# 32pins.net
KiCad netlist of a schematic drawn in EAGLE
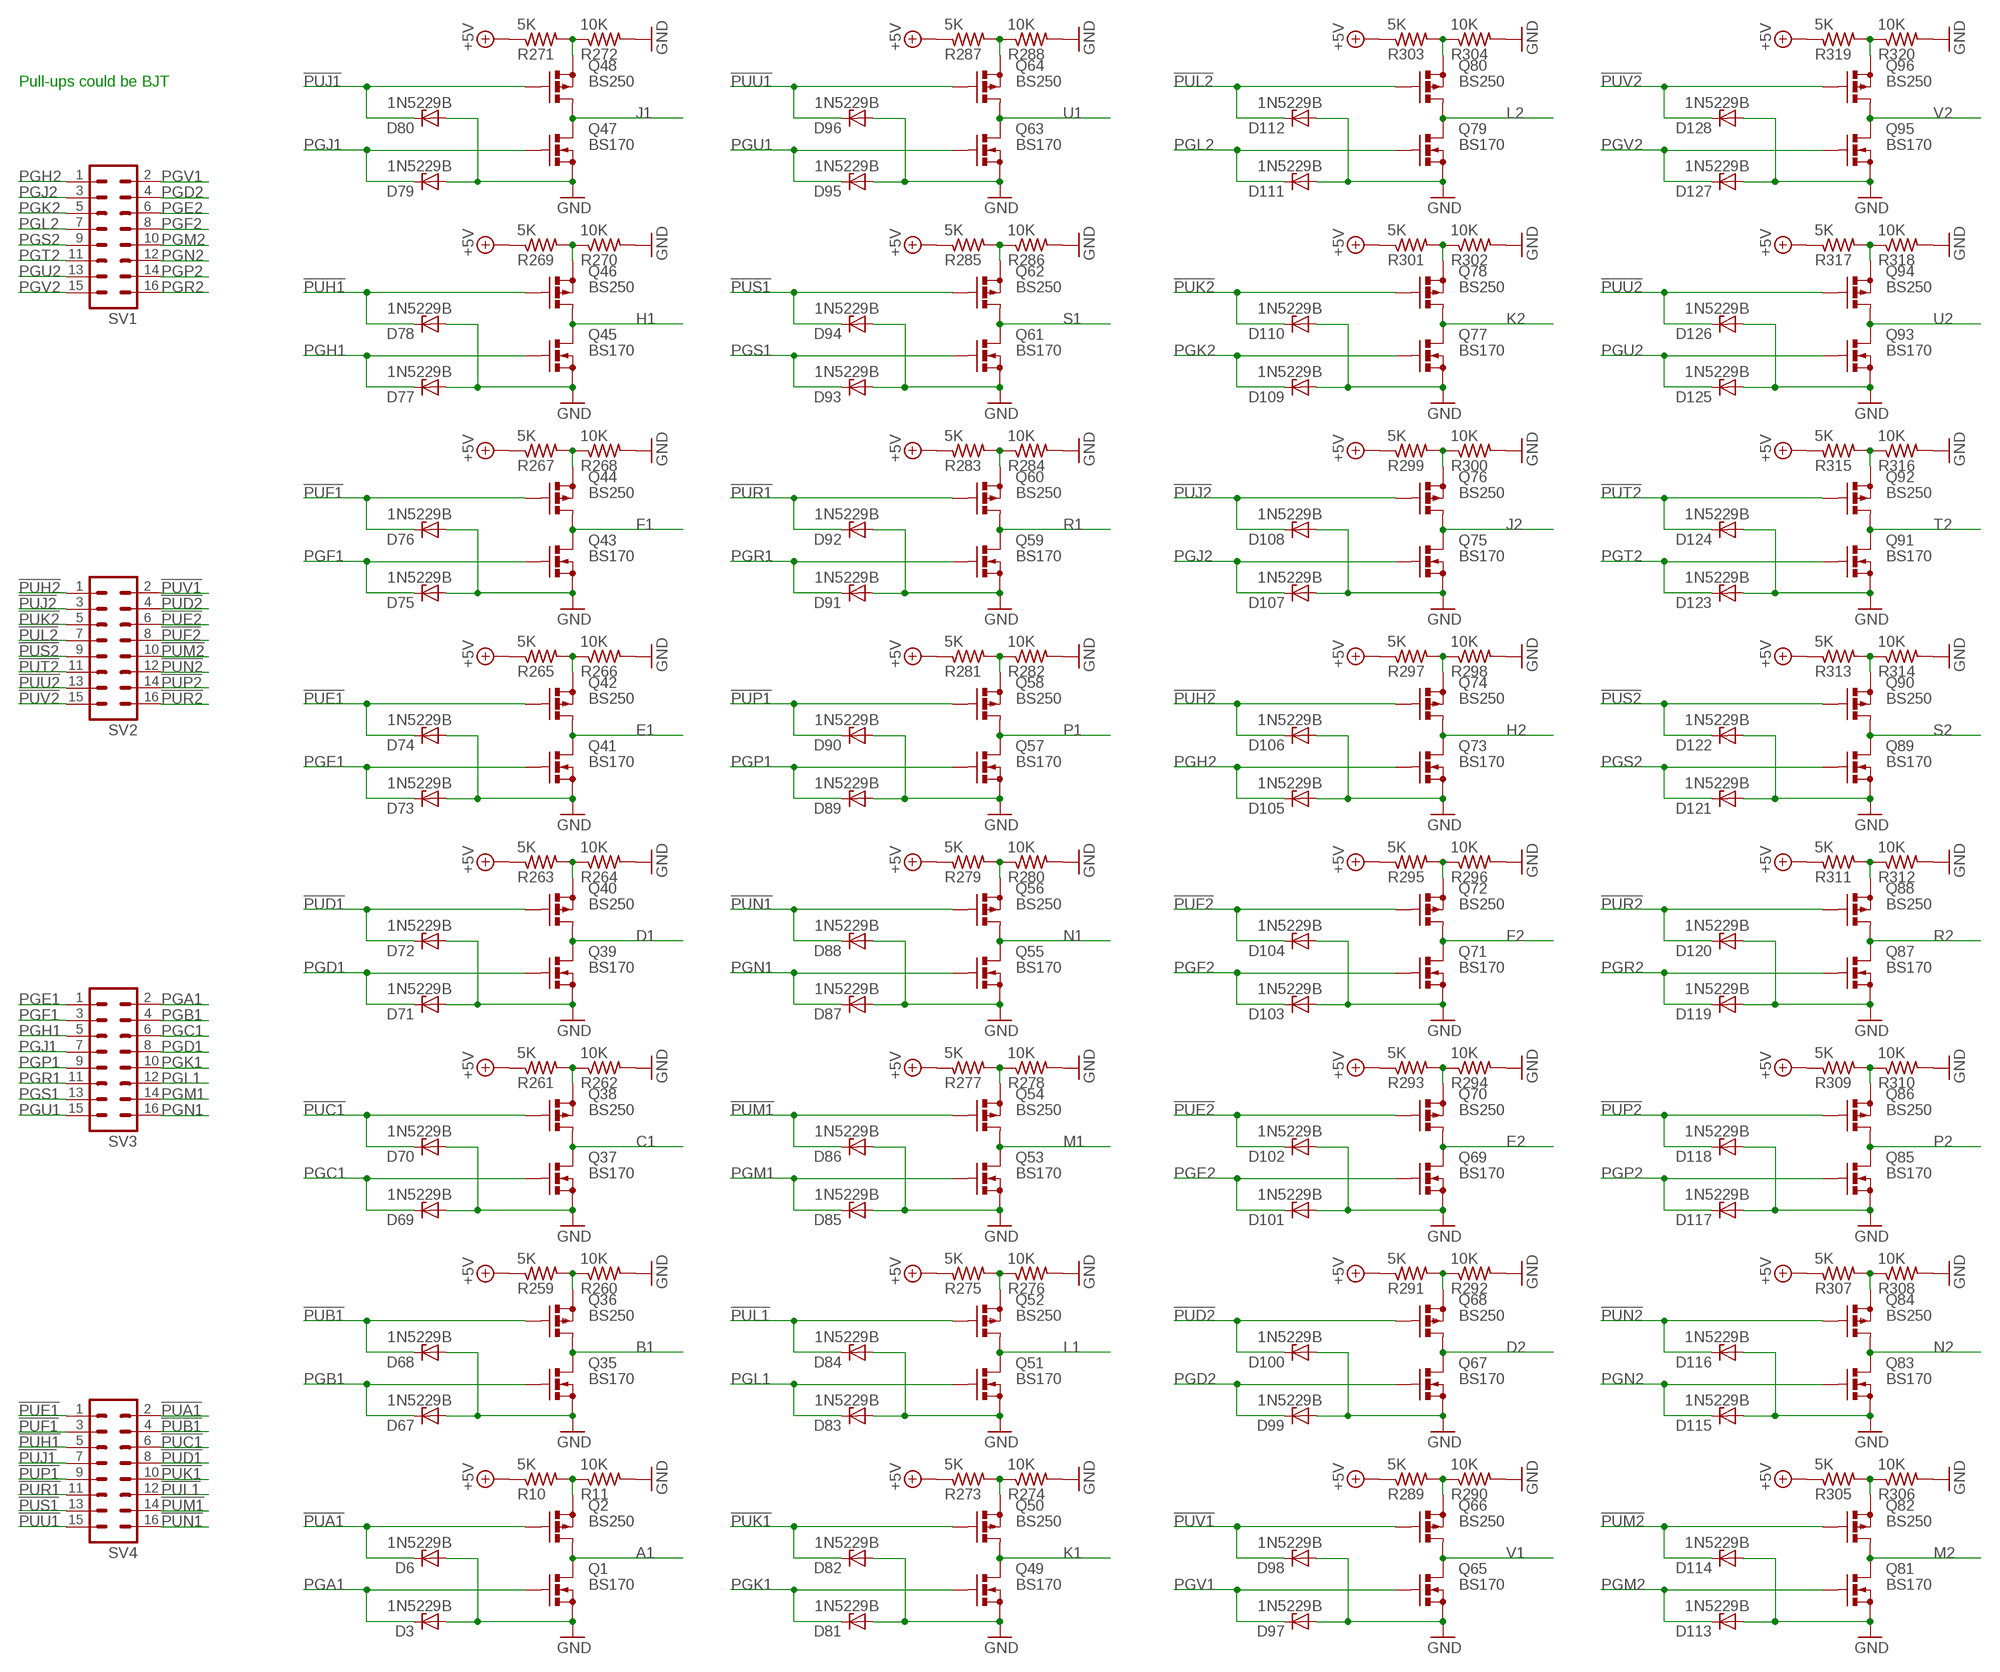
[diagram p0: schematic, sheet 1]
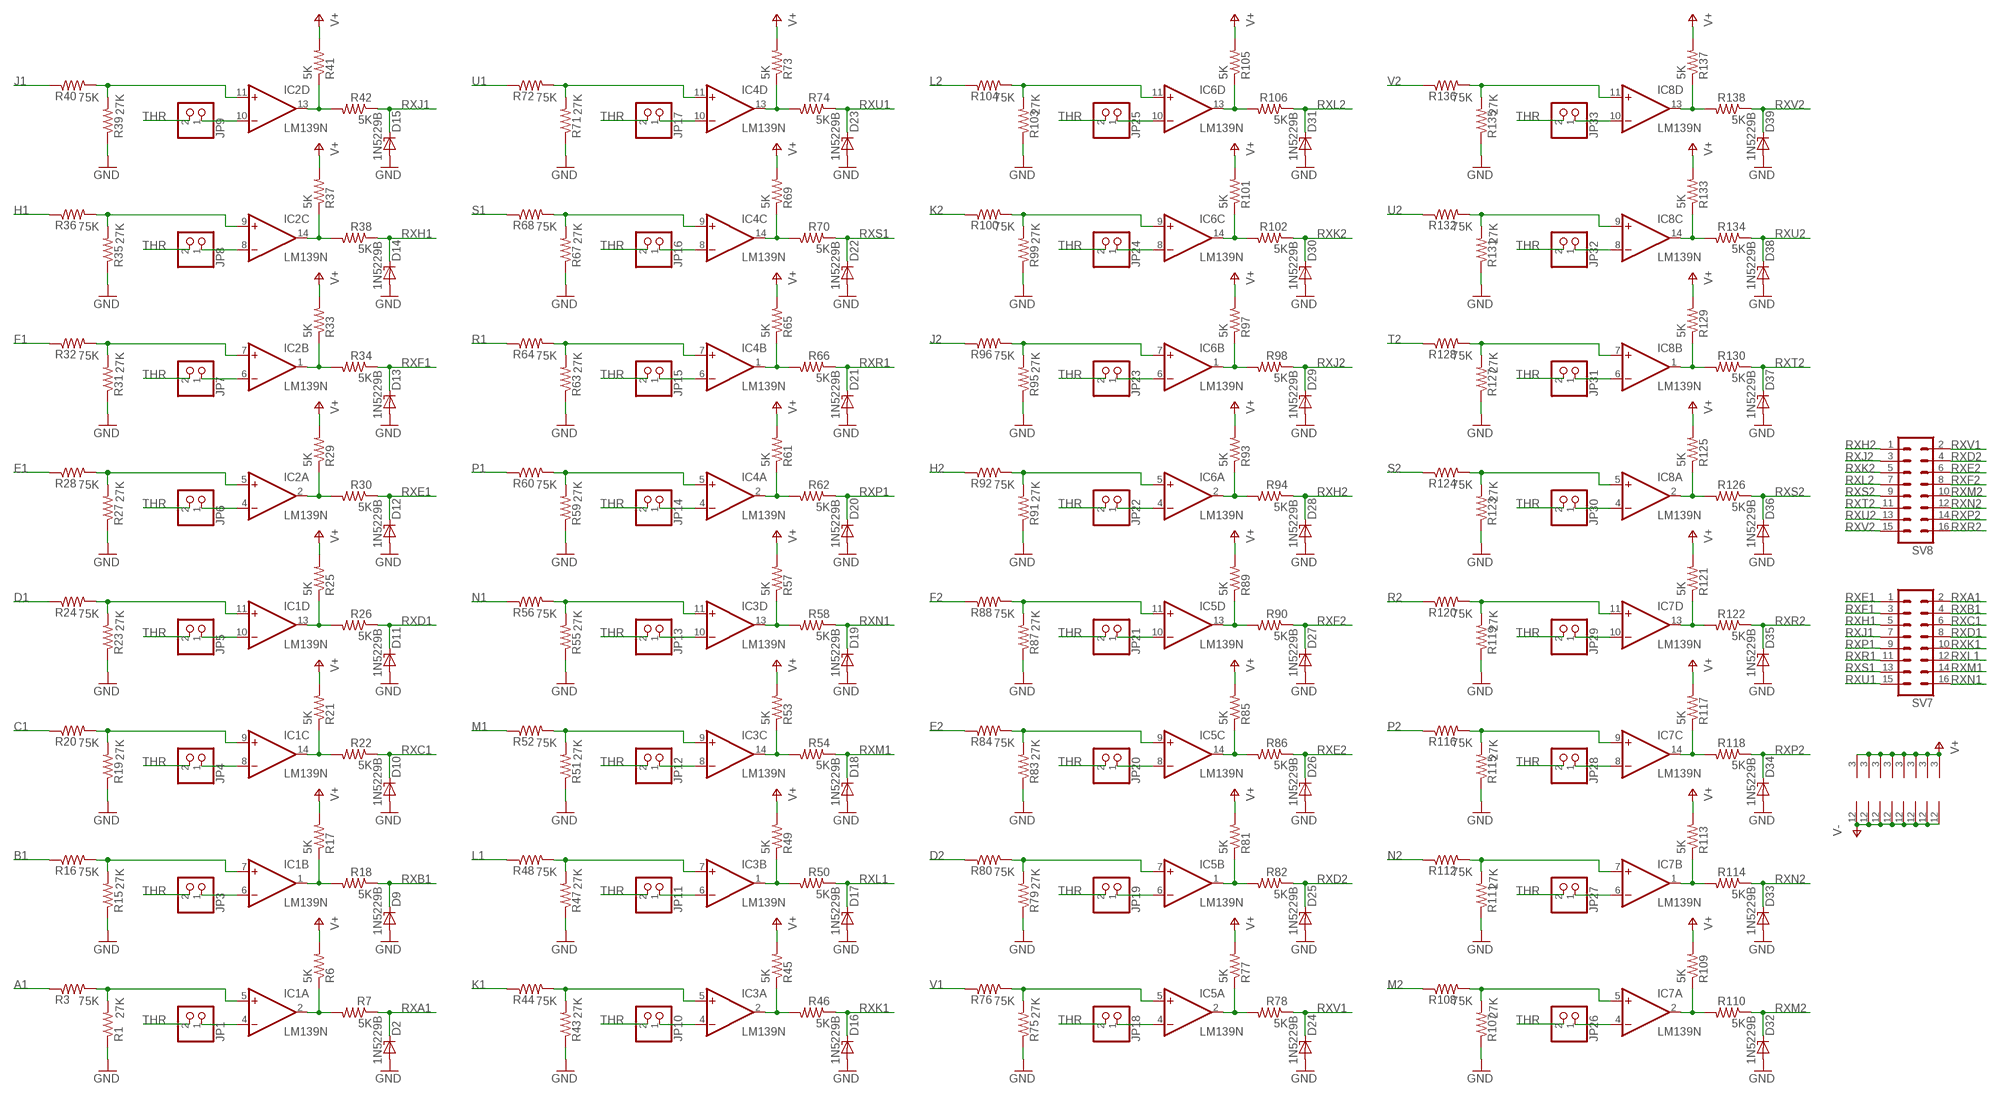
[diagram p1: schematic, sheet 2]
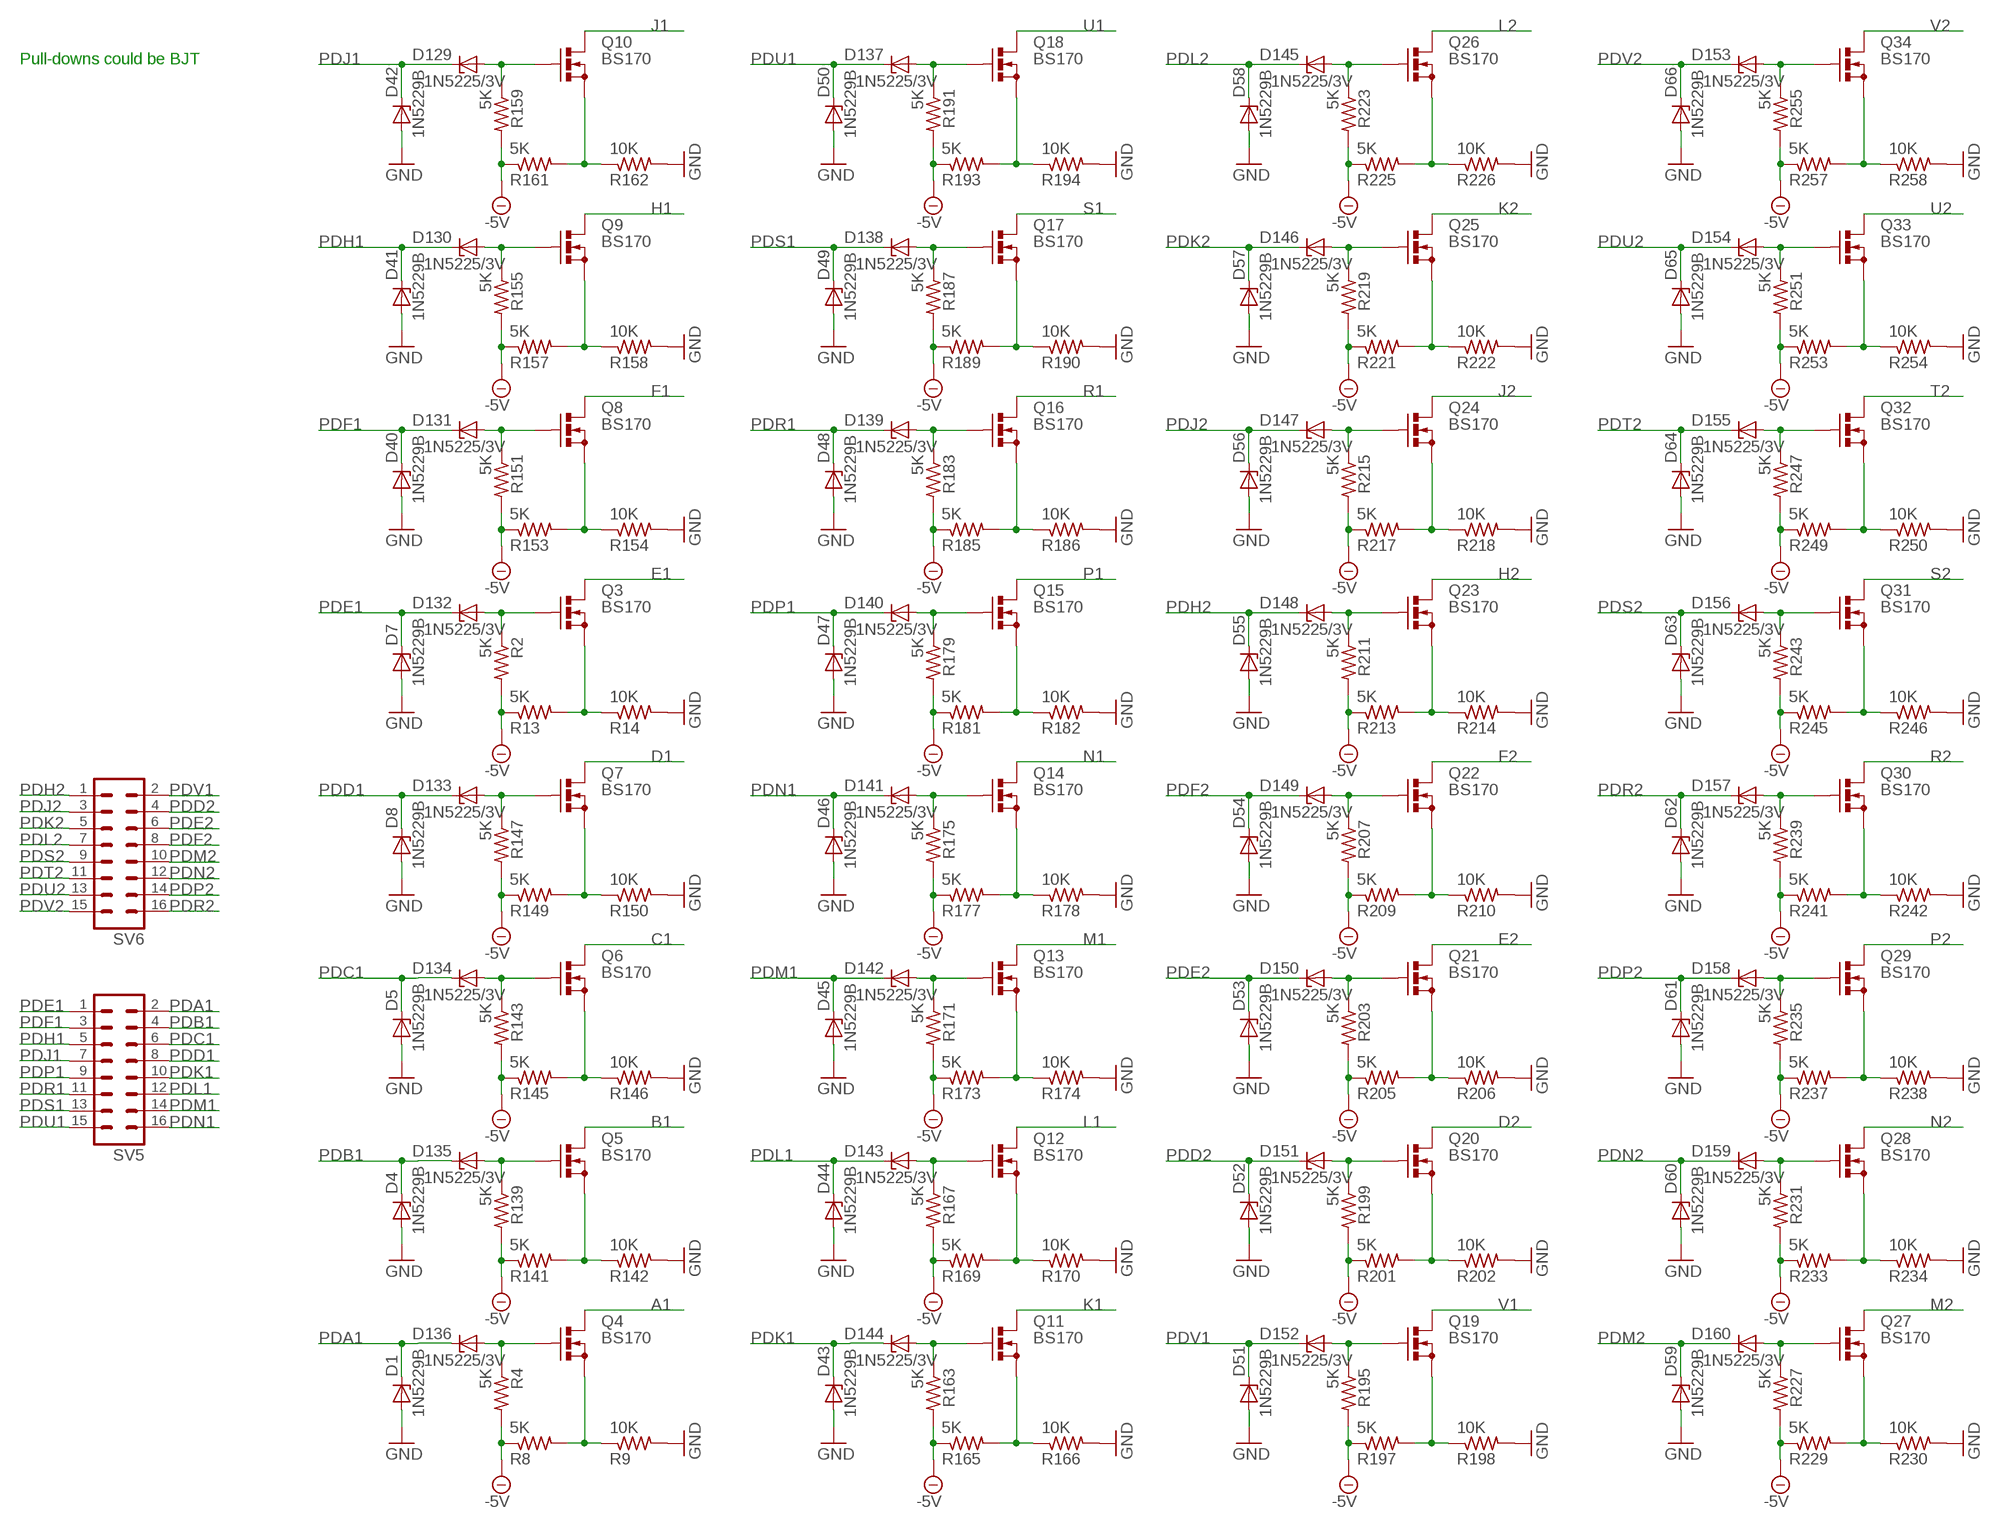
[diagram p2: schematic, sheet 3]
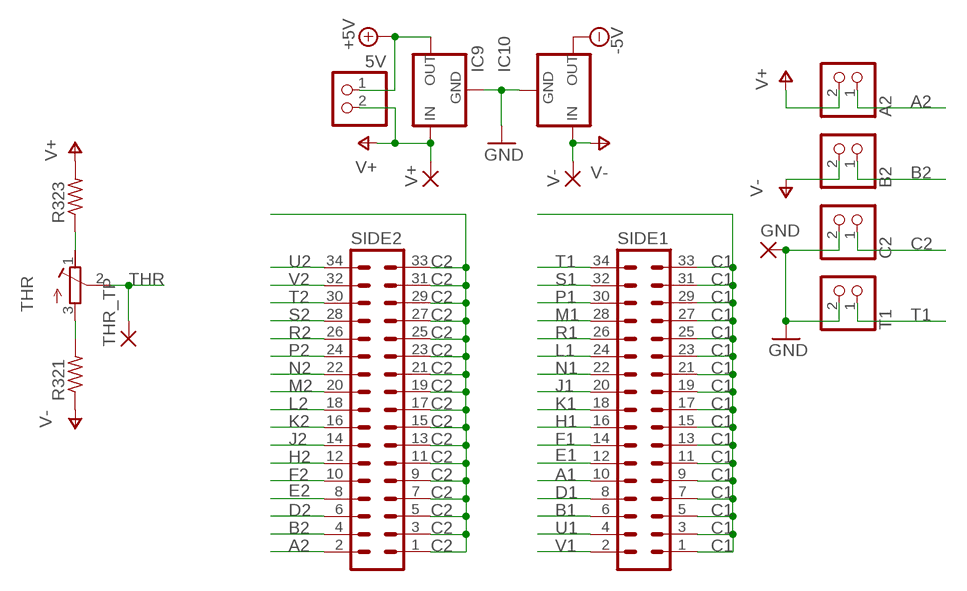
[diagram p3: schematic, sheet 4]

(export (version "E")
  (design (tool "Eeschema 10.0.6"))
  (components
    (comp (ref "D3")
      (value "1N5229B")
      (footprint "eagle-import:ZDIO-2.5")
      (libsource (lib "eagle-import") (part "ZENER-DIODEZD-2.5"))
    )
    (comp (ref "D6")
      (value "1N5229B")
      (footprint "eagle-import:ZDIO-2.5")
      (libsource (lib "eagle-import") (part "ZENER-DIODEZD-2.5"))
    )
    (comp (ref "D67")
      (value "1N5229B")
      (footprint "eagle-import:ZDIO-2.5")
      (libsource (lib "eagle-import") (part "ZENER-DIODEZD-2.5"))
    )
    (comp (ref "D68")
      (value "1N5229B")
      (footprint "eagle-import:ZDIO-2.5")
      (libsource (lib "eagle-import") (part "ZENER-DIODEZD-2.5"))
    )
    (comp (ref "D69")
      (value "1N5229B")
      (footprint "eagle-import:ZDIO-2.5")
      (libsource (lib "eagle-import") (part "ZENER-DIODEZD-2.5"))
    )
    (comp (ref "D70")
      (value "1N5229B")
      (footprint "eagle-import:ZDIO-2.5")
      (libsource (lib "eagle-import") (part "ZENER-DIODEZD-2.5"))
    )
    (comp (ref "D71")
      (value "1N5229B")
      (footprint "eagle-import:ZDIO-2.5")
      (libsource (lib "eagle-import") (part "ZENER-DIODEZD-2.5"))
    )
    (comp (ref "D72")
      (value "1N5229B")
      (footprint "eagle-import:ZDIO-2.5")
      (libsource (lib "eagle-import") (part "ZENER-DIODEZD-2.5"))
    )
    (comp (ref "D73")
      (value "1N5229B")
      (footprint "eagle-import:ZDIO-2.5")
      (libsource (lib "eagle-import") (part "ZENER-DIODEZD-2.5"))
    )
    (comp (ref "D74")
      (value "1N5229B")
      (footprint "eagle-import:ZDIO-2.5")
      (libsource (lib "eagle-import") (part "ZENER-DIODEZD-2.5"))
    )
    (comp (ref "D75")
      (value "1N5229B")
      (footprint "eagle-import:ZDIO-2.5")
      (libsource (lib "eagle-import") (part "ZENER-DIODEZD-2.5"))
    )
    (comp (ref "D76")
      (value "1N5229B")
      (footprint "eagle-import:ZDIO-2.5")
      (libsource (lib "eagle-import") (part "ZENER-DIODEZD-2.5"))
    )
    (comp (ref "D77")
      (value "1N5229B")
      (footprint "eagle-import:ZDIO-2.5")
      (libsource (lib "eagle-import") (part "ZENER-DIODEZD-2.5"))
    )
    (comp (ref "D78")
      (value "1N5229B")
      (footprint "eagle-import:ZDIO-2.5")
      (libsource (lib "eagle-import") (part "ZENER-DIODEZD-2.5"))
    )
    (comp (ref "D79")
      (value "1N5229B")
      (footprint "eagle-import:ZDIO-2.5")
      (libsource (lib "eagle-import") (part "ZENER-DIODEZD-2.5"))
    )
    (comp (ref "D80")
      (value "1N5229B")
      (footprint "eagle-import:ZDIO-2.5")
      (libsource (lib "eagle-import") (part "ZENER-DIODEZD-2.5"))
    )
    (comp (ref "D81")
      (value "1N5229B")
      (footprint "eagle-import:ZDIO-2.5")
      (libsource (lib "eagle-import") (part "ZENER-DIODEZD-2.5"))
    )
    (comp (ref "D82")
      (value "1N5229B")
      (footprint "eagle-import:ZDIO-2.5")
      (libsource (lib "eagle-import") (part "ZENER-DIODEZD-2.5"))
    )
    (comp (ref "D83")
      (value "1N5229B")
      (footprint "eagle-import:ZDIO-2.5")
      (libsource (lib "eagle-import") (part "ZENER-DIODEZD-2.5"))
    )
    (comp (ref "D84")
      (value "1N5229B")
      (footprint "eagle-import:ZDIO-2.5")
      (libsource (lib "eagle-import") (part "ZENER-DIODEZD-2.5"))
    )
    (comp (ref "D85")
      (value "1N5229B")
      (footprint "eagle-import:ZDIO-2.5")
      (libsource (lib "eagle-import") (part "ZENER-DIODEZD-2.5"))
    )
    (comp (ref "D86")
      (value "1N5229B")
      (footprint "eagle-import:ZDIO-2.5")
      (libsource (lib "eagle-import") (part "ZENER-DIODEZD-2.5"))
    )
    (comp (ref "D87")
      (value "1N5229B")
      (footprint "eagle-import:ZDIO-2.5")
      (libsource (lib "eagle-import") (part "ZENER-DIODEZD-2.5"))
    )
    (comp (ref "D88")
      (value "1N5229B")
      (footprint "eagle-import:ZDIO-2.5")
      (libsource (lib "eagle-import") (part "ZENER-DIODEZD-2.5"))
    )
    (comp (ref "D89")
      (value "1N5229B")
      (footprint "eagle-import:ZDIO-2.5")
      (libsource (lib "eagle-import") (part "ZENER-DIODEZD-2.5"))
    )
    (comp (ref "D90")
      (value "1N5229B")
      (footprint "eagle-import:ZDIO-2.5")
      (libsource (lib "eagle-import") (part "ZENER-DIODEZD-2.5"))
    )
    (comp (ref "D91")
      (value "1N5229B")
      (footprint "eagle-import:ZDIO-2.5")
      (libsource (lib "eagle-import") (part "ZENER-DIODEZD-2.5"))
    )
    (comp (ref "D92")
      (value "1N5229B")
      (footprint "eagle-import:ZDIO-2.5")
      (libsource (lib "eagle-import") (part "ZENER-DIODEZD-2.5"))
    )
    (comp (ref "D93")
      (value "1N5229B")
      (footprint "eagle-import:ZDIO-2.5")
      (libsource (lib "eagle-import") (part "ZENER-DIODEZD-2.5"))
    )
    (comp (ref "D94")
      (value "1N5229B")
      (footprint "eagle-import:ZDIO-2.5")
      (libsource (lib "eagle-import") (part "ZENER-DIODEZD-2.5"))
    )
    (comp (ref "D95")
      (value "1N5229B")
      (footprint "eagle-import:ZDIO-2.5")
      (libsource (lib "eagle-import") (part "ZENER-DIODEZD-2.5"))
    )
    (comp (ref "D96")
      (value "1N5229B")
      (footprint "eagle-import:ZDIO-2.5")
      (libsource (lib "eagle-import") (part "ZENER-DIODEZD-2.5"))
    )
    (comp (ref "D97")
      (value "1N5229B")
      (footprint "eagle-import:ZDIO-2.5")
      (libsource (lib "eagle-import") (part "ZENER-DIODEZD-2.5"))
    )
    (comp (ref "D98")
      (value "1N5229B")
      (footprint "eagle-import:ZDIO-2.5")
      (libsource (lib "eagle-import") (part "ZENER-DIODEZD-2.5"))
    )
    (comp (ref "D99")
      (value "1N5229B")
      (footprint "eagle-import:ZDIO-2.5")
      (libsource (lib "eagle-import") (part "ZENER-DIODEZD-2.5"))
    )
    (comp (ref "D100")
      (value "1N5229B")
      (footprint "eagle-import:ZDIO-2.5")
      (libsource (lib "eagle-import") (part "ZENER-DIODEZD-2.5"))
    )
    (comp (ref "D101")
      (value "1N5229B")
      (footprint "eagle-import:ZDIO-2.5")
      (libsource (lib "eagle-import") (part "ZENER-DIODEZD-2.5"))
    )
    (comp (ref "D102")
      (value "1N5229B")
      (footprint "eagle-import:ZDIO-2.5")
      (libsource (lib "eagle-import") (part "ZENER-DIODEZD-2.5"))
    )
    (comp (ref "D103")
      (value "1N5229B")
      (footprint "eagle-import:ZDIO-2.5")
      (libsource (lib "eagle-import") (part "ZENER-DIODEZD-2.5"))
    )
    (comp (ref "D104")
      (value "1N5229B")
      (footprint "eagle-import:ZDIO-2.5")
      (libsource (lib "eagle-import") (part "ZENER-DIODEZD-2.5"))
    )
    (comp (ref "D105")
      (value "1N5229B")
      (footprint "eagle-import:ZDIO-2.5")
      (libsource (lib "eagle-import") (part "ZENER-DIODEZD-2.5"))
    )
    (comp (ref "D106")
      (value "1N5229B")
      (footprint "eagle-import:ZDIO-2.5")
      (libsource (lib "eagle-import") (part "ZENER-DIODEZD-2.5"))
    )
    (comp (ref "D107")
      (value "1N5229B")
      (footprint "eagle-import:ZDIO-2.5")
      (libsource (lib "eagle-import") (part "ZENER-DIODEZD-2.5"))
    )
    (comp (ref "D108")
      (value "1N5229B")
      (footprint "eagle-import:ZDIO-2.5")
      (libsource (lib "eagle-import") (part "ZENER-DIODEZD-2.5"))
    )
    (comp (ref "D109")
      (value "1N5229B")
      (footprint "eagle-import:ZDIO-2.5")
      (libsource (lib "eagle-import") (part "ZENER-DIODEZD-2.5"))
    )
    (comp (ref "D110")
      (value "1N5229B")
      (footprint "eagle-import:ZDIO-2.5")
      (libsource (lib "eagle-import") (part "ZENER-DIODEZD-2.5"))
    )
    (comp (ref "D111")
      (value "1N5229B")
      (footprint "eagle-import:ZDIO-2.5")
      (libsource (lib "eagle-import") (part "ZENER-DIODEZD-2.5"))
    )
    (comp (ref "D112")
      (value "1N5229B")
      (footprint "eagle-import:ZDIO-2.5")
      (libsource (lib "eagle-import") (part "ZENER-DIODEZD-2.5"))
    )
    (comp (ref "D113")
      (value "1N5229B")
      (footprint "eagle-import:ZDIO-2.5")
      (libsource (lib "eagle-import") (part "ZENER-DIODEZD-2.5"))
    )
    (comp (ref "D114")
      (value "1N5229B")
      (footprint "eagle-import:ZDIO-2.5")
      (libsource (lib "eagle-import") (part "ZENER-DIODEZD-2.5"))
    )
    (comp (ref "D115")
      (value "1N5229B")
      (footprint "eagle-import:ZDIO-2.5")
      (libsource (lib "eagle-import") (part "ZENER-DIODEZD-2.5"))
    )
    (comp (ref "D116")
      (value "1N5229B")
      (footprint "eagle-import:ZDIO-2.5")
      (libsource (lib "eagle-import") (part "ZENER-DIODEZD-2.5"))
    )
    (comp (ref "D117")
      (value "1N5229B")
      (footprint "eagle-import:ZDIO-2.5")
      (libsource (lib "eagle-import") (part "ZENER-DIODEZD-2.5"))
    )
    (comp (ref "D118")
      (value "1N5229B")
      (footprint "eagle-import:ZDIO-2.5")
      (libsource (lib "eagle-import") (part "ZENER-DIODEZD-2.5"))
    )
    (comp (ref "D119")
      (value "1N5229B")
      (footprint "eagle-import:ZDIO-2.5")
      (libsource (lib "eagle-import") (part "ZENER-DIODEZD-2.5"))
    )
    (comp (ref "D120")
      (value "1N5229B")
      (footprint "eagle-import:ZDIO-2.5")
      (libsource (lib "eagle-import") (part "ZENER-DIODEZD-2.5"))
    )
    (comp (ref "D121")
      (value "1N5229B")
      (footprint "eagle-import:ZDIO-2.5")
      (libsource (lib "eagle-import") (part "ZENER-DIODEZD-2.5"))
    )
    (comp (ref "D122")
      (value "1N5229B")
      (footprint "eagle-import:ZDIO-2.5")
      (libsource (lib "eagle-import") (part "ZENER-DIODEZD-2.5"))
    )
    (comp (ref "D123")
      (value "1N5229B")
      (footprint "eagle-import:ZDIO-2.5")
      (libsource (lib "eagle-import") (part "ZENER-DIODEZD-2.5"))
    )
    (comp (ref "D124")
      (value "1N5229B")
      (footprint "eagle-import:ZDIO-2.5")
      (libsource (lib "eagle-import") (part "ZENER-DIODEZD-2.5"))
    )
    (comp (ref "D125")
      (value "1N5229B")
      (footprint "eagle-import:ZDIO-2.5")
      (libsource (lib "eagle-import") (part "ZENER-DIODEZD-2.5"))
    )
    (comp (ref "D126")
      (value "1N5229B")
      (footprint "eagle-import:ZDIO-2.5")
      (libsource (lib "eagle-import") (part "ZENER-DIODEZD-2.5"))
    )
    (comp (ref "D127")
      (value "1N5229B")
      (footprint "eagle-import:ZDIO-2.5")
      (libsource (lib "eagle-import") (part "ZENER-DIODEZD-2.5"))
    )
    (comp (ref "D128")
      (value "1N5229B")
      (footprint "eagle-import:ZDIO-2.5")
      (libsource (lib "eagle-import") (part "ZENER-DIODEZD-2.5"))
    )
    (comp (ref "Q1")
      (value "BS170")
      (footprint "eagle-import:SOT54E")
      (libsource (lib "eagle-import") (part "BS170"))
    )
    (comp (ref "Q2")
      (value "BS250")
      (footprint "eagle-import:SOT54E")
      (libsource (lib "eagle-import") (part "BS250"))
    )
    (comp (ref "Q35")
      (value "BS170")
      (footprint "eagle-import:SOT54E")
      (libsource (lib "eagle-import") (part "BS170"))
    )
    (comp (ref "Q36")
      (value "BS250")
      (footprint "eagle-import:SOT54E")
      (libsource (lib "eagle-import") (part "BS250"))
    )
    (comp (ref "Q37")
      (value "BS170")
      (footprint "eagle-import:SOT54E")
      (libsource (lib "eagle-import") (part "BS170"))
    )
    (comp (ref "Q38")
      (value "BS250")
      (footprint "eagle-import:SOT54E")
      (libsource (lib "eagle-import") (part "BS250"))
    )
    (comp (ref "Q39")
      (value "BS170")
      (footprint "eagle-import:SOT54E")
      (libsource (lib "eagle-import") (part "BS170"))
    )
    (comp (ref "Q40")
      (value "BS250")
      (footprint "eagle-import:SOT54E")
      (libsource (lib "eagle-import") (part "BS250"))
    )
    (comp (ref "Q41")
      (value "BS170")
      (footprint "eagle-import:SOT54E")
      (libsource (lib "eagle-import") (part "BS170"))
    )
    (comp (ref "Q42")
      (value "BS250")
      (footprint "eagle-import:SOT54E")
      (libsource (lib "eagle-import") (part "BS250"))
    )
    (comp (ref "Q43")
      (value "BS170")
      (footprint "eagle-import:SOT54E")
      (libsource (lib "eagle-import") (part "BS170"))
    )
    (comp (ref "Q44")
      (value "BS250")
      (footprint "eagle-import:SOT54E")
      (libsource (lib "eagle-import") (part "BS250"))
    )
    (comp (ref "Q45")
      (value "BS170")
      (footprint "eagle-import:SOT54E")
      (libsource (lib "eagle-import") (part "BS170"))
    )
    (comp (ref "Q46")
      (value "BS250")
      (footprint "eagle-import:SOT54E")
      (libsource (lib "eagle-import") (part "BS250"))
    )
    (comp (ref "Q47")
      (value "BS170")
      (footprint "eagle-import:SOT54E")
      (libsource (lib "eagle-import") (part "BS170"))
    )
    (comp (ref "Q48")
      (value "BS250")
      (footprint "eagle-import:SOT54E")
      (libsource (lib "eagle-import") (part "BS250"))
    )
    (comp (ref "Q49")
      (value "BS170")
      (footprint "eagle-import:SOT54E")
      (libsource (lib "eagle-import") (part "BS170"))
    )
    (comp (ref "Q50")
      (value "BS250")
      (footprint "eagle-import:SOT54E")
      (libsource (lib "eagle-import") (part "BS250"))
    )
    (comp (ref "Q51")
      (value "BS170")
      (footprint "eagle-import:SOT54E")
      (libsource (lib "eagle-import") (part "BS170"))
    )
    (comp (ref "Q52")
      (value "BS250")
      (footprint "eagle-import:SOT54E")
      (libsource (lib "eagle-import") (part "BS250"))
    )
    (comp (ref "Q53")
      (value "BS170")
      (footprint "eagle-import:SOT54E")
      (libsource (lib "eagle-import") (part "BS170"))
    )
    (comp (ref "Q54")
      (value "BS250")
      (footprint "eagle-import:SOT54E")
      (libsource (lib "eagle-import") (part "BS250"))
    )
    (comp (ref "Q55")
      (value "BS170")
      (footprint "eagle-import:SOT54E")
      (libsource (lib "eagle-import") (part "BS170"))
    )
    (comp (ref "Q56")
      (value "BS250")
      (footprint "eagle-import:SOT54E")
      (libsource (lib "eagle-import") (part "BS250"))
    )
    (comp (ref "Q57")
      (value "BS170")
      (footprint "eagle-import:SOT54E")
      (libsource (lib "eagle-import") (part "BS170"))
    )
    (comp (ref "Q58")
      (value "BS250")
      (footprint "eagle-import:SOT54E")
      (libsource (lib "eagle-import") (part "BS250"))
    )
    (comp (ref "Q59")
      (value "BS170")
      (footprint "eagle-import:SOT54E")
      (libsource (lib "eagle-import") (part "BS170"))
    )
    (comp (ref "Q60")
      (value "BS250")
      (footprint "eagle-import:SOT54E")
      (libsource (lib "eagle-import") (part "BS250"))
    )
    (comp (ref "Q61")
      (value "BS170")
      (footprint "eagle-import:SOT54E")
      (libsource (lib "eagle-import") (part "BS170"))
    )
    (comp (ref "Q62")
      (value "BS250")
      (footprint "eagle-import:SOT54E")
      (libsource (lib "eagle-import") (part "BS250"))
    )
    (comp (ref "Q63")
      (value "BS170")
      (footprint "eagle-import:SOT54E")
      (libsource (lib "eagle-import") (part "BS170"))
    )
    (comp (ref "Q64")
      (value "BS250")
      (footprint "eagle-import:SOT54E")
      (libsource (lib "eagle-import") (part "BS250"))
    )
    (comp (ref "Q65")
      (value "BS170")
      (footprint "eagle-import:SOT54E")
      (libsource (lib "eagle-import") (part "BS170"))
    )
    (comp (ref "Q66")
      (value "BS250")
      (footprint "eagle-import:SOT54E")
      (libsource (lib "eagle-import") (part "BS250"))
    )
    (comp (ref "Q67")
      (value "BS170")
      (footprint "eagle-import:SOT54E")
      (libsource (lib "eagle-import") (part "BS170"))
    )
    (comp (ref "Q68")
      (value "BS250")
      (footprint "eagle-import:SOT54E")
      (libsource (lib "eagle-import") (part "BS250"))
    )
    (comp (ref "Q69")
      (value "BS170")
      (footprint "eagle-import:SOT54E")
      (libsource (lib "eagle-import") (part "BS170"))
    )
    (comp (ref "Q70")
      (value "BS250")
      (footprint "eagle-import:SOT54E")
      (libsource (lib "eagle-import") (part "BS250"))
    )
    (comp (ref "Q71")
      (value "BS170")
      (footprint "eagle-import:SOT54E")
      (libsource (lib "eagle-import") (part "BS170"))
    )
    (comp (ref "Q72")
      (value "BS250")
      (footprint "eagle-import:SOT54E")
      (libsource (lib "eagle-import") (part "BS250"))
    )
    (comp (ref "Q73")
      (value "BS170")
      (footprint "eagle-import:SOT54E")
      (libsource (lib "eagle-import") (part "BS170"))
    )
    (comp (ref "Q74")
      (value "BS250")
      (footprint "eagle-import:SOT54E")
      (libsource (lib "eagle-import") (part "BS250"))
    )
    (comp (ref "Q75")
      (value "BS170")
      (footprint "eagle-import:SOT54E")
      (libsource (lib "eagle-import") (part "BS170"))
    )
    (comp (ref "Q76")
      (value "BS250")
      (footprint "eagle-import:SOT54E")
      (libsource (lib "eagle-import") (part "BS250"))
    )
    (comp (ref "Q77")
      (value "BS170")
      (footprint "eagle-import:SOT54E")
      (libsource (lib "eagle-import") (part "BS170"))
    )
    (comp (ref "Q78")
      (value "BS250")
      (footprint "eagle-import:SOT54E")
      (libsource (lib "eagle-import") (part "BS250"))
    )
    (comp (ref "Q79")
      (value "BS170")
      (footprint "eagle-import:SOT54E")
      (libsource (lib "eagle-import") (part "BS170"))
    )
    (comp (ref "Q80")
      (value "BS250")
      (footprint "eagle-import:SOT54E")
      (libsource (lib "eagle-import") (part "BS250"))
    )
    (comp (ref "Q81")
      (value "BS170")
      (footprint "eagle-import:SOT54E")
      (libsource (lib "eagle-import") (part "BS170"))
    )
    (comp (ref "Q82")
      (value "BS250")
      (footprint "eagle-import:SOT54E")
      (libsource (lib "eagle-import") (part "BS250"))
    )
    (comp (ref "Q83")
      (value "BS170")
      (footprint "eagle-import:SOT54E")
      (libsource (lib "eagle-import") (part "BS170"))
    )
    (comp (ref "Q84")
      (value "BS250")
      (footprint "eagle-import:SOT54E")
      (libsource (lib "eagle-import") (part "BS250"))
    )
    (comp (ref "Q85")
      (value "BS170")
      (footprint "eagle-import:SOT54E")
      (libsource (lib "eagle-import") (part "BS170"))
    )
    (comp (ref "Q86")
      (value "BS250")
      (footprint "eagle-import:SOT54E")
      (libsource (lib "eagle-import") (part "BS250"))
    )
    (comp (ref "Q87")
      (value "BS170")
      (footprint "eagle-import:SOT54E")
      (libsource (lib "eagle-import") (part "BS170"))
    )
    (comp (ref "Q88")
      (value "BS250")
      (footprint "eagle-import:SOT54E")
      (libsource (lib "eagle-import") (part "BS250"))
    )
    (comp (ref "Q89")
      (value "BS170")
      (footprint "eagle-import:SOT54E")
      (libsource (lib "eagle-import") (part "BS170"))
    )
    (comp (ref "Q90")
      (value "BS250")
      (footprint "eagle-import:SOT54E")
      (libsource (lib "eagle-import") (part "BS250"))
    )
    (comp (ref "Q91")
      (value "BS170")
      (footprint "eagle-import:SOT54E")
      (libsource (lib "eagle-import") (part "BS170"))
    )
    (comp (ref "Q92")
      (value "BS250")
      (footprint "eagle-import:SOT54E")
      (libsource (lib "eagle-import") (part "BS250"))
    )
    (comp (ref "Q93")
      (value "BS170")
      (footprint "eagle-import:SOT54E")
      (libsource (lib "eagle-import") (part "BS170"))
    )
    (comp (ref "Q94")
      (value "BS250")
      (footprint "eagle-import:SOT54E")
      (libsource (lib "eagle-import") (part "BS250"))
    )
    (comp (ref "Q95")
      (value "BS170")
      (footprint "eagle-import:SOT54E")
      (libsource (lib "eagle-import") (part "BS170"))
    )
    (comp (ref "Q96")
      (value "BS250")
      (footprint "eagle-import:SOT54E")
      (libsource (lib "eagle-import") (part "BS250"))
    )
    (comp (ref "R10")
      (value "5K")
      (footprint "eagle-import:0207_2V")
      (libsource (lib "eagle-import") (part "R-US_0207/2V"))
    )
    (comp (ref "R11")
      (value "10K")
      (footprint "eagle-import:0207_2V")
      (libsource (lib "eagle-import") (part "R-US_0207/2V"))
    )
    (comp (ref "R259")
      (value "5K")
      (footprint "eagle-import:0207_2V")
      (libsource (lib "eagle-import") (part "R-US_0207/2V"))
    )
    (comp (ref "R260")
      (value "10K")
      (footprint "eagle-import:0207_2V")
      (libsource (lib "eagle-import") (part "R-US_0207/2V"))
    )
    (comp (ref "R261")
      (value "5K")
      (footprint "eagle-import:0207_2V")
      (libsource (lib "eagle-import") (part "R-US_0207/2V"))
    )
    (comp (ref "R262")
      (value "10K")
      (footprint "eagle-import:0207_2V")
      (libsource (lib "eagle-import") (part "R-US_0207/2V"))
    )
    (comp (ref "R263")
      (value "5K")
      (footprint "eagle-import:0207_2V")
      (libsource (lib "eagle-import") (part "R-US_0207/2V"))
    )
    (comp (ref "R264")
      (value "10K")
      (footprint "eagle-import:0207_2V")
      (libsource (lib "eagle-import") (part "R-US_0207/2V"))
    )
    (comp (ref "R265")
      (value "5K")
      (footprint "eagle-import:0207_2V")
      (libsource (lib "eagle-import") (part "R-US_0207/2V"))
    )
    (comp (ref "R266")
      (value "10K")
      (footprint "eagle-import:0207_2V")
      (libsource (lib "eagle-import") (part "R-US_0207/2V"))
    )
    (comp (ref "R267")
      (value "5K")
      (footprint "eagle-import:0207_2V")
      (libsource (lib "eagle-import") (part "R-US_0207/2V"))
    )
    (comp (ref "R268")
      (value "10K")
      (footprint "eagle-import:0207_2V")
      (libsource (lib "eagle-import") (part "R-US_0207/2V"))
    )
    (comp (ref "R269")
      (value "5K")
      (footprint "eagle-import:0207_2V")
      (libsource (lib "eagle-import") (part "R-US_0207/2V"))
    )
    (comp (ref "R270")
      (value "10K")
      (footprint "eagle-import:0207_2V")
      (libsource (lib "eagle-import") (part "R-US_0207/2V"))
    )
    (comp (ref "R271")
      (value "5K")
      (footprint "eagle-import:0207_2V")
      (libsource (lib "eagle-import") (part "R-US_0207/2V"))
    )
    (comp (ref "R272")
      (value "10K")
      (footprint "eagle-import:0207_2V")
      (libsource (lib "eagle-import") (part "R-US_0207/2V"))
    )
    (comp (ref "R273")
      (value "5K")
      (footprint "eagle-import:0207_2V")
      (libsource (lib "eagle-import") (part "R-US_0207/2V"))
    )
    (comp (ref "R274")
      (value "10K")
      (footprint "eagle-import:0207_2V")
      (libsource (lib "eagle-import") (part "R-US_0207/2V"))
    )
    (comp (ref "R275")
      (value "5K")
      (footprint "eagle-import:0207_2V")
      (libsource (lib "eagle-import") (part "R-US_0207/2V"))
    )
    (comp (ref "R276")
      (value "10K")
      (footprint "eagle-import:0207_2V")
      (libsource (lib "eagle-import") (part "R-US_0207/2V"))
    )
    (comp (ref "R277")
      (value "5K")
      (footprint "eagle-import:0207_2V")
      (libsource (lib "eagle-import") (part "R-US_0207/2V"))
    )
    (comp (ref "R278")
      (value "10K")
      (footprint "eagle-import:0207_2V")
      (libsource (lib "eagle-import") (part "R-US_0207/2V"))
    )
    (comp (ref "R279")
      (value "5K")
      (footprint "eagle-import:0207_2V")
      (libsource (lib "eagle-import") (part "R-US_0207/2V"))
    )
    (comp (ref "R280")
      (value "10K")
      (footprint "eagle-import:0207_2V")
      (libsource (lib "eagle-import") (part "R-US_0207/2V"))
    )
    (comp (ref "R281")
      (value "5K")
      (footprint "eagle-import:0207_2V")
      (libsource (lib "eagle-import") (part "R-US_0207/2V"))
    )
    (comp (ref "R282")
      (value "10K")
      (footprint "eagle-import:0207_2V")
      (libsource (lib "eagle-import") (part "R-US_0207/2V"))
    )
    (comp (ref "R283")
      (value "5K")
      (footprint "eagle-import:0207_2V")
      (libsource (lib "eagle-import") (part "R-US_0207/2V"))
    )
    (comp (ref "R284")
      (value "10K")
      (footprint "eagle-import:0207_2V")
      (libsource (lib "eagle-import") (part "R-US_0207/2V"))
    )
    (comp (ref "R285")
      (value "5K")
      (footprint "eagle-import:0207_2V")
      (libsource (lib "eagle-import") (part "R-US_0207/2V"))
    )
    (comp (ref "R286")
      (value "10K")
      (footprint "eagle-import:0207_2V")
      (libsource (lib "eagle-import") (part "R-US_0207/2V"))
    )
    (comp (ref "R287")
      (value "5K")
      (footprint "eagle-import:0207_2V")
      (libsource (lib "eagle-import") (part "R-US_0207/2V"))
    )
    (comp (ref "R288")
      (value "10K")
      (footprint "eagle-import:0207_2V")
      (libsource (lib "eagle-import") (part "R-US_0207/2V"))
    )
    (comp (ref "R289")
      (value "5K")
      (footprint "eagle-import:0207_2V")
      (libsource (lib "eagle-import") (part "R-US_0207/2V"))
    )
    (comp (ref "R290")
      (value "10K")
      (footprint "eagle-import:0207_2V")
      (libsource (lib "eagle-import") (part "R-US_0207/2V"))
    )
    (comp (ref "R291")
      (value "5K")
      (footprint "eagle-import:0207_2V")
      (libsource (lib "eagle-import") (part "R-US_0207/2V"))
    )
    (comp (ref "R292")
      (value "10K")
      (footprint "eagle-import:0207_2V")
      (libsource (lib "eagle-import") (part "R-US_0207/2V"))
    )
    (comp (ref "R293")
      (value "5K")
      (footprint "eagle-import:0207_2V")
      (libsource (lib "eagle-import") (part "R-US_0207/2V"))
    )
    (comp (ref "R294")
      (value "10K")
      (footprint "eagle-import:0207_2V")
      (libsource (lib "eagle-import") (part "R-US_0207/2V"))
    )
    (comp (ref "R295")
      (value "5K")
      (footprint "eagle-import:0207_2V")
      (libsource (lib "eagle-import") (part "R-US_0207/2V"))
    )
    (comp (ref "R296")
      (value "10K")
      (footprint "eagle-import:0207_2V")
      (libsource (lib "eagle-import") (part "R-US_0207/2V"))
    )
    (comp (ref "R297")
      (value "5K")
      (footprint "eagle-import:0207_2V")
      (libsource (lib "eagle-import") (part "R-US_0207/2V"))
    )
    (comp (ref "R298")
      (value "10K")
      (footprint "eagle-import:0207_2V")
      (libsource (lib "eagle-import") (part "R-US_0207/2V"))
    )
    (comp (ref "R299")
      (value "5K")
      (footprint "eagle-import:0207_2V")
      (libsource (lib "eagle-import") (part "R-US_0207/2V"))
    )
    (comp (ref "R300")
      (value "10K")
      (footprint "eagle-import:0207_2V")
      (libsource (lib "eagle-import") (part "R-US_0207/2V"))
    )
    (comp (ref "R301")
      (value "5K")
      (footprint "eagle-import:0207_2V")
      (libsource (lib "eagle-import") (part "R-US_0207/2V"))
    )
    (comp (ref "R302")
      (value "10K")
      (footprint "eagle-import:0207_2V")
      (libsource (lib "eagle-import") (part "R-US_0207/2V"))
    )
    (comp (ref "R303")
      (value "5K")
      (footprint "eagle-import:0207_2V")
      (libsource (lib "eagle-import") (part "R-US_0207/2V"))
    )
    (comp (ref "R304")
      (value "10K")
      (footprint "eagle-import:0207_2V")
      (libsource (lib "eagle-import") (part "R-US_0207/2V"))
    )
    (comp (ref "R305")
      (value "5K")
      (footprint "eagle-import:0207_2V")
      (libsource (lib "eagle-import") (part "R-US_0207/2V"))
    )
    (comp (ref "R306")
      (value "10K")
      (footprint "eagle-import:0207_2V")
      (libsource (lib "eagle-import") (part "R-US_0207/2V"))
    )
    (comp (ref "R307")
      (value "5K")
      (footprint "eagle-import:0207_2V")
      (libsource (lib "eagle-import") (part "R-US_0207/2V"))
    )
    (comp (ref "R308")
      (value "10K")
      (footprint "eagle-import:0207_2V")
      (libsource (lib "eagle-import") (part "R-US_0207/2V"))
    )
    (comp (ref "R309")
      (value "5K")
      (footprint "eagle-import:0207_2V")
      (libsource (lib "eagle-import") (part "R-US_0207/2V"))
    )
    (comp (ref "R310")
      (value "10K")
      (footprint "eagle-import:0207_2V")
      (libsource (lib "eagle-import") (part "R-US_0207/2V"))
    )
    (comp (ref "R311")
      (value "5K")
      (footprint "eagle-import:0207_2V")
      (libsource (lib "eagle-import") (part "R-US_0207/2V"))
    )
    (comp (ref "R312")
      (value "10K")
      (footprint "eagle-import:0207_2V")
      (libsource (lib "eagle-import") (part "R-US_0207/2V"))
    )
    (comp (ref "R313")
      (value "5K")
      (footprint "eagle-import:0207_2V")
      (libsource (lib "eagle-import") (part "R-US_0207/2V"))
    )
    (comp (ref "R314")
      (value "10K")
      (footprint "eagle-import:0207_2V")
      (libsource (lib "eagle-import") (part "R-US_0207/2V"))
    )
    (comp (ref "R315")
      (value "5K")
      (footprint "eagle-import:0207_2V")
      (libsource (lib "eagle-import") (part "R-US_0207/2V"))
    )
    (comp (ref "R316")
      (value "10K")
      (footprint "eagle-import:0207_2V")
      (libsource (lib "eagle-import") (part "R-US_0207/2V"))
    )
    (comp (ref "R317")
      (value "5K")
      (footprint "eagle-import:0207_2V")
      (libsource (lib "eagle-import") (part "R-US_0207/2V"))
    )
    (comp (ref "R318")
      (value "10K")
      (footprint "eagle-import:0207_2V")
      (libsource (lib "eagle-import") (part "R-US_0207/2V"))
    )
    (comp (ref "R319")
      (value "5K")
      (footprint "eagle-import:0207_2V")
      (libsource (lib "eagle-import") (part "R-US_0207/2V"))
    )
    (comp (ref "R320")
      (value "10K")
      (footprint "eagle-import:0207_2V")
      (libsource (lib "eagle-import") (part "R-US_0207/2V"))
    )
    (comp (ref "SV1")
      (value "MA08-2")
      (footprint "eagle-import:MA08-2")
      (libsource (lib "eagle-import") (part "MA08-2"))
    )
    (comp (ref "SV2")
      (value "MA08-2")
      (footprint "eagle-import:MA08-2")
      (libsource (lib "eagle-import") (part "MA08-2"))
    )
    (comp (ref "SV3")
      (value "MA08-2")
      (footprint "eagle-import:MA08-2")
      (libsource (lib "eagle-import") (part "MA08-2"))
    )
    (comp (ref "SV4")
      (value "MA08-2")
      (footprint "eagle-import:MA08-2")
      (libsource (lib "eagle-import") (part "MA08-2"))
    )
    (comp (ref "5V")
      (value "PINHD-1X2")
      (footprint "eagle-import:1X02")
      (libsource (lib "eagle-import") (part "PINHD-1X2"))
    )
    (comp (ref "A2")
      (value "PINHD-1X2")
      (footprint "eagle-import:1X02")
      (libsource (lib "eagle-import") (part "PINHD-1X2"))
    )
    (comp (ref "B2")
      (value "PINHD-1X2")
      (footprint "eagle-import:1X02")
      (libsource (lib "eagle-import") (part "PINHD-1X2"))
    )
    (comp (ref "C2")
      (value "PINHD-1X2")
      (footprint "eagle-import:1X02")
      (libsource (lib "eagle-import") (part "PINHD-1X2"))
    )
    (comp (ref "GND")
      (value "1,6/0,9")
      (footprint "eagle-import:1,6_0,9")
      (libsource (lib "eagle-import") (part "1,6/0,9"))
    )
    (comp (ref "IC9")
      (value "78XXL")
      (footprint "eagle-import:78XXL")
      (libsource (lib "eagle-import") (part "78XXL"))
    )
    (comp (ref "IC10")
      (value "79XXL")
      (footprint "eagle-import:79XXL")
      (libsource (lib "eagle-import") (part "79XXL"))
    )
    (comp (ref "R321")
      (value "R-US_0207/2V")
      (footprint "eagle-import:0207_2V")
      (libsource (lib "eagle-import") (part "R-US_0207/2V"))
    )
    (comp (ref "R323")
      (value "R-US_0207/2V")
      (footprint "eagle-import:0207_2V")
      (libsource (lib "eagle-import") (part "R-US_0207/2V"))
    )
    (comp (ref "SIDE1")
      (value "MA17-2")
      (footprint "eagle-import:MA17-2")
      (libsource (lib "eagle-import") (part "MA17-2"))
    )
    (comp (ref "SIDE2")
      (value "MA17-2")
      (footprint "eagle-import:MA17-2")
      (libsource (lib "eagle-import") (part "MA17-2"))
    )
    (comp (ref "T1")
      (value "PINHD-1X2")
      (footprint "eagle-import:1X02")
      (libsource (lib "eagle-import") (part "PINHD-1X2"))
    )
    (comp (ref "THR")
      (value "R-TRIMMT18")
      (footprint "eagle-import:RTRIMT18")
      (libsource (lib "eagle-import") (part "R-TRIMMT18"))
    )
    (comp (ref "THR_TP")
      (value "1,6/0,9")
      (footprint "eagle-import:1,6_0,9")
      (libsource (lib "eagle-import") (part "1,6/0,9"))
    )
    (comp (ref "V+")
      (value "1,6/0,9")
      (footprint "eagle-import:1,6_0,9")
      (libsource (lib "eagle-import") (part "1,6/0,9"))
    )
    (comp (ref "V-")
      (value "1,6/0,9")
      (footprint "eagle-import:1,6_0,9")
      (libsource (lib "eagle-import") (part "1,6/0,9"))
    )
    (comp (ref "D1")
      (value "1N5229B")
      (footprint "eagle-import:ZDIO-2.5")
      (libsource (lib "eagle-import") (part "ZENER-DIODEZD-2.5"))
    )
    (comp (ref "D4")
      (value "1N5229B")
      (footprint "eagle-import:ZDIO-2.5")
      (libsource (lib "eagle-import") (part "ZENER-DIODEZD-2.5"))
    )
    (comp (ref "D5")
      (value "1N5229B")
      (footprint "eagle-import:ZDIO-2.5")
      (libsource (lib "eagle-import") (part "ZENER-DIODEZD-2.5"))
    )
    (comp (ref "D7")
      (value "1N5229B")
      (footprint "eagle-import:ZDIO-2.5")
      (libsource (lib "eagle-import") (part "ZENER-DIODEZD-2.5"))
    )
    (comp (ref "D8")
      (value "1N5229B")
      (footprint "eagle-import:ZDIO-2.5")
      (libsource (lib "eagle-import") (part "ZENER-DIODEZD-2.5"))
    )
    (comp (ref "D40")
      (value "1N5229B")
      (footprint "eagle-import:ZDIO-2.5")
      (libsource (lib "eagle-import") (part "ZENER-DIODEZD-2.5"))
    )
    (comp (ref "D41")
      (value "1N5229B")
      (footprint "eagle-import:ZDIO-2.5")
      (libsource (lib "eagle-import") (part "ZENER-DIODEZD-2.5"))
    )
    (comp (ref "D42")
      (value "1N5229B")
      (footprint "eagle-import:ZDIO-2.5")
      (libsource (lib "eagle-import") (part "ZENER-DIODEZD-2.5"))
    )
    (comp (ref "D43")
      (value "1N5229B")
      (footprint "eagle-import:ZDIO-2.5")
      (libsource (lib "eagle-import") (part "ZENER-DIODEZD-2.5"))
    )
    (comp (ref "D44")
      (value "1N5229B")
      (footprint "eagle-import:ZDIO-2.5")
      (libsource (lib "eagle-import") (part "ZENER-DIODEZD-2.5"))
    )
    (comp (ref "D45")
      (value "1N5229B")
      (footprint "eagle-import:ZDIO-2.5")
      (libsource (lib "eagle-import") (part "ZENER-DIODEZD-2.5"))
    )
    (comp (ref "D46")
      (value "1N5229B")
      (footprint "eagle-import:ZDIO-2.5")
      (libsource (lib "eagle-import") (part "ZENER-DIODEZD-2.5"))
    )
    (comp (ref "D47")
      (value "1N5229B")
      (footprint "eagle-import:ZDIO-2.5")
      (libsource (lib "eagle-import") (part "ZENER-DIODEZD-2.5"))
    )
    (comp (ref "D48")
      (value "1N5229B")
      (footprint "eagle-import:ZDIO-2.5")
      (libsource (lib "eagle-import") (part "ZENER-DIODEZD-2.5"))
    )
    (comp (ref "D49")
      (value "1N5229B")
      (footprint "eagle-import:ZDIO-2.5")
      (libsource (lib "eagle-import") (part "ZENER-DIODEZD-2.5"))
    )
    (comp (ref "D50")
      (value "1N5229B")
      (footprint "eagle-import:ZDIO-2.5")
      (libsource (lib "eagle-import") (part "ZENER-DIODEZD-2.5"))
    )
    (comp (ref "D51")
      (value "1N5229B")
      (footprint "eagle-import:ZDIO-2.5")
      (libsource (lib "eagle-import") (part "ZENER-DIODEZD-2.5"))
    )
    (comp (ref "D52")
      (value "1N5229B")
      (footprint "eagle-import:ZDIO-2.5")
      (libsource (lib "eagle-import") (part "ZENER-DIODEZD-2.5"))
    )
    (comp (ref "D53")
      (value "1N5229B")
      (footprint "eagle-import:ZDIO-2.5")
      (libsource (lib "eagle-import") (part "ZENER-DIODEZD-2.5"))
    )
    (comp (ref "D54")
      (value "1N5229B")
      (footprint "eagle-import:ZDIO-2.5")
      (libsource (lib "eagle-import") (part "ZENER-DIODEZD-2.5"))
    )
    (comp (ref "D55")
      (value "1N5229B")
      (footprint "eagle-import:ZDIO-2.5")
      (libsource (lib "eagle-import") (part "ZENER-DIODEZD-2.5"))
    )
    (comp (ref "D56")
      (value "1N5229B")
      (footprint "eagle-import:ZDIO-2.5")
      (libsource (lib "eagle-import") (part "ZENER-DIODEZD-2.5"))
    )
    (comp (ref "D57")
      (value "1N5229B")
      (footprint "eagle-import:ZDIO-2.5")
      (libsource (lib "eagle-import") (part "ZENER-DIODEZD-2.5"))
    )
    (comp (ref "D58")
      (value "1N5229B")
      (footprint "eagle-import:ZDIO-2.5")
      (libsource (lib "eagle-import") (part "ZENER-DIODEZD-2.5"))
    )
    (comp (ref "D59")
      (value "1N5229B")
      (footprint "eagle-import:ZDIO-2.5")
      (libsource (lib "eagle-import") (part "ZENER-DIODEZD-2.5"))
    )
    (comp (ref "D60")
      (value "1N5229B")
      (footprint "eagle-import:ZDIO-2.5")
      (libsource (lib "eagle-import") (part "ZENER-DIODEZD-2.5"))
    )
    (comp (ref "D61")
      (value "1N5229B")
      (footprint "eagle-import:ZDIO-2.5")
      (libsource (lib "eagle-import") (part "ZENER-DIODEZD-2.5"))
    )
    (comp (ref "D62")
      (value "1N5229B")
      (footprint "eagle-import:ZDIO-2.5")
      (libsource (lib "eagle-import") (part "ZENER-DIODEZD-2.5"))
    )
    (comp (ref "D63")
      (value "1N5229B")
      (footprint "eagle-import:ZDIO-2.5")
      (libsource (lib "eagle-import") (part "ZENER-DIODEZD-2.5"))
    )
    (comp (ref "D64")
      (value "1N5229B")
      (footprint "eagle-import:ZDIO-2.5")
      (libsource (lib "eagle-import") (part "ZENER-DIODEZD-2.5"))
    )
    (comp (ref "D65")
      (value "1N5229B")
      (footprint "eagle-import:ZDIO-2.5")
      (libsource (lib "eagle-import") (part "ZENER-DIODEZD-2.5"))
    )
    (comp (ref "D66")
      (value "1N5229B")
      (footprint "eagle-import:ZDIO-2.5")
      (libsource (lib "eagle-import") (part "ZENER-DIODEZD-2.5"))
    )
    (comp (ref "D129")
      (value "1N5225/3V")
      (footprint "eagle-import:ZDIO-2.5")
      (libsource (lib "eagle-import") (part "ZENER-DIODEZD-2.5"))
    )
    (comp (ref "D130")
      (value "1N5225/3V")
      (footprint "eagle-import:ZDIO-2.5")
      (libsource (lib "eagle-import") (part "ZENER-DIODEZD-2.5"))
    )
    (comp (ref "D131")
      (value "1N5225/3V")
      (footprint "eagle-import:ZDIO-2.5")
      (libsource (lib "eagle-import") (part "ZENER-DIODEZD-2.5"))
    )
    (comp (ref "D132")
      (value "1N5225/3V")
      (footprint "eagle-import:ZDIO-2.5")
      (libsource (lib "eagle-import") (part "ZENER-DIODEZD-2.5"))
    )
    (comp (ref "D133")
      (value "1N5225/3V")
      (footprint "eagle-import:ZDIO-2.5")
      (libsource (lib "eagle-import") (part "ZENER-DIODEZD-2.5"))
    )
    (comp (ref "D134")
      (value "1N5225/3V")
      (footprint "eagle-import:ZDIO-2.5")
      (libsource (lib "eagle-import") (part "ZENER-DIODEZD-2.5"))
    )
    (comp (ref "D135")
      (value "1N5225/3V")
      (footprint "eagle-import:ZDIO-2.5")
      (libsource (lib "eagle-import") (part "ZENER-DIODEZD-2.5"))
    )
    (comp (ref "D136")
      (value "1N5225/3V")
      (footprint "eagle-import:ZDIO-2.5")
      (libsource (lib "eagle-import") (part "ZENER-DIODEZD-2.5"))
    )
    (comp (ref "D137")
      (value "1N5225/3V")
      (footprint "eagle-import:ZDIO-2.5")
      (libsource (lib "eagle-import") (part "ZENER-DIODEZD-2.5"))
    )
    (comp (ref "D138")
      (value "1N5225/3V")
      (footprint "eagle-import:ZDIO-2.5")
      (libsource (lib "eagle-import") (part "ZENER-DIODEZD-2.5"))
    )
    (comp (ref "D139")
      (value "1N5225/3V")
      (footprint "eagle-import:ZDIO-2.5")
      (libsource (lib "eagle-import") (part "ZENER-DIODEZD-2.5"))
    )
    (comp (ref "D140")
      (value "1N5225/3V")
      (footprint "eagle-import:ZDIO-2.5")
      (libsource (lib "eagle-import") (part "ZENER-DIODEZD-2.5"))
    )
    (comp (ref "D141")
      (value "1N5225/3V")
      (footprint "eagle-import:ZDIO-2.5")
      (libsource (lib "eagle-import") (part "ZENER-DIODEZD-2.5"))
    )
    (comp (ref "D142")
      (value "1N5225/3V")
      (footprint "eagle-import:ZDIO-2.5")
      (libsource (lib "eagle-import") (part "ZENER-DIODEZD-2.5"))
    )
    (comp (ref "D143")
      (value "1N5225/3V")
      (footprint "eagle-import:ZDIO-2.5")
      (libsource (lib "eagle-import") (part "ZENER-DIODEZD-2.5"))
    )
    (comp (ref "D144")
      (value "1N5225/3V")
      (footprint "eagle-import:ZDIO-2.5")
      (libsource (lib "eagle-import") (part "ZENER-DIODEZD-2.5"))
    )
    (comp (ref "D145")
      (value "1N5225/3V")
      (footprint "eagle-import:ZDIO-2.5")
      (libsource (lib "eagle-import") (part "ZENER-DIODEZD-2.5"))
    )
    (comp (ref "D146")
      (value "1N5225/3V")
      (footprint "eagle-import:ZDIO-2.5")
      (libsource (lib "eagle-import") (part "ZENER-DIODEZD-2.5"))
    )
    (comp (ref "D147")
      (value "1N5225/3V")
      (footprint "eagle-import:ZDIO-2.5")
      (libsource (lib "eagle-import") (part "ZENER-DIODEZD-2.5"))
    )
    (comp (ref "D148")
      (value "1N5225/3V")
      (footprint "eagle-import:ZDIO-2.5")
      (libsource (lib "eagle-import") (part "ZENER-DIODEZD-2.5"))
    )
    (comp (ref "D149")
      (value "1N5225/3V")
      (footprint "eagle-import:ZDIO-2.5")
      (libsource (lib "eagle-import") (part "ZENER-DIODEZD-2.5"))
    )
    (comp (ref "D150")
      (value "1N5225/3V")
      (footprint "eagle-import:ZDIO-2.5")
      (libsource (lib "eagle-import") (part "ZENER-DIODEZD-2.5"))
    )
    (comp (ref "D151")
      (value "1N5225/3V")
      (footprint "eagle-import:ZDIO-2.5")
      (libsource (lib "eagle-import") (part "ZENER-DIODEZD-2.5"))
    )
    (comp (ref "D152")
      (value "1N5225/3V")
      (footprint "eagle-import:ZDIO-2.5")
      (libsource (lib "eagle-import") (part "ZENER-DIODEZD-2.5"))
    )
    (comp (ref "D153")
      (value "1N5225/3V")
      (footprint "eagle-import:ZDIO-2.5")
      (libsource (lib "eagle-import") (part "ZENER-DIODEZD-2.5"))
    )
    (comp (ref "D154")
      (value "1N5225/3V")
      (footprint "eagle-import:ZDIO-2.5")
      (libsource (lib "eagle-import") (part "ZENER-DIODEZD-2.5"))
    )
    (comp (ref "D155")
      (value "1N5225/3V")
      (footprint "eagle-import:ZDIO-2.5")
      (libsource (lib "eagle-import") (part "ZENER-DIODEZD-2.5"))
    )
    (comp (ref "D156")
      (value "1N5225/3V")
      (footprint "eagle-import:ZDIO-2.5")
      (libsource (lib "eagle-import") (part "ZENER-DIODEZD-2.5"))
    )
    (comp (ref "D157")
      (value "1N5225/3V")
      (footprint "eagle-import:ZDIO-2.5")
      (libsource (lib "eagle-import") (part "ZENER-DIODEZD-2.5"))
    )
    (comp (ref "D158")
      (value "1N5225/3V")
      (footprint "eagle-import:ZDIO-2.5")
      (libsource (lib "eagle-import") (part "ZENER-DIODEZD-2.5"))
    )
    (comp (ref "D159")
      (value "1N5225/3V")
      (footprint "eagle-import:ZDIO-2.5")
      (libsource (lib "eagle-import") (part "ZENER-DIODEZD-2.5"))
    )
    (comp (ref "D160")
      (value "1N5225/3V")
      (footprint "eagle-import:ZDIO-2.5")
      (libsource (lib "eagle-import") (part "ZENER-DIODEZD-2.5"))
    )
    (comp (ref "Q3")
      (value "BS170")
      (footprint "eagle-import:SOT54E")
      (libsource (lib "eagle-import") (part "BS170"))
    )
    (comp (ref "Q4")
      (value "BS170")
      (footprint "eagle-import:SOT54E")
      (libsource (lib "eagle-import") (part "BS170"))
    )
    (comp (ref "Q5")
      (value "BS170")
      (footprint "eagle-import:SOT54E")
      (libsource (lib "eagle-import") (part "BS170"))
    )
    (comp (ref "Q6")
      (value "BS170")
      (footprint "eagle-import:SOT54E")
      (libsource (lib "eagle-import") (part "BS170"))
    )
    (comp (ref "Q7")
      (value "BS170")
      (footprint "eagle-import:SOT54E")
      (libsource (lib "eagle-import") (part "BS170"))
    )
    (comp (ref "Q8")
      (value "BS170")
      (footprint "eagle-import:SOT54E")
      (libsource (lib "eagle-import") (part "BS170"))
    )
    (comp (ref "Q9")
      (value "BS170")
      (footprint "eagle-import:SOT54E")
      (libsource (lib "eagle-import") (part "BS170"))
    )
    (comp (ref "Q10")
      (value "BS170")
      (footprint "eagle-import:SOT54E")
      (libsource (lib "eagle-import") (part "BS170"))
    )
    (comp (ref "Q11")
      (value "BS170")
      (footprint "eagle-import:SOT54E")
      (libsource (lib "eagle-import") (part "BS170"))
    )
    (comp (ref "Q12")
      (value "BS170")
      (footprint "eagle-import:SOT54E")
      (libsource (lib "eagle-import") (part "BS170"))
    )
    (comp (ref "Q13")
      (value "BS170")
      (footprint "eagle-import:SOT54E")
      (libsource (lib "eagle-import") (part "BS170"))
    )
    (comp (ref "Q14")
      (value "BS170")
      (footprint "eagle-import:SOT54E")
      (libsource (lib "eagle-import") (part "BS170"))
    )
    (comp (ref "Q15")
      (value "BS170")
      (footprint "eagle-import:SOT54E")
      (libsource (lib "eagle-import") (part "BS170"))
    )
    (comp (ref "Q16")
      (value "BS170")
      (footprint "eagle-import:SOT54E")
      (libsource (lib "eagle-import") (part "BS170"))
    )
    (comp (ref "Q17")
      (value "BS170")
      (footprint "eagle-import:SOT54E")
      (libsource (lib "eagle-import") (part "BS170"))
    )
    (comp (ref "Q18")
      (value "BS170")
      (footprint "eagle-import:SOT54E")
      (libsource (lib "eagle-import") (part "BS170"))
    )
    (comp (ref "Q19")
      (value "BS170")
      (footprint "eagle-import:SOT54E")
      (libsource (lib "eagle-import") (part "BS170"))
    )
    (comp (ref "Q20")
      (value "BS170")
      (footprint "eagle-import:SOT54E")
      (libsource (lib "eagle-import") (part "BS170"))
    )
    (comp (ref "Q21")
      (value "BS170")
      (footprint "eagle-import:SOT54E")
      (libsource (lib "eagle-import") (part "BS170"))
    )
    (comp (ref "Q22")
      (value "BS170")
      (footprint "eagle-import:SOT54E")
      (libsource (lib "eagle-import") (part "BS170"))
    )
    (comp (ref "Q23")
      (value "BS170")
      (footprint "eagle-import:SOT54E")
      (libsource (lib "eagle-import") (part "BS170"))
    )
    (comp (ref "Q24")
      (value "BS170")
      (footprint "eagle-import:SOT54E")
      (libsource (lib "eagle-import") (part "BS170"))
    )
    (comp (ref "Q25")
      (value "BS170")
      (footprint "eagle-import:SOT54E")
      (libsource (lib "eagle-import") (part "BS170"))
    )
    (comp (ref "Q26")
      (value "BS170")
      (footprint "eagle-import:SOT54E")
      (libsource (lib "eagle-import") (part "BS170"))
    )
    (comp (ref "Q27")
      (value "BS170")
      (footprint "eagle-import:SOT54E")
      (libsource (lib "eagle-import") (part "BS170"))
    )
    (comp (ref "Q28")
      (value "BS170")
      (footprint "eagle-import:SOT54E")
      (libsource (lib "eagle-import") (part "BS170"))
    )
    (comp (ref "Q29")
      (value "BS170")
      (footprint "eagle-import:SOT54E")
      (libsource (lib "eagle-import") (part "BS170"))
    )
    (comp (ref "Q30")
      (value "BS170")
      (footprint "eagle-import:SOT54E")
      (libsource (lib "eagle-import") (part "BS170"))
    )
    (comp (ref "Q31")
      (value "BS170")
      (footprint "eagle-import:SOT54E")
      (libsource (lib "eagle-import") (part "BS170"))
    )
    (comp (ref "Q32")
      (value "BS170")
      (footprint "eagle-import:SOT54E")
      (libsource (lib "eagle-import") (part "BS170"))
    )
    (comp (ref "Q33")
      (value "BS170")
      (footprint "eagle-import:SOT54E")
      (libsource (lib "eagle-import") (part "BS170"))
    )
    (comp (ref "Q34")
      (value "BS170")
      (footprint "eagle-import:SOT54E")
      (libsource (lib "eagle-import") (part "BS170"))
    )
    (comp (ref "R2")
      (value "5K")
      (footprint "eagle-import:0207_2V")
      (libsource (lib "eagle-import") (part "R-US_0207/2V"))
    )
    (comp (ref "R4")
      (value "5K")
      (footprint "eagle-import:0207_2V")
      (libsource (lib "eagle-import") (part "R-US_0207/2V"))
    )
    (comp (ref "R8")
      (value "5K")
      (footprint "eagle-import:0207_2V")
      (libsource (lib "eagle-import") (part "R-US_0207/2V"))
    )
    (comp (ref "R9")
      (value "10K")
      (footprint "eagle-import:0207_2V")
      (libsource (lib "eagle-import") (part "R-US_0207/2V"))
    )
    (comp (ref "R13")
      (value "5K")
      (footprint "eagle-import:0207_2V")
      (libsource (lib "eagle-import") (part "R-US_0207/2V"))
    )
    (comp (ref "R14")
      (value "10K")
      (footprint "eagle-import:0207_2V")
      (libsource (lib "eagle-import") (part "R-US_0207/2V"))
    )
    (comp (ref "R139")
      (value "5K")
      (footprint "eagle-import:0207_2V")
      (libsource (lib "eagle-import") (part "R-US_0207/2V"))
    )
    (comp (ref "R141")
      (value "5K")
      (footprint "eagle-import:0207_2V")
      (libsource (lib "eagle-import") (part "R-US_0207/2V"))
    )
    (comp (ref "R142")
      (value "10K")
      (footprint "eagle-import:0207_2V")
      (libsource (lib "eagle-import") (part "R-US_0207/2V"))
    )
    (comp (ref "R143")
      (value "5K")
      (footprint "eagle-import:0207_2V")
      (libsource (lib "eagle-import") (part "R-US_0207/2V"))
    )
    (comp (ref "R145")
      (value "5K")
      (footprint "eagle-import:0207_2V")
      (libsource (lib "eagle-import") (part "R-US_0207/2V"))
    )
    (comp (ref "R146")
      (value "10K")
      (footprint "eagle-import:0207_2V")
      (libsource (lib "eagle-import") (part "R-US_0207/2V"))
    )
    (comp (ref "R147")
      (value "5K")
      (footprint "eagle-import:0207_2V")
      (libsource (lib "eagle-import") (part "R-US_0207/2V"))
    )
    (comp (ref "R149")
      (value "5K")
      (footprint "eagle-import:0207_2V")
      (libsource (lib "eagle-import") (part "R-US_0207/2V"))
    )
    (comp (ref "R150")
      (value "10K")
      (footprint "eagle-import:0207_2V")
      (libsource (lib "eagle-import") (part "R-US_0207/2V"))
    )
    (comp (ref "R151")
      (value "5K")
      (footprint "eagle-import:0207_2V")
      (libsource (lib "eagle-import") (part "R-US_0207/2V"))
    )
    (comp (ref "R153")
      (value "5K")
      (footprint "eagle-import:0207_2V")
      (libsource (lib "eagle-import") (part "R-US_0207/2V"))
    )
    (comp (ref "R154")
      (value "10K")
      (footprint "eagle-import:0207_2V")
      (libsource (lib "eagle-import") (part "R-US_0207/2V"))
    )
    (comp (ref "R155")
      (value "5K")
      (footprint "eagle-import:0207_2V")
      (libsource (lib "eagle-import") (part "R-US_0207/2V"))
    )
    (comp (ref "R157")
      (value "5K")
      (footprint "eagle-import:0207_2V")
      (libsource (lib "eagle-import") (part "R-US_0207/2V"))
    )
    (comp (ref "R158")
      (value "10K")
      (footprint "eagle-import:0207_2V")
      (libsource (lib "eagle-import") (part "R-US_0207/2V"))
    )
    (comp (ref "R159")
      (value "5K")
      (footprint "eagle-import:0207_2V")
      (libsource (lib "eagle-import") (part "R-US_0207/2V"))
    )
    (comp (ref "R161")
      (value "5K")
      (footprint "eagle-import:0207_2V")
      (libsource (lib "eagle-import") (part "R-US_0207/2V"))
    )
    (comp (ref "R162")
      (value "10K")
      (footprint "eagle-import:0207_2V")
      (libsource (lib "eagle-import") (part "R-US_0207/2V"))
    )
    (comp (ref "R163")
      (value "5K")
      (footprint "eagle-import:0207_2V")
      (libsource (lib "eagle-import") (part "R-US_0207/2V"))
    )
    (comp (ref "R165")
      (value "5K")
      (footprint "eagle-import:0207_2V")
      (libsource (lib "eagle-import") (part "R-US_0207/2V"))
    )
    (comp (ref "R166")
      (value "10K")
      (footprint "eagle-import:0207_2V")
      (libsource (lib "eagle-import") (part "R-US_0207/2V"))
    )
    (comp (ref "R167")
      (value "5K")
      (footprint "eagle-import:0207_2V")
      (libsource (lib "eagle-import") (part "R-US_0207/2V"))
    )
    (comp (ref "R169")
      (value "5K")
      (footprint "eagle-import:0207_2V")
      (libsource (lib "eagle-import") (part "R-US_0207/2V"))
    )
    (comp (ref "R170")
      (value "10K")
      (footprint "eagle-import:0207_2V")
      (libsource (lib "eagle-import") (part "R-US_0207/2V"))
    )
    (comp (ref "R171")
      (value "5K")
      (footprint "eagle-import:0207_2V")
      (libsource (lib "eagle-import") (part "R-US_0207/2V"))
    )
    (comp (ref "R173")
      (value "5K")
      (footprint "eagle-import:0207_2V")
      (libsource (lib "eagle-import") (part "R-US_0207/2V"))
    )
    (comp (ref "R174")
      (value "10K")
      (footprint "eagle-import:0207_2V")
      (libsource (lib "eagle-import") (part "R-US_0207/2V"))
    )
    (comp (ref "R175")
      (value "5K")
      (footprint "eagle-import:0207_2V")
      (libsource (lib "eagle-import") (part "R-US_0207/2V"))
    )
    (comp (ref "R177")
      (value "5K")
      (footprint "eagle-import:0207_2V")
      (libsource (lib "eagle-import") (part "R-US_0207/2V"))
    )
    (comp (ref "R178")
      (value "10K")
      (footprint "eagle-import:0207_2V")
      (libsource (lib "eagle-import") (part "R-US_0207/2V"))
    )
    (comp (ref "R179")
      (value "5K")
      (footprint "eagle-import:0207_2V")
      (libsource (lib "eagle-import") (part "R-US_0207/2V"))
    )
    (comp (ref "R181")
      (value "5K")
      (footprint "eagle-import:0207_2V")
      (libsource (lib "eagle-import") (part "R-US_0207/2V"))
    )
    (comp (ref "R182")
      (value "10K")
      (footprint "eagle-import:0207_2V")
      (libsource (lib "eagle-import") (part "R-US_0207/2V"))
    )
    (comp (ref "R183")
      (value "5K")
      (footprint "eagle-import:0207_2V")
      (libsource (lib "eagle-import") (part "R-US_0207/2V"))
    )
    (comp (ref "R185")
      (value "5K")
      (footprint "eagle-import:0207_2V")
      (libsource (lib "eagle-import") (part "R-US_0207/2V"))
    )
    (comp (ref "R186")
      (value "10K")
      (footprint "eagle-import:0207_2V")
      (libsource (lib "eagle-import") (part "R-US_0207/2V"))
    )
    (comp (ref "R187")
      (value "5K")
      (footprint "eagle-import:0207_2V")
      (libsource (lib "eagle-import") (part "R-US_0207/2V"))
    )
    (comp (ref "R189")
      (value "5K")
      (footprint "eagle-import:0207_2V")
      (libsource (lib "eagle-import") (part "R-US_0207/2V"))
    )
    (comp (ref "R190")
      (value "10K")
      (footprint "eagle-import:0207_2V")
      (libsource (lib "eagle-import") (part "R-US_0207/2V"))
    )
    (comp (ref "R191")
      (value "5K")
      (footprint "eagle-import:0207_2V")
      (libsource (lib "eagle-import") (part "R-US_0207/2V"))
    )
    (comp (ref "R193")
      (value "5K")
      (footprint "eagle-import:0207_2V")
      (libsource (lib "eagle-import") (part "R-US_0207/2V"))
    )
    (comp (ref "R194")
      (value "10K")
      (footprint "eagle-import:0207_2V")
      (libsource (lib "eagle-import") (part "R-US_0207/2V"))
    )
    (comp (ref "R195")
      (value "5K")
      (footprint "eagle-import:0207_2V")
      (libsource (lib "eagle-import") (part "R-US_0207/2V"))
    )
    (comp (ref "R197")
      (value "5K")
      (footprint "eagle-import:0207_2V")
      (libsource (lib "eagle-import") (part "R-US_0207/2V"))
    )
    (comp (ref "R198")
      (value "10K")
      (footprint "eagle-import:0207_2V")
      (libsource (lib "eagle-import") (part "R-US_0207/2V"))
    )
    (comp (ref "R199")
      (value "5K")
      (footprint "eagle-import:0207_2V")
      (libsource (lib "eagle-import") (part "R-US_0207/2V"))
    )
    (comp (ref "R201")
      (value "5K")
      (footprint "eagle-import:0207_2V")
      (libsource (lib "eagle-import") (part "R-US_0207/2V"))
    )
    (comp (ref "R202")
      (value "10K")
      (footprint "eagle-import:0207_2V")
      (libsource (lib "eagle-import") (part "R-US_0207/2V"))
    )
    (comp (ref "R203")
      (value "5K")
      (footprint "eagle-import:0207_2V")
      (libsource (lib "eagle-import") (part "R-US_0207/2V"))
    )
    (comp (ref "R205")
      (value "5K")
      (footprint "eagle-import:0207_2V")
      (libsource (lib "eagle-import") (part "R-US_0207/2V"))
    )
    (comp (ref "R206")
      (value "10K")
      (footprint "eagle-import:0207_2V")
      (libsource (lib "eagle-import") (part "R-US_0207/2V"))
    )
    (comp (ref "R207")
      (value "5K")
      (footprint "eagle-import:0207_2V")
      (libsource (lib "eagle-import") (part "R-US_0207/2V"))
    )
    (comp (ref "R209")
      (value "5K")
      (footprint "eagle-import:0207_2V")
      (libsource (lib "eagle-import") (part "R-US_0207/2V"))
    )
    (comp (ref "R210")
      (value "10K")
      (footprint "eagle-import:0207_2V")
      (libsource (lib "eagle-import") (part "R-US_0207/2V"))
    )
    (comp (ref "R211")
      (value "5K")
      (footprint "eagle-import:0207_2V")
      (libsource (lib "eagle-import") (part "R-US_0207/2V"))
    )
    (comp (ref "R213")
      (value "5K")
      (footprint "eagle-import:0207_2V")
      (libsource (lib "eagle-import") (part "R-US_0207/2V"))
    )
    (comp (ref "R214")
      (value "10K")
      (footprint "eagle-import:0207_2V")
      (libsource (lib "eagle-import") (part "R-US_0207/2V"))
    )
    (comp (ref "R215")
      (value "5K")
      (footprint "eagle-import:0207_2V")
      (libsource (lib "eagle-import") (part "R-US_0207/2V"))
    )
    (comp (ref "R217")
      (value "5K")
      (footprint "eagle-import:0207_2V")
      (libsource (lib "eagle-import") (part "R-US_0207/2V"))
    )
    (comp (ref "R218")
      (value "10K")
      (footprint "eagle-import:0207_2V")
      (libsource (lib "eagle-import") (part "R-US_0207/2V"))
    )
    (comp (ref "R219")
      (value "5K")
      (footprint "eagle-import:0207_2V")
      (libsource (lib "eagle-import") (part "R-US_0207/2V"))
    )
    (comp (ref "R221")
      (value "5K")
      (footprint "eagle-import:0207_2V")
      (libsource (lib "eagle-import") (part "R-US_0207/2V"))
    )
    (comp (ref "R222")
      (value "10K")
      (footprint "eagle-import:0207_2V")
      (libsource (lib "eagle-import") (part "R-US_0207/2V"))
    )
    (comp (ref "R223")
      (value "5K")
      (footprint "eagle-import:0207_2V")
      (libsource (lib "eagle-import") (part "R-US_0207/2V"))
    )
    (comp (ref "R225")
      (value "5K")
      (footprint "eagle-import:0207_2V")
      (libsource (lib "eagle-import") (part "R-US_0207/2V"))
    )
    (comp (ref "R226")
      (value "10K")
      (footprint "eagle-import:0207_2V")
      (libsource (lib "eagle-import") (part "R-US_0207/2V"))
    )
    (comp (ref "R227")
      (value "5K")
      (footprint "eagle-import:0207_2V")
      (libsource (lib "eagle-import") (part "R-US_0207/2V"))
    )
    (comp (ref "R229")
      (value "5K")
      (footprint "eagle-import:0207_2V")
      (libsource (lib "eagle-import") (part "R-US_0207/2V"))
    )
    (comp (ref "R230")
      (value "10K")
      (footprint "eagle-import:0207_2V")
      (libsource (lib "eagle-import") (part "R-US_0207/2V"))
    )
    (comp (ref "R231")
      (value "5K")
      (footprint "eagle-import:0207_2V")
      (libsource (lib "eagle-import") (part "R-US_0207/2V"))
    )
    (comp (ref "R233")
      (value "5K")
      (footprint "eagle-import:0207_2V")
      (libsource (lib "eagle-import") (part "R-US_0207/2V"))
    )
    (comp (ref "R234")
      (value "10K")
      (footprint "eagle-import:0207_2V")
      (libsource (lib "eagle-import") (part "R-US_0207/2V"))
    )
    (comp (ref "R235")
      (value "5K")
      (footprint "eagle-import:0207_2V")
      (libsource (lib "eagle-import") (part "R-US_0207/2V"))
    )
    (comp (ref "R237")
      (value "5K")
      (footprint "eagle-import:0207_2V")
      (libsource (lib "eagle-import") (part "R-US_0207/2V"))
    )
    (comp (ref "R238")
      (value "10K")
      (footprint "eagle-import:0207_2V")
      (libsource (lib "eagle-import") (part "R-US_0207/2V"))
    )
    (comp (ref "R239")
      (value "5K")
      (footprint "eagle-import:0207_2V")
      (libsource (lib "eagle-import") (part "R-US_0207/2V"))
    )
    (comp (ref "R241")
      (value "5K")
      (footprint "eagle-import:0207_2V")
      (libsource (lib "eagle-import") (part "R-US_0207/2V"))
    )
    (comp (ref "R242")
      (value "10K")
      (footprint "eagle-import:0207_2V")
      (libsource (lib "eagle-import") (part "R-US_0207/2V"))
    )
    (comp (ref "R243")
      (value "5K")
      (footprint "eagle-import:0207_2V")
      (libsource (lib "eagle-import") (part "R-US_0207/2V"))
    )
    (comp (ref "R245")
      (value "5K")
      (footprint "eagle-import:0207_2V")
      (libsource (lib "eagle-import") (part "R-US_0207/2V"))
    )
    (comp (ref "R246")
      (value "10K")
      (footprint "eagle-import:0207_2V")
      (libsource (lib "eagle-import") (part "R-US_0207/2V"))
    )
    (comp (ref "R247")
      (value "5K")
      (footprint "eagle-import:0207_2V")
      (libsource (lib "eagle-import") (part "R-US_0207/2V"))
    )
    (comp (ref "R249")
      (value "5K")
      (footprint "eagle-import:0207_2V")
      (libsource (lib "eagle-import") (part "R-US_0207/2V"))
    )
    (comp (ref "R250")
      (value "10K")
      (footprint "eagle-import:0207_2V")
      (libsource (lib "eagle-import") (part "R-US_0207/2V"))
    )
    (comp (ref "R251")
      (value "5K")
      (footprint "eagle-import:0207_2V")
      (libsource (lib "eagle-import") (part "R-US_0207/2V"))
    )
    (comp (ref "R253")
      (value "5K")
      (footprint "eagle-import:0207_2V")
      (libsource (lib "eagle-import") (part "R-US_0207/2V"))
    )
    (comp (ref "R254")
      (value "10K")
      (footprint "eagle-import:0207_2V")
      (libsource (lib "eagle-import") (part "R-US_0207/2V"))
    )
    (comp (ref "R255")
      (value "5K")
      (footprint "eagle-import:0207_2V")
      (libsource (lib "eagle-import") (part "R-US_0207/2V"))
    )
    (comp (ref "R257")
      (value "5K")
      (footprint "eagle-import:0207_2V")
      (libsource (lib "eagle-import") (part "R-US_0207/2V"))
    )
    (comp (ref "R258")
      (value "10K")
      (footprint "eagle-import:0207_2V")
      (libsource (lib "eagle-import") (part "R-US_0207/2V"))
    )
    (comp (ref "SV5")
      (value "MA08-2")
      (footprint "eagle-import:MA08-2")
      (libsource (lib "eagle-import") (part "MA08-2"))
    )
    (comp (ref "SV6")
      (value "MA08-2")
      (footprint "eagle-import:MA08-2")
      (libsource (lib "eagle-import") (part "MA08-2"))
    )
    (comp (ref "D2")
      (value "1N5229B")
      (footprint "eagle-import:ZDIO-2.5")
      (libsource (lib "eagle-import") (part "ZENER-DIODEZD-2.5"))
    )
    (comp (ref "D9")
      (value "1N5229B")
      (footprint "eagle-import:ZDIO-2.5")
      (libsource (lib "eagle-import") (part "ZENER-DIODEZD-2.5"))
    )
    (comp (ref "D10")
      (value "1N5229B")
      (footprint "eagle-import:ZDIO-2.5")
      (libsource (lib "eagle-import") (part "ZENER-DIODEZD-2.5"))
    )
    (comp (ref "D11")
      (value "1N5229B")
      (footprint "eagle-import:ZDIO-2.5")
      (libsource (lib "eagle-import") (part "ZENER-DIODEZD-2.5"))
    )
    (comp (ref "D12")
      (value "1N5229B")
      (footprint "eagle-import:ZDIO-2.5")
      (libsource (lib "eagle-import") (part "ZENER-DIODEZD-2.5"))
    )
    (comp (ref "D13")
      (value "1N5229B")
      (footprint "eagle-import:ZDIO-2.5")
      (libsource (lib "eagle-import") (part "ZENER-DIODEZD-2.5"))
    )
    (comp (ref "D14")
      (value "1N5229B")
      (footprint "eagle-import:ZDIO-2.5")
      (libsource (lib "eagle-import") (part "ZENER-DIODEZD-2.5"))
    )
    (comp (ref "D15")
      (value "1N5229B")
      (footprint "eagle-import:ZDIO-2.5")
      (libsource (lib "eagle-import") (part "ZENER-DIODEZD-2.5"))
    )
    (comp (ref "D16")
      (value "1N5229B")
      (footprint "eagle-import:ZDIO-2.5")
      (libsource (lib "eagle-import") (part "ZENER-DIODEZD-2.5"))
    )
    (comp (ref "D17")
      (value "1N5229B")
      (footprint "eagle-import:ZDIO-2.5")
      (libsource (lib "eagle-import") (part "ZENER-DIODEZD-2.5"))
    )
    (comp (ref "D18")
      (value "1N5229B")
      (footprint "eagle-import:ZDIO-2.5")
      (libsource (lib "eagle-import") (part "ZENER-DIODEZD-2.5"))
    )
    (comp (ref "D19")
      (value "1N5229B")
      (footprint "eagle-import:ZDIO-2.5")
      (libsource (lib "eagle-import") (part "ZENER-DIODEZD-2.5"))
    )
    (comp (ref "D20")
      (value "1N5229B")
      (footprint "eagle-import:ZDIO-2.5")
      (libsource (lib "eagle-import") (part "ZENER-DIODEZD-2.5"))
    )
    (comp (ref "D21")
      (value "1N5229B")
      (footprint "eagle-import:ZDIO-2.5")
      (libsource (lib "eagle-import") (part "ZENER-DIODEZD-2.5"))
    )
    (comp (ref "D22")
      (value "1N5229B")
      (footprint "eagle-import:ZDIO-2.5")
      (libsource (lib "eagle-import") (part "ZENER-DIODEZD-2.5"))
    )
    (comp (ref "D23")
      (value "1N5229B")
      (footprint "eagle-import:ZDIO-2.5")
      (libsource (lib "eagle-import") (part "ZENER-DIODEZD-2.5"))
    )
    (comp (ref "D24")
      (value "1N5229B")
      (footprint "eagle-import:ZDIO-2.5")
      (libsource (lib "eagle-import") (part "ZENER-DIODEZD-2.5"))
    )
    (comp (ref "D25")
      (value "1N5229B")
      (footprint "eagle-import:ZDIO-2.5")
      (libsource (lib "eagle-import") (part "ZENER-DIODEZD-2.5"))
    )
    (comp (ref "D26")
      (value "1N5229B")
      (footprint "eagle-import:ZDIO-2.5")
      (libsource (lib "eagle-import") (part "ZENER-DIODEZD-2.5"))
    )
    (comp (ref "D27")
      (value "1N5229B")
      (footprint "eagle-import:ZDIO-2.5")
      (libsource (lib "eagle-import") (part "ZENER-DIODEZD-2.5"))
    )
    (comp (ref "D28")
      (value "1N5229B")
      (footprint "eagle-import:ZDIO-2.5")
      (libsource (lib "eagle-import") (part "ZENER-DIODEZD-2.5"))
    )
    (comp (ref "D29")
      (value "1N5229B")
      (footprint "eagle-import:ZDIO-2.5")
      (libsource (lib "eagle-import") (part "ZENER-DIODEZD-2.5"))
    )
    (comp (ref "D30")
      (value "1N5229B")
      (footprint "eagle-import:ZDIO-2.5")
      (libsource (lib "eagle-import") (part "ZENER-DIODEZD-2.5"))
    )
    (comp (ref "D31")
      (value "1N5229B")
      (footprint "eagle-import:ZDIO-2.5")
      (libsource (lib "eagle-import") (part "ZENER-DIODEZD-2.5"))
    )
    (comp (ref "D32")
      (value "1N5229B")
      (footprint "eagle-import:ZDIO-2.5")
      (libsource (lib "eagle-import") (part "ZENER-DIODEZD-2.5"))
    )
    (comp (ref "D33")
      (value "1N5229B")
      (footprint "eagle-import:ZDIO-2.5")
      (libsource (lib "eagle-import") (part "ZENER-DIODEZD-2.5"))
    )
    (comp (ref "D34")
      (value "1N5229B")
      (footprint "eagle-import:ZDIO-2.5")
      (libsource (lib "eagle-import") (part "ZENER-DIODEZD-2.5"))
    )
    (comp (ref "D35")
      (value "1N5229B")
      (footprint "eagle-import:ZDIO-2.5")
      (libsource (lib "eagle-import") (part "ZENER-DIODEZD-2.5"))
    )
    (comp (ref "D36")
      (value "1N5229B")
      (footprint "eagle-import:ZDIO-2.5")
      (libsource (lib "eagle-import") (part "ZENER-DIODEZD-2.5"))
    )
    (comp (ref "D37")
      (value "1N5229B")
      (footprint "eagle-import:ZDIO-2.5")
      (libsource (lib "eagle-import") (part "ZENER-DIODEZD-2.5"))
    )
    (comp (ref "D38")
      (value "1N5229B")
      (footprint "eagle-import:ZDIO-2.5")
      (libsource (lib "eagle-import") (part "ZENER-DIODEZD-2.5"))
    )
    (comp (ref "D39")
      (value "1N5229B")
      (footprint "eagle-import:ZDIO-2.5")
      (libsource (lib "eagle-import") (part "ZENER-DIODEZD-2.5"))
    )
    (comp (ref "IC1")
      (value "LM139N")
      (footprint "eagle-import:DIL14")
      (libsource (lib "eagle-import") (part "LM339N"))
    )
    (comp (ref "IC2")
      (value "LM139N")
      (footprint "eagle-import:DIL14")
      (libsource (lib "eagle-import") (part "LM339N"))
    )
    (comp (ref "IC3")
      (value "LM139N")
      (footprint "eagle-import:DIL14")
      (libsource (lib "eagle-import") (part "LM339N"))
    )
    (comp (ref "IC4")
      (value "LM139N")
      (footprint "eagle-import:DIL14")
      (libsource (lib "eagle-import") (part "LM339N"))
    )
    (comp (ref "IC5")
      (value "LM139N")
      (footprint "eagle-import:DIL14")
      (libsource (lib "eagle-import") (part "LM339N"))
    )
    (comp (ref "IC6")
      (value "LM139N")
      (footprint "eagle-import:DIL14")
      (libsource (lib "eagle-import") (part "LM339N"))
    )
    (comp (ref "IC7")
      (value "LM139N")
      (footprint "eagle-import:DIL14")
      (libsource (lib "eagle-import") (part "LM339N"))
    )
    (comp (ref "IC8")
      (value "LM139N")
      (footprint "eagle-import:DIL14")
      (libsource (lib "eagle-import") (part "LM339N"))
    )
    (comp (ref "JP1")
      (value "PINHD-1X2")
      (footprint "eagle-import:1X02")
      (libsource (lib "eagle-import") (part "PINHD-1X2"))
    )
    (comp (ref "JP3")
      (value "PINHD-1X2")
      (footprint "eagle-import:1X02")
      (libsource (lib "eagle-import") (part "PINHD-1X2"))
    )
    (comp (ref "JP4")
      (value "PINHD-1X2")
      (footprint "eagle-import:1X02")
      (libsource (lib "eagle-import") (part "PINHD-1X2"))
    )
    (comp (ref "JP5")
      (value "PINHD-1X2")
      (footprint "eagle-import:1X02")
      (libsource (lib "eagle-import") (part "PINHD-1X2"))
    )
    (comp (ref "JP6")
      (value "PINHD-1X2")
      (footprint "eagle-import:1X02")
      (libsource (lib "eagle-import") (part "PINHD-1X2"))
    )
    (comp (ref "JP7")
      (value "PINHD-1X2")
      (footprint "eagle-import:1X02")
      (libsource (lib "eagle-import") (part "PINHD-1X2"))
    )
    (comp (ref "JP8")
      (value "PINHD-1X2")
      (footprint "eagle-import:1X02")
      (libsource (lib "eagle-import") (part "PINHD-1X2"))
    )
    (comp (ref "JP9")
      (value "PINHD-1X2")
      (footprint "eagle-import:1X02")
      (libsource (lib "eagle-import") (part "PINHD-1X2"))
    )
    (comp (ref "JP10")
      (value "PINHD-1X2")
      (footprint "eagle-import:1X02")
      (libsource (lib "eagle-import") (part "PINHD-1X2"))
    )
    (comp (ref "JP11")
      (value "PINHD-1X2")
      (footprint "eagle-import:1X02")
      (libsource (lib "eagle-import") (part "PINHD-1X2"))
    )
    (comp (ref "JP12")
      (value "PINHD-1X2")
      (footprint "eagle-import:1X02")
      (libsource (lib "eagle-import") (part "PINHD-1X2"))
    )
    (comp (ref "JP13")
      (value "PINHD-1X2")
      (footprint "eagle-import:1X02")
      (libsource (lib "eagle-import") (part "PINHD-1X2"))
    )
    (comp (ref "JP14")
      (value "PINHD-1X2")
      (footprint "eagle-import:1X02")
      (libsource (lib "eagle-import") (part "PINHD-1X2"))
    )
    (comp (ref "JP15")
      (value "PINHD-1X2")
      (footprint "eagle-import:1X02")
      (libsource (lib "eagle-import") (part "PINHD-1X2"))
    )
    (comp (ref "JP16")
      (value "PINHD-1X2")
      (footprint "eagle-import:1X02")
      (libsource (lib "eagle-import") (part "PINHD-1X2"))
    )
    (comp (ref "JP17")
      (value "PINHD-1X2")
      (footprint "eagle-import:1X02")
      (libsource (lib "eagle-import") (part "PINHD-1X2"))
    )
    (comp (ref "JP18")
      (value "PINHD-1X2")
      (footprint "eagle-import:1X02")
      (libsource (lib "eagle-import") (part "PINHD-1X2"))
    )
    (comp (ref "JP19")
      (value "PINHD-1X2")
      (footprint "eagle-import:1X02")
      (libsource (lib "eagle-import") (part "PINHD-1X2"))
    )
    (comp (ref "JP20")
      (value "PINHD-1X2")
      (footprint "eagle-import:1X02")
      (libsource (lib "eagle-import") (part "PINHD-1X2"))
    )
    (comp (ref "JP21")
      (value "PINHD-1X2")
      (footprint "eagle-import:1X02")
      (libsource (lib "eagle-import") (part "PINHD-1X2"))
    )
    (comp (ref "JP22")
      (value "PINHD-1X2")
      (footprint "eagle-import:1X02")
      (libsource (lib "eagle-import") (part "PINHD-1X2"))
    )
    (comp (ref "JP23")
      (value "PINHD-1X2")
      (footprint "eagle-import:1X02")
      (libsource (lib "eagle-import") (part "PINHD-1X2"))
    )
    (comp (ref "JP24")
      (value "PINHD-1X2")
      (footprint "eagle-import:1X02")
      (libsource (lib "eagle-import") (part "PINHD-1X2"))
    )
    (comp (ref "JP25")
      (value "PINHD-1X2")
      (footprint "eagle-import:1X02")
      (libsource (lib "eagle-import") (part "PINHD-1X2"))
    )
    (comp (ref "JP26")
      (value "PINHD-1X2")
      (footprint "eagle-import:1X02")
      (libsource (lib "eagle-import") (part "PINHD-1X2"))
    )
    (comp (ref "JP27")
      (value "PINHD-1X2")
      (footprint "eagle-import:1X02")
      (libsource (lib "eagle-import") (part "PINHD-1X2"))
    )
    (comp (ref "JP28")
      (value "PINHD-1X2")
      (footprint "eagle-import:1X02")
      (libsource (lib "eagle-import") (part "PINHD-1X2"))
    )
    (comp (ref "JP29")
      (value "PINHD-1X2")
      (footprint "eagle-import:1X02")
      (libsource (lib "eagle-import") (part "PINHD-1X2"))
    )
    (comp (ref "JP30")
      (value "PINHD-1X2")
      (footprint "eagle-import:1X02")
      (libsource (lib "eagle-import") (part "PINHD-1X2"))
    )
    (comp (ref "JP31")
      (value "PINHD-1X2")
      (footprint "eagle-import:1X02")
      (libsource (lib "eagle-import") (part "PINHD-1X2"))
    )
    (comp (ref "JP32")
      (value "PINHD-1X2")
      (footprint "eagle-import:1X02")
      (libsource (lib "eagle-import") (part "PINHD-1X2"))
    )
    (comp (ref "JP33")
      (value "PINHD-1X2")
      (footprint "eagle-import:1X02")
      (libsource (lib "eagle-import") (part "PINHD-1X2"))
    )
    (comp (ref "R1")
      (value "27K")
      (footprint "eagle-import:0207_2V")
      (libsource (lib "eagle-import") (part "R-US_0207/2V"))
    )
    (comp (ref "R3")
      (value "75K")
      (footprint "eagle-import:0207_2V")
      (libsource (lib "eagle-import") (part "R-US_0207/2V"))
    )
    (comp (ref "R6")
      (value "5K")
      (footprint "eagle-import:0207_2V")
      (libsource (lib "eagle-import") (part "R-US_0207/2V"))
    )
    (comp (ref "R7")
      (value "5K")
      (footprint "eagle-import:0207_2V")
      (libsource (lib "eagle-import") (part "R-US_0207/2V"))
    )
    (comp (ref "R15")
      (value "27K")
      (footprint "eagle-import:0207_2V")
      (libsource (lib "eagle-import") (part "R-US_0207/2V"))
    )
    (comp (ref "R16")
      (value "75K")
      (footprint "eagle-import:0207_2V")
      (libsource (lib "eagle-import") (part "R-US_0207/2V"))
    )
    (comp (ref "R17")
      (value "5K")
      (footprint "eagle-import:0207_2V")
      (libsource (lib "eagle-import") (part "R-US_0207/2V"))
    )
    (comp (ref "R18")
      (value "5K")
      (footprint "eagle-import:0207_2V")
      (libsource (lib "eagle-import") (part "R-US_0207/2V"))
    )
    (comp (ref "R19")
      (value "27K")
      (footprint "eagle-import:0207_2V")
      (libsource (lib "eagle-import") (part "R-US_0207/2V"))
    )
    (comp (ref "R20")
      (value "75K")
      (footprint "eagle-import:0207_2V")
      (libsource (lib "eagle-import") (part "R-US_0207/2V"))
    )
    (comp (ref "R21")
      (value "5K")
      (footprint "eagle-import:0207_2V")
      (libsource (lib "eagle-import") (part "R-US_0207/2V"))
    )
    (comp (ref "R22")
      (value "5K")
      (footprint "eagle-import:0207_2V")
      (libsource (lib "eagle-import") (part "R-US_0207/2V"))
    )
    (comp (ref "R23")
      (value "27K")
      (footprint "eagle-import:0207_2V")
      (libsource (lib "eagle-import") (part "R-US_0207/2V"))
    )
    (comp (ref "R24")
      (value "75K")
      (footprint "eagle-import:0207_2V")
      (libsource (lib "eagle-import") (part "R-US_0207/2V"))
    )
    (comp (ref "R25")
      (value "5K")
      (footprint "eagle-import:0207_2V")
      (libsource (lib "eagle-import") (part "R-US_0207/2V"))
    )
    (comp (ref "R26")
      (value "5K")
      (footprint "eagle-import:0207_2V")
      (libsource (lib "eagle-import") (part "R-US_0207/2V"))
    )
    (comp (ref "R27")
      (value "27K")
      (footprint "eagle-import:0207_2V")
      (libsource (lib "eagle-import") (part "R-US_0207/2V"))
    )
    (comp (ref "R28")
      (value "75K")
      (footprint "eagle-import:0207_2V")
      (libsource (lib "eagle-import") (part "R-US_0207/2V"))
    )
    (comp (ref "R29")
      (value "5K")
      (footprint "eagle-import:0207_2V")
      (libsource (lib "eagle-import") (part "R-US_0207/2V"))
    )
    (comp (ref "R30")
      (value "5K")
      (footprint "eagle-import:0207_2V")
      (libsource (lib "eagle-import") (part "R-US_0207/2V"))
    )
    (comp (ref "R31")
      (value "27K")
      (footprint "eagle-import:0207_2V")
      (libsource (lib "eagle-import") (part "R-US_0207/2V"))
    )
    (comp (ref "R32")
      (value "75K")
      (footprint "eagle-import:0207_2V")
      (libsource (lib "eagle-import") (part "R-US_0207/2V"))
    )
    (comp (ref "R33")
      (value "5K")
      (footprint "eagle-import:0207_2V")
      (libsource (lib "eagle-import") (part "R-US_0207/2V"))
    )
    (comp (ref "R34")
      (value "5K")
      (footprint "eagle-import:0207_2V")
      (libsource (lib "eagle-import") (part "R-US_0207/2V"))
    )
    (comp (ref "R35")
      (value "27K")
      (footprint "eagle-import:0207_2V")
      (libsource (lib "eagle-import") (part "R-US_0207/2V"))
    )
    (comp (ref "R36")
      (value "75K")
      (footprint "eagle-import:0207_2V")
      (libsource (lib "eagle-import") (part "R-US_0207/2V"))
    )
    (comp (ref "R37")
      (value "5K")
      (footprint "eagle-import:0207_2V")
      (libsource (lib "eagle-import") (part "R-US_0207/2V"))
    )
    (comp (ref "R38")
      (value "5K")
      (footprint "eagle-import:0207_2V")
      (libsource (lib "eagle-import") (part "R-US_0207/2V"))
    )
    (comp (ref "R39")
      (value "27K")
      (footprint "eagle-import:0207_2V")
      (libsource (lib "eagle-import") (part "R-US_0207/2V"))
    )
    (comp (ref "R40")
      (value "75K")
      (footprint "eagle-import:0207_2V")
      (libsource (lib "eagle-import") (part "R-US_0207/2V"))
    )
    (comp (ref "R41")
      (value "5K")
      (footprint "eagle-import:0207_2V")
      (libsource (lib "eagle-import") (part "R-US_0207/2V"))
    )
    (comp (ref "R42")
      (value "5K")
      (footprint "eagle-import:0207_2V")
      (libsource (lib "eagle-import") (part "R-US_0207/2V"))
    )
    (comp (ref "R43")
      (value "27K")
      (footprint "eagle-import:0207_2V")
      (libsource (lib "eagle-import") (part "R-US_0207/2V"))
    )
    (comp (ref "R44")
      (value "75K")
      (footprint "eagle-import:0207_2V")
      (libsource (lib "eagle-import") (part "R-US_0207/2V"))
    )
    (comp (ref "R45")
      (value "5K")
      (footprint "eagle-import:0207_2V")
      (libsource (lib "eagle-import") (part "R-US_0207/2V"))
    )
    (comp (ref "R46")
      (value "5K")
      (footprint "eagle-import:0207_2V")
      (libsource (lib "eagle-import") (part "R-US_0207/2V"))
    )
    (comp (ref "R47")
      (value "27K")
      (footprint "eagle-import:0207_2V")
      (libsource (lib "eagle-import") (part "R-US_0207/2V"))
    )
    (comp (ref "R48")
      (value "75K")
      (footprint "eagle-import:0207_2V")
      (libsource (lib "eagle-import") (part "R-US_0207/2V"))
    )
    (comp (ref "R49")
      (value "5K")
      (footprint "eagle-import:0207_2V")
      (libsource (lib "eagle-import") (part "R-US_0207/2V"))
    )
    (comp (ref "R50")
      (value "5K")
      (footprint "eagle-import:0207_2V")
      (libsource (lib "eagle-import") (part "R-US_0207/2V"))
    )
    (comp (ref "R51")
      (value "27K")
      (footprint "eagle-import:0207_2V")
      (libsource (lib "eagle-import") (part "R-US_0207/2V"))
    )
    (comp (ref "R52")
      (value "75K")
      (footprint "eagle-import:0207_2V")
      (libsource (lib "eagle-import") (part "R-US_0207/2V"))
    )
    (comp (ref "R53")
      (value "5K")
      (footprint "eagle-import:0207_2V")
      (libsource (lib "eagle-import") (part "R-US_0207/2V"))
    )
    (comp (ref "R54")
      (value "5K")
      (footprint "eagle-import:0207_2V")
      (libsource (lib "eagle-import") (part "R-US_0207/2V"))
    )
    (comp (ref "R55")
      (value "27K")
      (footprint "eagle-import:0207_2V")
      (libsource (lib "eagle-import") (part "R-US_0207/2V"))
    )
    (comp (ref "R56")
      (value "75K")
      (footprint "eagle-import:0207_2V")
      (libsource (lib "eagle-import") (part "R-US_0207/2V"))
    )
    (comp (ref "R57")
      (value "5K")
      (footprint "eagle-import:0207_2V")
      (libsource (lib "eagle-import") (part "R-US_0207/2V"))
    )
    (comp (ref "R58")
      (value "5K")
      (footprint "eagle-import:0207_2V")
      (libsource (lib "eagle-import") (part "R-US_0207/2V"))
    )
    (comp (ref "R59")
      (value "27K")
      (footprint "eagle-import:0207_2V")
      (libsource (lib "eagle-import") (part "R-US_0207/2V"))
    )
    (comp (ref "R60")
      (value "75K")
      (footprint "eagle-import:0207_2V")
      (libsource (lib "eagle-import") (part "R-US_0207/2V"))
    )
    (comp (ref "R61")
      (value "5K")
      (footprint "eagle-import:0207_2V")
      (libsource (lib "eagle-import") (part "R-US_0207/2V"))
    )
    (comp (ref "R62")
      (value "5K")
      (footprint "eagle-import:0207_2V")
      (libsource (lib "eagle-import") (part "R-US_0207/2V"))
    )
    (comp (ref "R63")
      (value "27K")
      (footprint "eagle-import:0207_2V")
      (libsource (lib "eagle-import") (part "R-US_0207/2V"))
    )
    (comp (ref "R64")
      (value "75K")
      (footprint "eagle-import:0207_2V")
      (libsource (lib "eagle-import") (part "R-US_0207/2V"))
    )
    (comp (ref "R65")
      (value "5K")
      (footprint "eagle-import:0207_2V")
      (libsource (lib "eagle-import") (part "R-US_0207/2V"))
    )
    (comp (ref "R66")
      (value "5K")
      (footprint "eagle-import:0207_2V")
      (libsource (lib "eagle-import") (part "R-US_0207/2V"))
    )
    (comp (ref "R67")
      (value "27K")
      (footprint "eagle-import:0207_2V")
      (libsource (lib "eagle-import") (part "R-US_0207/2V"))
    )
    (comp (ref "R68")
      (value "75K")
      (footprint "eagle-import:0207_2V")
      (libsource (lib "eagle-import") (part "R-US_0207/2V"))
    )
    (comp (ref "R69")
      (value "5K")
      (footprint "eagle-import:0207_2V")
      (libsource (lib "eagle-import") (part "R-US_0207/2V"))
    )
    (comp (ref "R70")
      (value "5K")
      (footprint "eagle-import:0207_2V")
      (libsource (lib "eagle-import") (part "R-US_0207/2V"))
    )
    (comp (ref "R71")
      (value "27K")
      (footprint "eagle-import:0207_2V")
      (libsource (lib "eagle-import") (part "R-US_0207/2V"))
    )
    (comp (ref "R72")
      (value "75K")
      (footprint "eagle-import:0207_2V")
      (libsource (lib "eagle-import") (part "R-US_0207/2V"))
    )
    (comp (ref "R73")
      (value "5K")
      (footprint "eagle-import:0207_2V")
      (libsource (lib "eagle-import") (part "R-US_0207/2V"))
    )
    (comp (ref "R74")
      (value "5K")
      (footprint "eagle-import:0207_2V")
      (libsource (lib "eagle-import") (part "R-US_0207/2V"))
    )
    (comp (ref "R75")
      (value "27K")
      (footprint "eagle-import:0207_2V")
      (libsource (lib "eagle-import") (part "R-US_0207/2V"))
    )
    (comp (ref "R76")
      (value "75K")
      (footprint "eagle-import:0207_2V")
      (libsource (lib "eagle-import") (part "R-US_0207/2V"))
    )
    (comp (ref "R77")
      (value "5K")
      (footprint "eagle-import:0207_2V")
      (libsource (lib "eagle-import") (part "R-US_0207/2V"))
    )
    (comp (ref "R78")
      (value "5K")
      (footprint "eagle-import:0207_2V")
      (libsource (lib "eagle-import") (part "R-US_0207/2V"))
    )
    (comp (ref "R79")
      (value "27K")
      (footprint "eagle-import:0207_2V")
      (libsource (lib "eagle-import") (part "R-US_0207/2V"))
    )
    (comp (ref "R80")
      (value "75K")
      (footprint "eagle-import:0207_2V")
      (libsource (lib "eagle-import") (part "R-US_0207/2V"))
    )
    (comp (ref "R81")
      (value "5K")
      (footprint "eagle-import:0207_2V")
      (libsource (lib "eagle-import") (part "R-US_0207/2V"))
    )
    (comp (ref "R82")
      (value "5K")
      (footprint "eagle-import:0207_2V")
      (libsource (lib "eagle-import") (part "R-US_0207/2V"))
    )
    (comp (ref "R83")
      (value "27K")
      (footprint "eagle-import:0207_2V")
      (libsource (lib "eagle-import") (part "R-US_0207/2V"))
    )
    (comp (ref "R84")
      (value "75K")
      (footprint "eagle-import:0207_2V")
      (libsource (lib "eagle-import") (part "R-US_0207/2V"))
    )
    (comp (ref "R85")
      (value "5K")
      (footprint "eagle-import:0207_2V")
      (libsource (lib "eagle-import") (part "R-US_0207/2V"))
    )
    (comp (ref "R86")
      (value "5K")
      (footprint "eagle-import:0207_2V")
      (libsource (lib "eagle-import") (part "R-US_0207/2V"))
    )
    (comp (ref "R87")
      (value "27K")
      (footprint "eagle-import:0207_2V")
      (libsource (lib "eagle-import") (part "R-US_0207/2V"))
    )
    (comp (ref "R88")
      (value "75K")
      (footprint "eagle-import:0207_2V")
      (libsource (lib "eagle-import") (part "R-US_0207/2V"))
    )
    (comp (ref "R89")
      (value "5K")
      (footprint "eagle-import:0207_2V")
      (libsource (lib "eagle-import") (part "R-US_0207/2V"))
    )
    (comp (ref "R90")
      (value "5K")
      (footprint "eagle-import:0207_2V")
      (libsource (lib "eagle-import") (part "R-US_0207/2V"))
    )
    (comp (ref "R91")
      (value "27K")
      (footprint "eagle-import:0207_2V")
      (libsource (lib "eagle-import") (part "R-US_0207/2V"))
    )
    (comp (ref "R92")
      (value "75K")
      (footprint "eagle-import:0207_2V")
      (libsource (lib "eagle-import") (part "R-US_0207/2V"))
    )
    (comp (ref "R93")
      (value "5K")
      (footprint "eagle-import:0207_2V")
      (libsource (lib "eagle-import") (part "R-US_0207/2V"))
    )
    (comp (ref "R94")
      (value "5K")
      (footprint "eagle-import:0207_2V")
      (libsource (lib "eagle-import") (part "R-US_0207/2V"))
    )
    (comp (ref "R95")
      (value "27K")
      (footprint "eagle-import:0207_2V")
      (libsource (lib "eagle-import") (part "R-US_0207/2V"))
    )
    (comp (ref "R96")
      (value "75K")
      (footprint "eagle-import:0207_2V")
      (libsource (lib "eagle-import") (part "R-US_0207/2V"))
    )
    (comp (ref "R97")
      (value "5K")
      (footprint "eagle-import:0207_2V")
      (libsource (lib "eagle-import") (part "R-US_0207/2V"))
    )
    (comp (ref "R98")
      (value "5K")
      (footprint "eagle-import:0207_2V")
      (libsource (lib "eagle-import") (part "R-US_0207/2V"))
    )
    (comp (ref "R99")
      (value "27K")
      (footprint "eagle-import:0207_2V")
      (libsource (lib "eagle-import") (part "R-US_0207/2V"))
    )
    (comp (ref "R100")
      (value "75K")
      (footprint "eagle-import:0207_2V")
      (libsource (lib "eagle-import") (part "R-US_0207/2V"))
    )
    (comp (ref "R101")
      (value "5K")
      (footprint "eagle-import:0207_2V")
      (libsource (lib "eagle-import") (part "R-US_0207/2V"))
    )
    (comp (ref "R102")
      (value "5K")
      (footprint "eagle-import:0207_2V")
      (libsource (lib "eagle-import") (part "R-US_0207/2V"))
    )
    (comp (ref "R103")
      (value "27K")
      (footprint "eagle-import:0207_2V")
      (libsource (lib "eagle-import") (part "R-US_0207/2V"))
    )
    (comp (ref "R104")
      (value "75K")
      (footprint "eagle-import:0207_2V")
      (libsource (lib "eagle-import") (part "R-US_0207/2V"))
    )
    (comp (ref "R105")
      (value "5K")
      (footprint "eagle-import:0207_2V")
      (libsource (lib "eagle-import") (part "R-US_0207/2V"))
    )
    (comp (ref "R106")
      (value "5K")
      (footprint "eagle-import:0207_2V")
      (libsource (lib "eagle-import") (part "R-US_0207/2V"))
    )
    (comp (ref "R107")
      (value "27K")
      (footprint "eagle-import:0207_2V")
      (libsource (lib "eagle-import") (part "R-US_0207/2V"))
    )
    (comp (ref "R108")
      (value "75K")
      (footprint "eagle-import:0207_2V")
      (libsource (lib "eagle-import") (part "R-US_0207/2V"))
    )
    (comp (ref "R109")
      (value "5K")
      (footprint "eagle-import:0207_2V")
      (libsource (lib "eagle-import") (part "R-US_0207/2V"))
    )
    (comp (ref "R110")
      (value "5K")
      (footprint "eagle-import:0207_2V")
      (libsource (lib "eagle-import") (part "R-US_0207/2V"))
    )
    (comp (ref "R111")
      (value "27K")
      (footprint "eagle-import:0207_2V")
      (libsource (lib "eagle-import") (part "R-US_0207/2V"))
    )
    (comp (ref "R112")
      (value "75K")
      (footprint "eagle-import:0207_2V")
      (libsource (lib "eagle-import") (part "R-US_0207/2V"))
    )
    (comp (ref "R113")
      (value "5K")
      (footprint "eagle-import:0207_2V")
      (libsource (lib "eagle-import") (part "R-US_0207/2V"))
    )
    (comp (ref "R114")
      (value "5K")
      (footprint "eagle-import:0207_2V")
      (libsource (lib "eagle-import") (part "R-US_0207/2V"))
    )
    (comp (ref "R115")
      (value "27K")
      (footprint "eagle-import:0207_2V")
      (libsource (lib "eagle-import") (part "R-US_0207/2V"))
    )
    (comp (ref "R116")
      (value "75K")
      (footprint "eagle-import:0207_2V")
      (libsource (lib "eagle-import") (part "R-US_0207/2V"))
    )
    (comp (ref "R117")
      (value "5K")
      (footprint "eagle-import:0207_2V")
      (libsource (lib "eagle-import") (part "R-US_0207/2V"))
    )
    (comp (ref "R118")
      (value "5K")
      (footprint "eagle-import:0207_2V")
      (libsource (lib "eagle-import") (part "R-US_0207/2V"))
    )
    (comp (ref "R119")
      (value "27K")
      (footprint "eagle-import:0207_2V")
      (libsource (lib "eagle-import") (part "R-US_0207/2V"))
    )
    (comp (ref "R120")
      (value "75K")
      (footprint "eagle-import:0207_2V")
      (libsource (lib "eagle-import") (part "R-US_0207/2V"))
    )
    (comp (ref "R121")
      (value "5K")
      (footprint "eagle-import:0207_2V")
      (libsource (lib "eagle-import") (part "R-US_0207/2V"))
    )
    (comp (ref "R122")
      (value "5K")
      (footprint "eagle-import:0207_2V")
      (libsource (lib "eagle-import") (part "R-US_0207/2V"))
    )
    (comp (ref "R123")
      (value "27K")
      (footprint "eagle-import:0207_2V")
      (libsource (lib "eagle-import") (part "R-US_0207/2V"))
    )
    (comp (ref "R124")
      (value "75K")
      (footprint "eagle-import:0207_2V")
      (libsource (lib "eagle-import") (part "R-US_0207/2V"))
    )
    (comp (ref "R125")
      (value "5K")
      (footprint "eagle-import:0207_2V")
      (libsource (lib "eagle-import") (part "R-US_0207/2V"))
    )
    (comp (ref "R126")
      (value "5K")
      (footprint "eagle-import:0207_2V")
      (libsource (lib "eagle-import") (part "R-US_0207/2V"))
    )
    (comp (ref "R127")
      (value "27K")
      (footprint "eagle-import:0207_2V")
      (libsource (lib "eagle-import") (part "R-US_0207/2V"))
    )
    (comp (ref "R128")
      (value "75K")
      (footprint "eagle-import:0207_2V")
      (libsource (lib "eagle-import") (part "R-US_0207/2V"))
    )
    (comp (ref "R129")
      (value "5K")
      (footprint "eagle-import:0207_2V")
      (libsource (lib "eagle-import") (part "R-US_0207/2V"))
    )
    (comp (ref "R130")
      (value "5K")
      (footprint "eagle-import:0207_2V")
      (libsource (lib "eagle-import") (part "R-US_0207/2V"))
    )
    (comp (ref "R131")
      (value "27K")
      (footprint "eagle-import:0207_2V")
      (libsource (lib "eagle-import") (part "R-US_0207/2V"))
    )
    (comp (ref "R132")
      (value "75K")
      (footprint "eagle-import:0207_2V")
      (libsource (lib "eagle-import") (part "R-US_0207/2V"))
    )
    (comp (ref "R133")
      (value "5K")
      (footprint "eagle-import:0207_2V")
      (libsource (lib "eagle-import") (part "R-US_0207/2V"))
    )
    (comp (ref "R134")
      (value "5K")
      (footprint "eagle-import:0207_2V")
      (libsource (lib "eagle-import") (part "R-US_0207/2V"))
    )
    (comp (ref "R135")
      (value "27K")
      (footprint "eagle-import:0207_2V")
      (libsource (lib "eagle-import") (part "R-US_0207/2V"))
    )
    (comp (ref "R136")
      (value "75K")
      (footprint "eagle-import:0207_2V")
      (libsource (lib "eagle-import") (part "R-US_0207/2V"))
    )
    (comp (ref "R137")
      (value "5K")
      (footprint "eagle-import:0207_2V")
      (libsource (lib "eagle-import") (part "R-US_0207/2V"))
    )
    (comp (ref "R138")
      (value "5K")
      (footprint "eagle-import:0207_2V")
      (libsource (lib "eagle-import") (part "R-US_0207/2V"))
    )
    (comp (ref "SV7")
      (value "MA08-2")
      (footprint "eagle-import:MA08-2")
      (libsource (lib "eagle-import") (part "MA08-2"))
    )
    (comp (ref "SV8")
      (value "MA08-2")
      (footprint "eagle-import:MA08-2")
      (libsource (lib "eagle-import") (part "MA08-2"))
    )
  )
  (nets
    (net (code "1") (name "+5V") (class "Default")
      (node (ref "5V") (pin "1") (pinfunction "1_1") (pintype "passive"))
      (node (ref "IC9") (pin "OUT") (pinfunction "OUT_OUT") (pintype "passive"))
      (node (ref "R10") (pin "1") (pinfunction "1_1") (pintype "passive"))
      (node (ref "R259") (pin "1") (pinfunction "1_1") (pintype "passive"))
      (node (ref "R261") (pin "1") (pinfunction "1_1") (pintype "passive"))
      (node (ref "R263") (pin "1") (pinfunction "1_1") (pintype "passive"))
      (node (ref "R265") (pin "1") (pinfunction "1_1") (pintype "passive"))
      (node (ref "R267") (pin "1") (pinfunction "1_1") (pintype "passive"))
      (node (ref "R269") (pin "1") (pinfunction "1_1") (pintype "passive"))
      (node (ref "R271") (pin "1") (pinfunction "1_1") (pintype "passive"))
      (node (ref "R273") (pin "1") (pinfunction "1_1") (pintype "passive"))
      (node (ref "R275") (pin "1") (pinfunction "1_1") (pintype "passive"))
      (node (ref "R277") (pin "1") (pinfunction "1_1") (pintype "passive"))
      (node (ref "R279") (pin "1") (pinfunction "1_1") (pintype "passive"))
      (node (ref "R281") (pin "1") (pinfunction "1_1") (pintype "passive"))
      (node (ref "R283") (pin "1") (pinfunction "1_1") (pintype "passive"))
      (node (ref "R285") (pin "1") (pinfunction "1_1") (pintype "passive"))
      (node (ref "R287") (pin "1") (pinfunction "1_1") (pintype "passive"))
      (node (ref "R289") (pin "1") (pinfunction "1_1") (pintype "passive"))
      (node (ref "R291") (pin "1") (pinfunction "1_1") (pintype "passive"))
      (node (ref "R293") (pin "1") (pinfunction "1_1") (pintype "passive"))
      (node (ref "R295") (pin "1") (pinfunction "1_1") (pintype "passive"))
      (node (ref "R297") (pin "1") (pinfunction "1_1") (pintype "passive"))
      (node (ref "R299") (pin "1") (pinfunction "1_1") (pintype "passive"))
      (node (ref "R301") (pin "1") (pinfunction "1_1") (pintype "passive"))
      (node (ref "R303") (pin "1") (pinfunction "1_1") (pintype "passive"))
      (node (ref "R305") (pin "1") (pinfunction "1_1") (pintype "passive"))
      (node (ref "R307") (pin "1") (pinfunction "1_1") (pintype "passive"))
      (node (ref "R309") (pin "1") (pinfunction "1_1") (pintype "passive"))
      (node (ref "R311") (pin "1") (pinfunction "1_1") (pintype "passive"))
      (node (ref "R313") (pin "1") (pinfunction "1_1") (pintype "passive"))
      (node (ref "R315") (pin "1") (pinfunction "1_1") (pintype "passive"))
      (node (ref "R317") (pin "1") (pinfunction "1_1") (pintype "passive"))
      (node (ref "R319") (pin "1") (pinfunction "1_1") (pintype "passive"))
    )
    (net (code "2") (name "-5V") (class "Default")
      (node (ref "IC10") (pin "OUT") (pinfunction "OUT_OUT") (pintype "passive"))
      (node (ref "R13") (pin "1") (pinfunction "1_1") (pintype "passive"))
      (node (ref "R139") (pin "2") (pinfunction "2_2") (pintype "passive"))
      (node (ref "R141") (pin "1") (pinfunction "1_1") (pintype "passive"))
      (node (ref "R143") (pin "2") (pinfunction "2_2") (pintype "passive"))
      (node (ref "R145") (pin "1") (pinfunction "1_1") (pintype "passive"))
      (node (ref "R147") (pin "2") (pinfunction "2_2") (pintype "passive"))
      (node (ref "R149") (pin "1") (pinfunction "1_1") (pintype "passive"))
      (node (ref "R151") (pin "2") (pinfunction "2_2") (pintype "passive"))
      (node (ref "R153") (pin "1") (pinfunction "1_1") (pintype "passive"))
      (node (ref "R155") (pin "2") (pinfunction "2_2") (pintype "passive"))
      (node (ref "R157") (pin "1") (pinfunction "1_1") (pintype "passive"))
      (node (ref "R159") (pin "2") (pinfunction "2_2") (pintype "passive"))
      (node (ref "R161") (pin "1") (pinfunction "1_1") (pintype "passive"))
      (node (ref "R163") (pin "2") (pinfunction "2_2") (pintype "passive"))
      (node (ref "R165") (pin "1") (pinfunction "1_1") (pintype "passive"))
      (node (ref "R167") (pin "2") (pinfunction "2_2") (pintype "passive"))
      (node (ref "R169") (pin "1") (pinfunction "1_1") (pintype "passive"))
      (node (ref "R171") (pin "2") (pinfunction "2_2") (pintype "passive"))
      (node (ref "R173") (pin "1") (pinfunction "1_1") (pintype "passive"))
      (node (ref "R175") (pin "2") (pinfunction "2_2") (pintype "passive"))
      (node (ref "R177") (pin "1") (pinfunction "1_1") (pintype "passive"))
      (node (ref "R179") (pin "2") (pinfunction "2_2") (pintype "passive"))
      (node (ref "R181") (pin "1") (pinfunction "1_1") (pintype "passive"))
      (node (ref "R183") (pin "2") (pinfunction "2_2") (pintype "passive"))
      (node (ref "R185") (pin "1") (pinfunction "1_1") (pintype "passive"))
      (node (ref "R187") (pin "2") (pinfunction "2_2") (pintype "passive"))
      (node (ref "R189") (pin "1") (pinfunction "1_1") (pintype "passive"))
      (node (ref "R191") (pin "2") (pinfunction "2_2") (pintype "passive"))
      (node (ref "R193") (pin "1") (pinfunction "1_1") (pintype "passive"))
      (node (ref "R195") (pin "2") (pinfunction "2_2") (pintype "passive"))
      (node (ref "R197") (pin "1") (pinfunction "1_1") (pintype "passive"))
      (node (ref "R199") (pin "2") (pinfunction "2_2") (pintype "passive"))
      (node (ref "R2") (pin "2") (pinfunction "2_2") (pintype "passive"))
      (node (ref "R201") (pin "1") (pinfunction "1_1") (pintype "passive"))
      (node (ref "R203") (pin "2") (pinfunction "2_2") (pintype "passive"))
      (node (ref "R205") (pin "1") (pinfunction "1_1") (pintype "passive"))
      (node (ref "R207") (pin "2") (pinfunction "2_2") (pintype "passive"))
      (node (ref "R209") (pin "1") (pinfunction "1_1") (pintype "passive"))
      (node (ref "R211") (pin "2") (pinfunction "2_2") (pintype "passive"))
      (node (ref "R213") (pin "1") (pinfunction "1_1") (pintype "passive"))
      (node (ref "R215") (pin "2") (pinfunction "2_2") (pintype "passive"))
      (node (ref "R217") (pin "1") (pinfunction "1_1") (pintype "passive"))
      (node (ref "R219") (pin "2") (pinfunction "2_2") (pintype "passive"))
      (node (ref "R221") (pin "1") (pinfunction "1_1") (pintype "passive"))
      (node (ref "R223") (pin "2") (pinfunction "2_2") (pintype "passive"))
      (node (ref "R225") (pin "1") (pinfunction "1_1") (pintype "passive"))
      (node (ref "R227") (pin "2") (pinfunction "2_2") (pintype "passive"))
      (node (ref "R229") (pin "1") (pinfunction "1_1") (pintype "passive"))
      (node (ref "R231") (pin "2") (pinfunction "2_2") (pintype "passive"))
      (node (ref "R233") (pin "1") (pinfunction "1_1") (pintype "passive"))
      (node (ref "R235") (pin "2") (pinfunction "2_2") (pintype "passive"))
      (node (ref "R237") (pin "1") (pinfunction "1_1") (pintype "passive"))
      (node (ref "R239") (pin "2") (pinfunction "2_2") (pintype "passive"))
      (node (ref "R241") (pin "1") (pinfunction "1_1") (pintype "passive"))
      (node (ref "R243") (pin "2") (pinfunction "2_2") (pintype "passive"))
      (node (ref "R245") (pin "1") (pinfunction "1_1") (pintype "passive"))
      (node (ref "R247") (pin "2") (pinfunction "2_2") (pintype "passive"))
      (node (ref "R249") (pin "1") (pinfunction "1_1") (pintype "passive"))
      (node (ref "R251") (pin "2") (pinfunction "2_2") (pintype "passive"))
      (node (ref "R253") (pin "1") (pinfunction "1_1") (pintype "passive"))
      (node (ref "R255") (pin "2") (pinfunction "2_2") (pintype "passive"))
      (node (ref "R257") (pin "1") (pinfunction "1_1") (pintype "passive"))
      (node (ref "R4") (pin "2") (pinfunction "2_2") (pintype "passive"))
      (node (ref "R8") (pin "1") (pinfunction "1_1") (pintype "passive"))
    )
    (net (code "3") (name "A1") (class "Default")
      (node (ref "Q1") (pin "D") (pinfunction "D_D") (pintype "passive"))
      (node (ref "Q2") (pin "D") (pinfunction "D_D") (pintype "passive"))
      (node (ref "Q4") (pin "D") (pinfunction "D_D") (pintype "passive"))
      (node (ref "R3") (pin "1") (pinfunction "1_1") (pintype "passive"))
      (node (ref "SIDE1") (pin "10") (pinfunction "10_10") (pintype "passive"))
    )
    (net (code "4") (name "A2") (class "Default")
      (node (ref "A2") (pin "1") (pinfunction "1_1") (pintype "passive"))
      (node (ref "SIDE2") (pin "2") (pinfunction "2_2") (pintype "passive"))
    )
    (net (code "5") (name "B1") (class "Default")
      (node (ref "Q35") (pin "D") (pinfunction "D_D") (pintype "passive"))
      (node (ref "Q36") (pin "D") (pinfunction "D_D") (pintype "passive"))
      (node (ref "Q5") (pin "D") (pinfunction "D_D") (pintype "passive"))
      (node (ref "R16") (pin "1") (pinfunction "1_1") (pintype "passive"))
      (node (ref "SIDE1") (pin "6") (pinfunction "6_6") (pintype "passive"))
    )
    (net (code "6") (name "B2") (class "Default")
      (node (ref "B2") (pin "1") (pinfunction "1_1") (pintype "passive"))
      (node (ref "SIDE2") (pin "4") (pinfunction "4_4") (pintype "passive"))
    )
    (net (code "7") (name "C1") (class "Default")
      (node (ref "Q37") (pin "D") (pinfunction "D_D") (pintype "passive"))
      (node (ref "Q38") (pin "D") (pinfunction "D_D") (pintype "passive"))
      (node (ref "Q6") (pin "D") (pinfunction "D_D") (pintype "passive"))
      (node (ref "R20") (pin "1") (pinfunction "1_1") (pintype "passive"))
      (node (ref "SIDE1") (pin "1") (pinfunction "1_1") (pintype "passive"))
      (node (ref "SIDE1") (pin "11") (pinfunction "11_11") (pintype "passive"))
      (node (ref "SIDE1") (pin "13") (pinfunction "13_13") (pintype "passive"))
      (node (ref "SIDE1") (pin "15") (pinfunction "15_15") (pintype "passive"))
      (node (ref "SIDE1") (pin "17") (pinfunction "17_17") (pintype "passive"))
      (node (ref "SIDE1") (pin "19") (pinfunction "19_19") (pintype "passive"))
      (node (ref "SIDE1") (pin "21") (pinfunction "21_21") (pintype "passive"))
      (node (ref "SIDE1") (pin "23") (pinfunction "23_23") (pintype "passive"))
      (node (ref "SIDE1") (pin "25") (pinfunction "25_25") (pintype "passive"))
      (node (ref "SIDE1") (pin "27") (pinfunction "27_27") (pintype "passive"))
      (node (ref "SIDE1") (pin "29") (pinfunction "29_29") (pintype "passive"))
      (node (ref "SIDE1") (pin "3") (pinfunction "3_3") (pintype "passive"))
      (node (ref "SIDE1") (pin "31") (pinfunction "31_31") (pintype "passive"))
      (node (ref "SIDE1") (pin "33") (pinfunction "33_33") (pintype "passive"))
      (node (ref "SIDE1") (pin "5") (pinfunction "5_5") (pintype "passive"))
      (node (ref "SIDE1") (pin "7") (pinfunction "7_7") (pintype "passive"))
      (node (ref "SIDE1") (pin "9") (pinfunction "9_9") (pintype "passive"))
    )
    (net (code "8") (name "C2") (class "Default")
      (node (ref "C2") (pin "1") (pinfunction "1_1") (pintype "passive"))
      (node (ref "SIDE2") (pin "1") (pinfunction "1_1") (pintype "passive"))
      (node (ref "SIDE2") (pin "11") (pinfunction "11_11") (pintype "passive"))
      (node (ref "SIDE2") (pin "13") (pinfunction "13_13") (pintype "passive"))
      (node (ref "SIDE2") (pin "15") (pinfunction "15_15") (pintype "passive"))
      (node (ref "SIDE2") (pin "17") (pinfunction "17_17") (pintype "passive"))
      (node (ref "SIDE2") (pin "19") (pinfunction "19_19") (pintype "passive"))
      (node (ref "SIDE2") (pin "21") (pinfunction "21_21") (pintype "passive"))
      (node (ref "SIDE2") (pin "23") (pinfunction "23_23") (pintype "passive"))
      (node (ref "SIDE2") (pin "25") (pinfunction "25_25") (pintype "passive"))
      (node (ref "SIDE2") (pin "27") (pinfunction "27_27") (pintype "passive"))
      (node (ref "SIDE2") (pin "29") (pinfunction "29_29") (pintype "passive"))
      (node (ref "SIDE2") (pin "3") (pinfunction "3_3") (pintype "passive"))
      (node (ref "SIDE2") (pin "31") (pinfunction "31_31") (pintype "passive"))
      (node (ref "SIDE2") (pin "33") (pinfunction "33_33") (pintype "passive"))
      (node (ref "SIDE2") (pin "5") (pinfunction "5_5") (pintype "passive"))
      (node (ref "SIDE2") (pin "7") (pinfunction "7_7") (pintype "passive"))
      (node (ref "SIDE2") (pin "9") (pinfunction "9_9") (pintype "passive"))
    )
    (net (code "9") (name "D1") (class "Default")
      (node (ref "Q39") (pin "D") (pinfunction "D_D") (pintype "passive"))
      (node (ref "Q40") (pin "D") (pinfunction "D_D") (pintype "passive"))
      (node (ref "Q7") (pin "D") (pinfunction "D_D") (pintype "passive"))
      (node (ref "R24") (pin "1") (pinfunction "1_1") (pintype "passive"))
      (node (ref "SIDE1") (pin "8") (pinfunction "8_8") (pintype "passive"))
    )
    (net (code "10") (name "D2") (class "Default")
      (node (ref "Q20") (pin "D") (pinfunction "D_D") (pintype "passive"))
      (node (ref "Q67") (pin "D") (pinfunction "D_D") (pintype "passive"))
      (node (ref "Q68") (pin "D") (pinfunction "D_D") (pintype "passive"))
      (node (ref "R80") (pin "1") (pinfunction "1_1") (pintype "passive"))
      (node (ref "SIDE2") (pin "6") (pinfunction "6_6") (pintype "passive"))
    )
    (net (code "11") (name "E1") (class "Default")
      (node (ref "Q3") (pin "D") (pinfunction "D_D") (pintype "passive"))
      (node (ref "Q41") (pin "D") (pinfunction "D_D") (pintype "passive"))
      (node (ref "Q42") (pin "D") (pinfunction "D_D") (pintype "passive"))
      (node (ref "R28") (pin "1") (pinfunction "1_1") (pintype "passive"))
      (node (ref "SIDE1") (pin "12") (pinfunction "12_12") (pintype "passive"))
    )
    (net (code "12") (name "E2") (class "Default")
      (node (ref "Q21") (pin "D") (pinfunction "D_D") (pintype "passive"))
      (node (ref "Q69") (pin "D") (pinfunction "D_D") (pintype "passive"))
      (node (ref "Q70") (pin "D") (pinfunction "D_D") (pintype "passive"))
      (node (ref "R84") (pin "1") (pinfunction "1_1") (pintype "passive"))
      (node (ref "SIDE2") (pin "8") (pinfunction "8_8") (pintype "passive"))
    )
    (net (code "13") (name "F1") (class "Default")
      (node (ref "Q43") (pin "D") (pinfunction "D_D") (pintype "passive"))
      (node (ref "Q44") (pin "D") (pinfunction "D_D") (pintype "passive"))
      (node (ref "Q8") (pin "D") (pinfunction "D_D") (pintype "passive"))
      (node (ref "R32") (pin "1") (pinfunction "1_1") (pintype "passive"))
      (node (ref "SIDE1") (pin "14") (pinfunction "14_14") (pintype "passive"))
    )
    (net (code "14") (name "F2") (class "Default")
      (node (ref "Q22") (pin "D") (pinfunction "D_D") (pintype "passive"))
      (node (ref "Q71") (pin "D") (pinfunction "D_D") (pintype "passive"))
      (node (ref "Q72") (pin "D") (pinfunction "D_D") (pintype "passive"))
      (node (ref "R88") (pin "1") (pinfunction "1_1") (pintype "passive"))
      (node (ref "SIDE2") (pin "10") (pinfunction "10_10") (pintype "passive"))
    )
    (net (code "15") (name "GND") (class "Default")
      (node (ref "C2") (pin "2") (pinfunction "2_2") (pintype "passive"))
      (node (ref "D1") (pin "A") (pinfunction "A_A") (pintype "passive"))
      (node (ref "D10") (pin "A") (pinfunction "A_A") (pintype "passive"))
      (node (ref "D100") (pin "A") (pinfunction "A_A") (pintype "passive"))
      (node (ref "D101") (pin "A") (pinfunction "A_A") (pintype "passive"))
      (node (ref "D102") (pin "A") (pinfunction "A_A") (pintype "passive"))
      (node (ref "D103") (pin "A") (pinfunction "A_A") (pintype "passive"))
      (node (ref "D104") (pin "A") (pinfunction "A_A") (pintype "passive"))
      (node (ref "D105") (pin "A") (pinfunction "A_A") (pintype "passive"))
      (node (ref "D106") (pin "A") (pinfunction "A_A") (pintype "passive"))
      (node (ref "D107") (pin "A") (pinfunction "A_A") (pintype "passive"))
      (node (ref "D108") (pin "A") (pinfunction "A_A") (pintype "passive"))
      (node (ref "D109") (pin "A") (pinfunction "A_A") (pintype "passive"))
      (node (ref "D11") (pin "A") (pinfunction "A_A") (pintype "passive"))
      (node (ref "D110") (pin "A") (pinfunction "A_A") (pintype "passive"))
      (node (ref "D111") (pin "A") (pinfunction "A_A") (pintype "passive"))
      (node (ref "D112") (pin "A") (pinfunction "A_A") (pintype "passive"))
      (node (ref "D113") (pin "A") (pinfunction "A_A") (pintype "passive"))
      (node (ref "D114") (pin "A") (pinfunction "A_A") (pintype "passive"))
      (node (ref "D115") (pin "A") (pinfunction "A_A") (pintype "passive"))
      (node (ref "D116") (pin "A") (pinfunction "A_A") (pintype "passive"))
      (node (ref "D117") (pin "A") (pinfunction "A_A") (pintype "passive"))
      (node (ref "D118") (pin "A") (pinfunction "A_A") (pintype "passive"))
      (node (ref "D119") (pin "A") (pinfunction "A_A") (pintype "passive"))
      (node (ref "D12") (pin "A") (pinfunction "A_A") (pintype "passive"))
      (node (ref "D120") (pin "A") (pinfunction "A_A") (pintype "passive"))
      (node (ref "D121") (pin "A") (pinfunction "A_A") (pintype "passive"))
      (node (ref "D122") (pin "A") (pinfunction "A_A") (pintype "passive"))
      (node (ref "D123") (pin "A") (pinfunction "A_A") (pintype "passive"))
      (node (ref "D124") (pin "A") (pinfunction "A_A") (pintype "passive"))
      (node (ref "D125") (pin "A") (pinfunction "A_A") (pintype "passive"))
      (node (ref "D126") (pin "A") (pinfunction "A_A") (pintype "passive"))
      (node (ref "D127") (pin "A") (pinfunction "A_A") (pintype "passive"))
      (node (ref "D128") (pin "A") (pinfunction "A_A") (pintype "passive"))
      (node (ref "D13") (pin "A") (pinfunction "A_A") (pintype "passive"))
      (node (ref "D14") (pin "A") (pinfunction "A_A") (pintype "passive"))
      (node (ref "D15") (pin "A") (pinfunction "A_A") (pintype "passive"))
      (node (ref "D16") (pin "A") (pinfunction "A_A") (pintype "passive"))
      (node (ref "D17") (pin "A") (pinfunction "A_A") (pintype "passive"))
      (node (ref "D18") (pin "A") (pinfunction "A_A") (pintype "passive"))
      (node (ref "D19") (pin "A") (pinfunction "A_A") (pintype "passive"))
      (node (ref "D2") (pin "A") (pinfunction "A_A") (pintype "passive"))
      (node (ref "D20") (pin "A") (pinfunction "A_A") (pintype "passive"))
      (node (ref "D21") (pin "A") (pinfunction "A_A") (pintype "passive"))
      (node (ref "D22") (pin "A") (pinfunction "A_A") (pintype "passive"))
      (node (ref "D23") (pin "A") (pinfunction "A_A") (pintype "passive"))
      (node (ref "D24") (pin "A") (pinfunction "A_A") (pintype "passive"))
      (node (ref "D25") (pin "A") (pinfunction "A_A") (pintype "passive"))
      (node (ref "D26") (pin "A") (pinfunction "A_A") (pintype "passive"))
      (node (ref "D27") (pin "A") (pinfunction "A_A") (pintype "passive"))
      (node (ref "D28") (pin "A") (pinfunction "A_A") (pintype "passive"))
      (node (ref "D29") (pin "A") (pinfunction "A_A") (pintype "passive"))
      (node (ref "D3") (pin "A") (pinfunction "A_A") (pintype "passive"))
      (node (ref "D30") (pin "A") (pinfunction "A_A") (pintype "passive"))
      (node (ref "D31") (pin "A") (pinfunction "A_A") (pintype "passive"))
      (node (ref "D32") (pin "A") (pinfunction "A_A") (pintype "passive"))
      (node (ref "D33") (pin "A") (pinfunction "A_A") (pintype "passive"))
      (node (ref "D34") (pin "A") (pinfunction "A_A") (pintype "passive"))
      (node (ref "D35") (pin "A") (pinfunction "A_A") (pintype "passive"))
      (node (ref "D36") (pin "A") (pinfunction "A_A") (pintype "passive"))
      (node (ref "D37") (pin "A") (pinfunction "A_A") (pintype "passive"))
      (node (ref "D38") (pin "A") (pinfunction "A_A") (pintype "passive"))
      (node (ref "D39") (pin "A") (pinfunction "A_A") (pintype "passive"))
      (node (ref "D4") (pin "A") (pinfunction "A_A") (pintype "passive"))
      (node (ref "D40") (pin "A") (pinfunction "A_A") (pintype "passive"))
      (node (ref "D41") (pin "A") (pinfunction "A_A") (pintype "passive"))
      (node (ref "D42") (pin "A") (pinfunction "A_A") (pintype "passive"))
      (node (ref "D43") (pin "A") (pinfunction "A_A") (pintype "passive"))
      (node (ref "D44") (pin "A") (pinfunction "A_A") (pintype "passive"))
      (node (ref "D45") (pin "A") (pinfunction "A_A") (pintype "passive"))
      (node (ref "D46") (pin "A") (pinfunction "A_A") (pintype "passive"))
      (node (ref "D47") (pin "A") (pinfunction "A_A") (pintype "passive"))
      (node (ref "D48") (pin "A") (pinfunction "A_A") (pintype "passive"))
      (node (ref "D49") (pin "A") (pinfunction "A_A") (pintype "passive"))
      (node (ref "D5") (pin "A") (pinfunction "A_A") (pintype "passive"))
      (node (ref "D50") (pin "A") (pinfunction "A_A") (pintype "passive"))
      (node (ref "D51") (pin "A") (pinfunction "A_A") (pintype "passive"))
      (node (ref "D52") (pin "A") (pinfunction "A_A") (pintype "passive"))
      (node (ref "D53") (pin "A") (pinfunction "A_A") (pintype "passive"))
      (node (ref "D54") (pin "A") (pinfunction "A_A") (pintype "passive"))
      (node (ref "D55") (pin "A") (pinfunction "A_A") (pintype "passive"))
      (node (ref "D56") (pin "A") (pinfunction "A_A") (pintype "passive"))
      (node (ref "D57") (pin "A") (pinfunction "A_A") (pintype "passive"))
      (node (ref "D58") (pin "A") (pinfunction "A_A") (pintype "passive"))
      (node (ref "D59") (pin "A") (pinfunction "A_A") (pintype "passive"))
      (node (ref "D6") (pin "A") (pinfunction "A_A") (pintype "passive"))
      (node (ref "D60") (pin "A") (pinfunction "A_A") (pintype "passive"))
      (node (ref "D61") (pin "A") (pinfunction "A_A") (pintype "passive"))
      (node (ref "D62") (pin "A") (pinfunction "A_A") (pintype "passive"))
      (node (ref "D63") (pin "A") (pinfunction "A_A") (pintype "passive"))
      (node (ref "D64") (pin "A") (pinfunction "A_A") (pintype "passive"))
      (node (ref "D65") (pin "A") (pinfunction "A_A") (pintype "passive"))
      (node (ref "D66") (pin "A") (pinfunction "A_A") (pintype "passive"))
      (node (ref "D67") (pin "A") (pinfunction "A_A") (pintype "passive"))
      (node (ref "D68") (pin "A") (pinfunction "A_A") (pintype "passive"))
      (node (ref "D69") (pin "A") (pinfunction "A_A") (pintype "passive"))
      (node (ref "D7") (pin "A") (pinfunction "A_A") (pintype "passive"))
      (node (ref "D70") (pin "A") (pinfunction "A_A") (pintype "passive"))
      (node (ref "D71") (pin "A") (pinfunction "A_A") (pintype "passive"))
      (node (ref "D72") (pin "A") (pinfunction "A_A") (pintype "passive"))
      (node (ref "D73") (pin "A") (pinfunction "A_A") (pintype "passive"))
      (node (ref "D74") (pin "A") (pinfunction "A_A") (pintype "passive"))
      (node (ref "D75") (pin "A") (pinfunction "A_A") (pintype "passive"))
      (node (ref "D76") (pin "A") (pinfunction "A_A") (pintype "passive"))
      (node (ref "D77") (pin "A") (pinfunction "A_A") (pintype "passive"))
      (node (ref "D78") (pin "A") (pinfunction "A_A") (pintype "passive"))
      (node (ref "D79") (pin "A") (pinfunction "A_A") (pintype "passive"))
      (node (ref "D8") (pin "A") (pinfunction "A_A") (pintype "passive"))
      (node (ref "D80") (pin "A") (pinfunction "A_A") (pintype "passive"))
      (node (ref "D81") (pin "A") (pinfunction "A_A") (pintype "passive"))
      (node (ref "D82") (pin "A") (pinfunction "A_A") (pintype "passive"))
      (node (ref "D83") (pin "A") (pinfunction "A_A") (pintype "passive"))
      (node (ref "D84") (pin "A") (pinfunction "A_A") (pintype "passive"))
      (node (ref "D85") (pin "A") (pinfunction "A_A") (pintype "passive"))
      (node (ref "D86") (pin "A") (pinfunction "A_A") (pintype "passive"))
      (node (ref "D87") (pin "A") (pinfunction "A_A") (pintype "passive"))
      (node (ref "D88") (pin "A") (pinfunction "A_A") (pintype "passive"))
      (node (ref "D89") (pin "A") (pinfunction "A_A") (pintype "passive"))
      (node (ref "D9") (pin "A") (pinfunction "A_A") (pintype "passive"))
      (node (ref "D90") (pin "A") (pinfunction "A_A") (pintype "passive"))
      (node (ref "D91") (pin "A") (pinfunction "A_A") (pintype "passive"))
      (node (ref "D92") (pin "A") (pinfunction "A_A") (pintype "passive"))
      (node (ref "D93") (pin "A") (pinfunction "A_A") (pintype "passive"))
      (node (ref "D94") (pin "A") (pinfunction "A_A") (pintype "passive"))
      (node (ref "D95") (pin "A") (pinfunction "A_A") (pintype "passive"))
      (node (ref "D96") (pin "A") (pinfunction "A_A") (pintype "passive"))
      (node (ref "D97") (pin "A") (pinfunction "A_A") (pintype "passive"))
      (node (ref "D98") (pin "A") (pinfunction "A_A") (pintype "passive"))
      (node (ref "D99") (pin "A") (pinfunction "A_A") (pintype "passive"))
      (node (ref "GND") (pin "1") (pinfunction "P_1") (pintype "passive"))
      (node (ref "IC10") (pin "GND") (pinfunction "GND_GND") (pintype "input"))
      (node (ref "IC9") (pin "GND") (pinfunction "GND_GND") (pintype "input"))
      (node (ref "Q1") (pin "S") (pinfunction "S_S") (pintype "passive"))
      (node (ref "Q35") (pin "S") (pinfunction "S_S") (pintype "passive"))
      (node (ref "Q37") (pin "S") (pinfunction "S_S") (pintype "passive"))
      (node (ref "Q39") (pin "S") (pinfunction "S_S") (pintype "passive"))
      (node (ref "Q41") (pin "S") (pinfunction "S_S") (pintype "passive"))
      (node (ref "Q43") (pin "S") (pinfunction "S_S") (pintype "passive"))
      (node (ref "Q45") (pin "S") (pinfunction "S_S") (pintype "passive"))
      (node (ref "Q47") (pin "S") (pinfunction "S_S") (pintype "passive"))
      (node (ref "Q49") (pin "S") (pinfunction "S_S") (pintype "passive"))
      (node (ref "Q51") (pin "S") (pinfunction "S_S") (pintype "passive"))
      (node (ref "Q53") (pin "S") (pinfunction "S_S") (pintype "passive"))
      (node (ref "Q55") (pin "S") (pinfunction "S_S") (pintype "passive"))
      (node (ref "Q57") (pin "S") (pinfunction "S_S") (pintype "passive"))
      (node (ref "Q59") (pin "S") (pinfunction "S_S") (pintype "passive"))
      (node (ref "Q61") (pin "S") (pinfunction "S_S") (pintype "passive"))
      (node (ref "Q63") (pin "S") (pinfunction "S_S") (pintype "passive"))
      (node (ref "Q65") (pin "S") (pinfunction "S_S") (pintype "passive"))
      (node (ref "Q67") (pin "S") (pinfunction "S_S") (pintype "passive"))
      (node (ref "Q69") (pin "S") (pinfunction "S_S") (pintype "passive"))
      (node (ref "Q71") (pin "S") (pinfunction "S_S") (pintype "passive"))
      (node (ref "Q73") (pin "S") (pinfunction "S_S") (pintype "passive"))
      (node (ref "Q75") (pin "S") (pinfunction "S_S") (pintype "passive"))
      (node (ref "Q77") (pin "S") (pinfunction "S_S") (pintype "passive"))
      (node (ref "Q79") (pin "S") (pinfunction "S_S") (pintype "passive"))
      (node (ref "Q81") (pin "S") (pinfunction "S_S") (pintype "passive"))
      (node (ref "Q83") (pin "S") (pinfunction "S_S") (pintype "passive"))
      (node (ref "Q85") (pin "S") (pinfunction "S_S") (pintype "passive"))
      (node (ref "Q87") (pin "S") (pinfunction "S_S") (pintype "passive"))
      (node (ref "Q89") (pin "S") (pinfunction "S_S") (pintype "passive"))
      (node (ref "Q91") (pin "S") (pinfunction "S_S") (pintype "passive"))
      (node (ref "Q93") (pin "S") (pinfunction "S_S") (pintype "passive"))
      (node (ref "Q95") (pin "S") (pinfunction "S_S") (pintype "passive"))
      (node (ref "R1") (pin "1") (pinfunction "1_1") (pintype "passive"))
      (node (ref "R103") (pin "1") (pinfunction "1_1") (pintype "passive"))
      (node (ref "R107") (pin "1") (pinfunction "1_1") (pintype "passive"))
      (node (ref "R11") (pin "2") (pinfunction "2_2") (pintype "passive"))
      (node (ref "R111") (pin "1") (pinfunction "1_1") (pintype "passive"))
      (node (ref "R115") (pin "1") (pinfunction "1_1") (pintype "passive"))
      (node (ref "R119") (pin "1") (pinfunction "1_1") (pintype "passive"))
      (node (ref "R123") (pin "1") (pinfunction "1_1") (pintype "passive"))
      (node (ref "R127") (pin "1") (pinfunction "1_1") (pintype "passive"))
      (node (ref "R131") (pin "1") (pinfunction "1_1") (pintype "passive"))
      (node (ref "R135") (pin "1") (pinfunction "1_1") (pintype "passive"))
      (node (ref "R14") (pin "2") (pinfunction "2_2") (pintype "passive"))
      (node (ref "R142") (pin "2") (pinfunction "2_2") (pintype "passive"))
      (node (ref "R146") (pin "2") (pinfunction "2_2") (pintype "passive"))
      (node (ref "R15") (pin "1") (pinfunction "1_1") (pintype "passive"))
      (node (ref "R150") (pin "2") (pinfunction "2_2") (pintype "passive"))
      (node (ref "R154") (pin "2") (pinfunction "2_2") (pintype "passive"))
      (node (ref "R158") (pin "2") (pinfunction "2_2") (pintype "passive"))
      (node (ref "R162") (pin "2") (pinfunction "2_2") (pintype "passive"))
      (node (ref "R166") (pin "2") (pinfunction "2_2") (pintype "passive"))
      (node (ref "R170") (pin "2") (pinfunction "2_2") (pintype "passive"))
      (node (ref "R174") (pin "2") (pinfunction "2_2") (pintype "passive"))
      (node (ref "R178") (pin "2") (pinfunction "2_2") (pintype "passive"))
      (node (ref "R182") (pin "2") (pinfunction "2_2") (pintype "passive"))
      (node (ref "R186") (pin "2") (pinfunction "2_2") (pintype "passive"))
      (node (ref "R19") (pin "1") (pinfunction "1_1") (pintype "passive"))
      (node (ref "R190") (pin "2") (pinfunction "2_2") (pintype "passive"))
      (node (ref "R194") (pin "2") (pinfunction "2_2") (pintype "passive"))
      (node (ref "R198") (pin "2") (pinfunction "2_2") (pintype "passive"))
      (node (ref "R202") (pin "2") (pinfunction "2_2") (pintype "passive"))
      (node (ref "R206") (pin "2") (pinfunction "2_2") (pintype "passive"))
      (node (ref "R210") (pin "2") (pinfunction "2_2") (pintype "passive"))
      (node (ref "R214") (pin "2") (pinfunction "2_2") (pintype "passive"))
      (node (ref "R218") (pin "2") (pinfunction "2_2") (pintype "passive"))
      (node (ref "R222") (pin "2") (pinfunction "2_2") (pintype "passive"))
      (node (ref "R226") (pin "2") (pinfunction "2_2") (pintype "passive"))
      (node (ref "R23") (pin "1") (pinfunction "1_1") (pintype "passive"))
      (node (ref "R230") (pin "2") (pinfunction "2_2") (pintype "passive"))
      (node (ref "R234") (pin "2") (pinfunction "2_2") (pintype "passive"))
      (node (ref "R238") (pin "2") (pinfunction "2_2") (pintype "passive"))
      (node (ref "R242") (pin "2") (pinfunction "2_2") (pintype "passive"))
      (node (ref "R246") (pin "2") (pinfunction "2_2") (pintype "passive"))
      (node (ref "R250") (pin "2") (pinfunction "2_2") (pintype "passive"))
      (node (ref "R254") (pin "2") (pinfunction "2_2") (pintype "passive"))
      (node (ref "R258") (pin "2") (pinfunction "2_2") (pintype "passive"))
      (node (ref "R260") (pin "2") (pinfunction "2_2") (pintype "passive"))
      (node (ref "R262") (pin "2") (pinfunction "2_2") (pintype "passive"))
      (node (ref "R264") (pin "2") (pinfunction "2_2") (pintype "passive"))
      (node (ref "R266") (pin "2") (pinfunction "2_2") (pintype "passive"))
      (node (ref "R268") (pin "2") (pinfunction "2_2") (pintype "passive"))
      (node (ref "R27") (pin "1") (pinfunction "1_1") (pintype "passive"))
      (node (ref "R270") (pin "2") (pinfunction "2_2") (pintype "passive"))
      (node (ref "R272") (pin "2") (pinfunction "2_2") (pintype "passive"))
      (node (ref "R274") (pin "2") (pinfunction "2_2") (pintype "passive"))
      (node (ref "R276") (pin "2") (pinfunction "2_2") (pintype "passive"))
      (node (ref "R278") (pin "2") (pinfunction "2_2") (pintype "passive"))
      (node (ref "R280") (pin "2") (pinfunction "2_2") (pintype "passive"))
      (node (ref "R282") (pin "2") (pinfunction "2_2") (pintype "passive"))
      (node (ref "R284") (pin "2") (pinfunction "2_2") (pintype "passive"))
      (node (ref "R286") (pin "2") (pinfunction "2_2") (pintype "passive"))
      (node (ref "R288") (pin "2") (pinfunction "2_2") (pintype "passive"))
      (node (ref "R290") (pin "2") (pinfunction "2_2") (pintype "passive"))
      (node (ref "R292") (pin "2") (pinfunction "2_2") (pintype "passive"))
      (node (ref "R294") (pin "2") (pinfunction "2_2") (pintype "passive"))
      (node (ref "R296") (pin "2") (pinfunction "2_2") (pintype "passive"))
      (node (ref "R298") (pin "2") (pinfunction "2_2") (pintype "passive"))
      (node (ref "R300") (pin "2") (pinfunction "2_2") (pintype "passive"))
      (node (ref "R302") (pin "2") (pinfunction "2_2") (pintype "passive"))
      (node (ref "R304") (pin "2") (pinfunction "2_2") (pintype "passive"))
      (node (ref "R306") (pin "2") (pinfunction "2_2") (pintype "passive"))
      (node (ref "R308") (pin "2") (pinfunction "2_2") (pintype "passive"))
      (node (ref "R31") (pin "1") (pinfunction "1_1") (pintype "passive"))
      (node (ref "R310") (pin "2") (pinfunction "2_2") (pintype "passive"))
      (node (ref "R312") (pin "2") (pinfunction "2_2") (pintype "passive"))
      (node (ref "R314") (pin "2") (pinfunction "2_2") (pintype "passive"))
      (node (ref "R316") (pin "2") (pinfunction "2_2") (pintype "passive"))
      (node (ref "R318") (pin "2") (pinfunction "2_2") (pintype "passive"))
      (node (ref "R320") (pin "2") (pinfunction "2_2") (pintype "passive"))
      (node (ref "R35") (pin "1") (pinfunction "1_1") (pintype "passive"))
      (node (ref "R39") (pin "1") (pinfunction "1_1") (pintype "passive"))
      (node (ref "R43") (pin "1") (pinfunction "1_1") (pintype "passive"))
      (node (ref "R47") (pin "1") (pinfunction "1_1") (pintype "passive"))
      (node (ref "R51") (pin "1") (pinfunction "1_1") (pintype "passive"))
      (node (ref "R55") (pin "1") (pinfunction "1_1") (pintype "passive"))
      (node (ref "R59") (pin "1") (pinfunction "1_1") (pintype "passive"))
      (node (ref "R63") (pin "1") (pinfunction "1_1") (pintype "passive"))
      (node (ref "R67") (pin "1") (pinfunction "1_1") (pintype "passive"))
      (node (ref "R71") (pin "1") (pinfunction "1_1") (pintype "passive"))
      (node (ref "R75") (pin "1") (pinfunction "1_1") (pintype "passive"))
      (node (ref "R79") (pin "1") (pinfunction "1_1") (pintype "passive"))
      (node (ref "R83") (pin "1") (pinfunction "1_1") (pintype "passive"))
      (node (ref "R87") (pin "1") (pinfunction "1_1") (pintype "passive"))
      (node (ref "R9") (pin "2") (pinfunction "2_2") (pintype "passive"))
      (node (ref "R91") (pin "1") (pinfunction "1_1") (pintype "passive"))
      (node (ref "R95") (pin "1") (pinfunction "1_1") (pintype "passive"))
      (node (ref "R99") (pin "1") (pinfunction "1_1") (pintype "passive"))
      (node (ref "T1") (pin "2") (pinfunction "2_2") (pintype "passive"))
    )
    (net (code "16") (name "H1") (class "Default")
      (node (ref "Q45") (pin "D") (pinfunction "D_D") (pintype "passive"))
      (node (ref "Q46") (pin "D") (pinfunction "D_D") (pintype "passive"))
      (node (ref "Q9") (pin "D") (pinfunction "D_D") (pintype "passive"))
      (node (ref "R36") (pin "1") (pinfunction "1_1") (pintype "passive"))
      (node (ref "SIDE1") (pin "16") (pinfunction "16_16") (pintype "passive"))
    )
    (net (code "17") (name "H2") (class "Default")
      (node (ref "Q23") (pin "D") (pinfunction "D_D") (pintype "passive"))
      (node (ref "Q73") (pin "D") (pinfunction "D_D") (pintype "passive"))
      (node (ref "Q74") (pin "D") (pinfunction "D_D") (pintype "passive"))
      (node (ref "R92") (pin "1") (pinfunction "1_1") (pintype "passive"))
      (node (ref "SIDE2") (pin "12") (pinfunction "12_12") (pintype "passive"))
    )
    (net (code "18") (name "J1") (class "Default")
      (node (ref "Q10") (pin "D") (pinfunction "D_D") (pintype "passive"))
      (node (ref "Q47") (pin "D") (pinfunction "D_D") (pintype "passive"))
      (node (ref "Q48") (pin "D") (pinfunction "D_D") (pintype "passive"))
      (node (ref "R40") (pin "1") (pinfunction "1_1") (pintype "passive"))
      (node (ref "SIDE1") (pin "20") (pinfunction "20_20") (pintype "passive"))
    )
    (net (code "19") (name "J2") (class "Default")
      (node (ref "Q24") (pin "D") (pinfunction "D_D") (pintype "passive"))
      (node (ref "Q75") (pin "D") (pinfunction "D_D") (pintype "passive"))
      (node (ref "Q76") (pin "D") (pinfunction "D_D") (pintype "passive"))
      (node (ref "R96") (pin "1") (pinfunction "1_1") (pintype "passive"))
      (node (ref "SIDE2") (pin "14") (pinfunction "14_14") (pintype "passive"))
    )
    (net (code "20") (name "K1") (class "Default")
      (node (ref "Q11") (pin "D") (pinfunction "D_D") (pintype "passive"))
      (node (ref "Q49") (pin "D") (pinfunction "D_D") (pintype "passive"))
      (node (ref "Q50") (pin "D") (pinfunction "D_D") (pintype "passive"))
      (node (ref "R44") (pin "1") (pinfunction "1_1") (pintype "passive"))
      (node (ref "SIDE1") (pin "18") (pinfunction "18_18") (pintype "passive"))
    )
    (net (code "21") (name "K2") (class "Default")
      (node (ref "Q25") (pin "D") (pinfunction "D_D") (pintype "passive"))
      (node (ref "Q77") (pin "D") (pinfunction "D_D") (pintype "passive"))
      (node (ref "Q78") (pin "D") (pinfunction "D_D") (pintype "passive"))
      (node (ref "R100") (pin "1") (pinfunction "1_1") (pintype "passive"))
      (node (ref "SIDE2") (pin "16") (pinfunction "16_16") (pintype "passive"))
    )
    (net (code "22") (name "L1") (class "Default")
      (node (ref "Q12") (pin "D") (pinfunction "D_D") (pintype "passive"))
      (node (ref "Q51") (pin "D") (pinfunction "D_D") (pintype "passive"))
      (node (ref "Q52") (pin "D") (pinfunction "D_D") (pintype "passive"))
      (node (ref "R48") (pin "1") (pinfunction "1_1") (pintype "passive"))
      (node (ref "SIDE1") (pin "24") (pinfunction "24_24") (pintype "passive"))
    )
    (net (code "23") (name "L2") (class "Default")
      (node (ref "Q26") (pin "D") (pinfunction "D_D") (pintype "passive"))
      (node (ref "Q79") (pin "D") (pinfunction "D_D") (pintype "passive"))
      (node (ref "Q80") (pin "D") (pinfunction "D_D") (pintype "passive"))
      (node (ref "R104") (pin "1") (pinfunction "1_1") (pintype "passive"))
      (node (ref "SIDE2") (pin "18") (pinfunction "18_18") (pintype "passive"))
    )
    (net (code "24") (name "M1") (class "Default")
      (node (ref "Q13") (pin "D") (pinfunction "D_D") (pintype "passive"))
      (node (ref "Q53") (pin "D") (pinfunction "D_D") (pintype "passive"))
      (node (ref "Q54") (pin "D") (pinfunction "D_D") (pintype "passive"))
      (node (ref "R52") (pin "1") (pinfunction "1_1") (pintype "passive"))
      (node (ref "SIDE1") (pin "28") (pinfunction "28_28") (pintype "passive"))
    )
    (net (code "25") (name "M2") (class "Default")
      (node (ref "Q27") (pin "D") (pinfunction "D_D") (pintype "passive"))
      (node (ref "Q81") (pin "D") (pinfunction "D_D") (pintype "passive"))
      (node (ref "Q82") (pin "D") (pinfunction "D_D") (pintype "passive"))
      (node (ref "R108") (pin "1") (pinfunction "1_1") (pintype "passive"))
      (node (ref "SIDE2") (pin "20") (pinfunction "20_20") (pintype "passive"))
    )
    (net (code "26") (name "N1") (class "Default")
      (node (ref "Q14") (pin "D") (pinfunction "D_D") (pintype "passive"))
      (node (ref "Q55") (pin "D") (pinfunction "D_D") (pintype "passive"))
      (node (ref "Q56") (pin "D") (pinfunction "D_D") (pintype "passive"))
      (node (ref "R56") (pin "1") (pinfunction "1_1") (pintype "passive"))
      (node (ref "SIDE1") (pin "22") (pinfunction "22_22") (pintype "passive"))
    )
    (net (code "27") (name "N2") (class "Default")
      (node (ref "Q28") (pin "D") (pinfunction "D_D") (pintype "passive"))
      (node (ref "Q83") (pin "D") (pinfunction "D_D") (pintype "passive"))
      (node (ref "Q84") (pin "D") (pinfunction "D_D") (pintype "passive"))
      (node (ref "R112") (pin "1") (pinfunction "1_1") (pintype "passive"))
      (node (ref "SIDE2") (pin "22") (pinfunction "22_22") (pintype "passive"))
    )
    (net (code "28") (name "Net-(D129-PadA)") (class "Default")
      (node (ref "D129") (pin "A") (pinfunction "A_A") (pintype "passive"))
      (node (ref "Q10") (pin "G") (pinfunction "G_G") (pintype "passive"))
      (node (ref "R159") (pin "1") (pinfunction "1_1") (pintype "passive"))
    )
    (net (code "29") (name "Net-(D130-PadA)") (class "Default")
      (node (ref "D130") (pin "A") (pinfunction "A_A") (pintype "passive"))
      (node (ref "Q9") (pin "G") (pinfunction "G_G") (pintype "passive"))
      (node (ref "R155") (pin "1") (pinfunction "1_1") (pintype "passive"))
    )
    (net (code "30") (name "Net-(D131-PadA)") (class "Default")
      (node (ref "D131") (pin "A") (pinfunction "A_A") (pintype "passive"))
      (node (ref "Q8") (pin "G") (pinfunction "G_G") (pintype "passive"))
      (node (ref "R151") (pin "1") (pinfunction "1_1") (pintype "passive"))
    )
    (net (code "31") (name "Net-(D132-PadA)") (class "Default")
      (node (ref "D132") (pin "A") (pinfunction "A_A") (pintype "passive"))
      (node (ref "Q3") (pin "G") (pinfunction "G_G") (pintype "passive"))
      (node (ref "R2") (pin "1") (pinfunction "1_1") (pintype "passive"))
    )
    (net (code "32") (name "Net-(D133-PadA)") (class "Default")
      (node (ref "D133") (pin "A") (pinfunction "A_A") (pintype "passive"))
      (node (ref "Q7") (pin "G") (pinfunction "G_G") (pintype "passive"))
      (node (ref "R147") (pin "1") (pinfunction "1_1") (pintype "passive"))
    )
    (net (code "33") (name "Net-(D134-PadA)") (class "Default")
      (node (ref "D134") (pin "A") (pinfunction "A_A") (pintype "passive"))
      (node (ref "Q6") (pin "G") (pinfunction "G_G") (pintype "passive"))
      (node (ref "R143") (pin "1") (pinfunction "1_1") (pintype "passive"))
    )
    (net (code "34") (name "Net-(D135-PadA)") (class "Default")
      (node (ref "D135") (pin "A") (pinfunction "A_A") (pintype "passive"))
      (node (ref "Q5") (pin "G") (pinfunction "G_G") (pintype "passive"))
      (node (ref "R139") (pin "1") (pinfunction "1_1") (pintype "passive"))
    )
    (net (code "35") (name "Net-(D136-PadA)") (class "Default")
      (node (ref "D136") (pin "A") (pinfunction "A_A") (pintype "passive"))
      (node (ref "Q4") (pin "G") (pinfunction "G_G") (pintype "passive"))
      (node (ref "R4") (pin "1") (pinfunction "1_1") (pintype "passive"))
    )
    (net (code "36") (name "Net-(D137-PadA)") (class "Default")
      (node (ref "D137") (pin "A") (pinfunction "A_A") (pintype "passive"))
      (node (ref "Q18") (pin "G") (pinfunction "G_G") (pintype "passive"))
      (node (ref "R191") (pin "1") (pinfunction "1_1") (pintype "passive"))
    )
    (net (code "37") (name "Net-(D138-PadA)") (class "Default")
      (node (ref "D138") (pin "A") (pinfunction "A_A") (pintype "passive"))
      (node (ref "Q17") (pin "G") (pinfunction "G_G") (pintype "passive"))
      (node (ref "R187") (pin "1") (pinfunction "1_1") (pintype "passive"))
    )
    (net (code "38") (name "Net-(D139-PadA)") (class "Default")
      (node (ref "D139") (pin "A") (pinfunction "A_A") (pintype "passive"))
      (node (ref "Q16") (pin "G") (pinfunction "G_G") (pintype "passive"))
      (node (ref "R183") (pin "1") (pinfunction "1_1") (pintype "passive"))
    )
    (net (code "39") (name "Net-(D140-PadA)") (class "Default")
      (node (ref "D140") (pin "A") (pinfunction "A_A") (pintype "passive"))
      (node (ref "Q15") (pin "G") (pinfunction "G_G") (pintype "passive"))
      (node (ref "R179") (pin "1") (pinfunction "1_1") (pintype "passive"))
    )
    (net (code "40") (name "Net-(D141-PadA)") (class "Default")
      (node (ref "D141") (pin "A") (pinfunction "A_A") (pintype "passive"))
      (node (ref "Q14") (pin "G") (pinfunction "G_G") (pintype "passive"))
      (node (ref "R175") (pin "1") (pinfunction "1_1") (pintype "passive"))
    )
    (net (code "41") (name "Net-(D142-PadA)") (class "Default")
      (node (ref "D142") (pin "A") (pinfunction "A_A") (pintype "passive"))
      (node (ref "Q13") (pin "G") (pinfunction "G_G") (pintype "passive"))
      (node (ref "R171") (pin "1") (pinfunction "1_1") (pintype "passive"))
    )
    (net (code "42") (name "Net-(D143-PadA)") (class "Default")
      (node (ref "D143") (pin "A") (pinfunction "A_A") (pintype "passive"))
      (node (ref "Q12") (pin "G") (pinfunction "G_G") (pintype "passive"))
      (node (ref "R167") (pin "1") (pinfunction "1_1") (pintype "passive"))
    )
    (net (code "43") (name "Net-(D144-PadA)") (class "Default")
      (node (ref "D144") (pin "A") (pinfunction "A_A") (pintype "passive"))
      (node (ref "Q11") (pin "G") (pinfunction "G_G") (pintype "passive"))
      (node (ref "R163") (pin "1") (pinfunction "1_1") (pintype "passive"))
    )
    (net (code "44") (name "Net-(D145-PadA)") (class "Default")
      (node (ref "D145") (pin "A") (pinfunction "A_A") (pintype "passive"))
      (node (ref "Q26") (pin "G") (pinfunction "G_G") (pintype "passive"))
      (node (ref "R223") (pin "1") (pinfunction "1_1") (pintype "passive"))
    )
    (net (code "45") (name "Net-(D146-PadA)") (class "Default")
      (node (ref "D146") (pin "A") (pinfunction "A_A") (pintype "passive"))
      (node (ref "Q25") (pin "G") (pinfunction "G_G") (pintype "passive"))
      (node (ref "R219") (pin "1") (pinfunction "1_1") (pintype "passive"))
    )
    (net (code "46") (name "Net-(D147-PadA)") (class "Default")
      (node (ref "D147") (pin "A") (pinfunction "A_A") (pintype "passive"))
      (node (ref "Q24") (pin "G") (pinfunction "G_G") (pintype "passive"))
      (node (ref "R215") (pin "1") (pinfunction "1_1") (pintype "passive"))
    )
    (net (code "47") (name "Net-(D148-PadA)") (class "Default")
      (node (ref "D148") (pin "A") (pinfunction "A_A") (pintype "passive"))
      (node (ref "Q23") (pin "G") (pinfunction "G_G") (pintype "passive"))
      (node (ref "R211") (pin "1") (pinfunction "1_1") (pintype "passive"))
    )
    (net (code "48") (name "Net-(D149-PadA)") (class "Default")
      (node (ref "D149") (pin "A") (pinfunction "A_A") (pintype "passive"))
      (node (ref "Q22") (pin "G") (pinfunction "G_G") (pintype "passive"))
      (node (ref "R207") (pin "1") (pinfunction "1_1") (pintype "passive"))
    )
    (net (code "49") (name "Net-(D150-PadA)") (class "Default")
      (node (ref "D150") (pin "A") (pinfunction "A_A") (pintype "passive"))
      (node (ref "Q21") (pin "G") (pinfunction "G_G") (pintype "passive"))
      (node (ref "R203") (pin "1") (pinfunction "1_1") (pintype "passive"))
    )
    (net (code "50") (name "Net-(D151-PadA)") (class "Default")
      (node (ref "D151") (pin "A") (pinfunction "A_A") (pintype "passive"))
      (node (ref "Q20") (pin "G") (pinfunction "G_G") (pintype "passive"))
      (node (ref "R199") (pin "1") (pinfunction "1_1") (pintype "passive"))
    )
    (net (code "51") (name "Net-(D152-PadA)") (class "Default")
      (node (ref "D152") (pin "A") (pinfunction "A_A") (pintype "passive"))
      (node (ref "Q19") (pin "G") (pinfunction "G_G") (pintype "passive"))
      (node (ref "R195") (pin "1") (pinfunction "1_1") (pintype "passive"))
    )
    (net (code "52") (name "Net-(D153-PadA)") (class "Default")
      (node (ref "D153") (pin "A") (pinfunction "A_A") (pintype "passive"))
      (node (ref "Q34") (pin "G") (pinfunction "G_G") (pintype "passive"))
      (node (ref "R255") (pin "1") (pinfunction "1_1") (pintype "passive"))
    )
    (net (code "53") (name "Net-(D154-PadA)") (class "Default")
      (node (ref "D154") (pin "A") (pinfunction "A_A") (pintype "passive"))
      (node (ref "Q33") (pin "G") (pinfunction "G_G") (pintype "passive"))
      (node (ref "R251") (pin "1") (pinfunction "1_1") (pintype "passive"))
    )
    (net (code "54") (name "Net-(D155-PadA)") (class "Default")
      (node (ref "D155") (pin "A") (pinfunction "A_A") (pintype "passive"))
      (node (ref "Q32") (pin "G") (pinfunction "G_G") (pintype "passive"))
      (node (ref "R247") (pin "1") (pinfunction "1_1") (pintype "passive"))
    )
    (net (code "55") (name "Net-(D156-PadA)") (class "Default")
      (node (ref "D156") (pin "A") (pinfunction "A_A") (pintype "passive"))
      (node (ref "Q31") (pin "G") (pinfunction "G_G") (pintype "passive"))
      (node (ref "R243") (pin "1") (pinfunction "1_1") (pintype "passive"))
    )
    (net (code "56") (name "Net-(D157-PadA)") (class "Default")
      (node (ref "D157") (pin "A") (pinfunction "A_A") (pintype "passive"))
      (node (ref "Q30") (pin "G") (pinfunction "G_G") (pintype "passive"))
      (node (ref "R239") (pin "1") (pinfunction "1_1") (pintype "passive"))
    )
    (net (code "57") (name "Net-(D158-PadA)") (class "Default")
      (node (ref "D158") (pin "A") (pinfunction "A_A") (pintype "passive"))
      (node (ref "Q29") (pin "G") (pinfunction "G_G") (pintype "passive"))
      (node (ref "R235") (pin "1") (pinfunction "1_1") (pintype "passive"))
    )
    (net (code "58") (name "Net-(D159-PadA)") (class "Default")
      (node (ref "D159") (pin "A") (pinfunction "A_A") (pintype "passive"))
      (node (ref "Q28") (pin "G") (pinfunction "G_G") (pintype "passive"))
      (node (ref "R231") (pin "1") (pinfunction "1_1") (pintype "passive"))
    )
    (net (code "59") (name "Net-(D160-PadA)") (class "Default")
      (node (ref "D160") (pin "A") (pinfunction "A_A") (pintype "passive"))
      (node (ref "Q27") (pin "G") (pinfunction "G_G") (pintype "passive"))
      (node (ref "R227") (pin "1") (pinfunction "1_1") (pintype "passive"))
    )
    (net (code "60") (name "Net-(IC1A-+IN)") (class "Default")
      (node (ref "IC1") (pin "5") (pinfunction "+IN_5") (pintype "input"))
      (node (ref "R1") (pin "2") (pinfunction "2_2") (pintype "passive"))
      (node (ref "R3") (pin "2") (pinfunction "2_2") (pintype "passive"))
    )
    (net (code "61") (name "Net-(IC1A--IN)") (class "Default")
      (node (ref "IC1") (pin "4") (pinfunction "-IN_4") (pintype "input"))
      (node (ref "JP1") (pin "1") (pinfunction "1_1") (pintype "passive"))
    )
    (net (code "62") (name "Net-(IC1A-OUT)") (class "Default")
      (node (ref "IC1") (pin "2") (pinfunction "OUT_2") (pintype "open_collector"))
      (node (ref "R6") (pin "1") (pinfunction "1_1") (pintype "passive"))
      (node (ref "R7") (pin "2") (pinfunction "2_2") (pintype "passive"))
    )
    (net (code "63") (name "Net-(IC1B-+IN)") (class "Default")
      (node (ref "IC1") (pin "7") (pinfunction "+IN_7") (pintype "input"))
      (node (ref "R15") (pin "2") (pinfunction "2_2") (pintype "passive"))
      (node (ref "R16") (pin "2") (pinfunction "2_2") (pintype "passive"))
    )
    (net (code "64") (name "Net-(IC1B--IN)") (class "Default")
      (node (ref "IC1") (pin "6") (pinfunction "-IN_6") (pintype "input"))
      (node (ref "JP3") (pin "1") (pinfunction "1_1") (pintype "passive"))
    )
    (net (code "65") (name "Net-(IC1B-OUT)") (class "Default")
      (node (ref "IC1") (pin "1") (pinfunction "OUT_1") (pintype "open_collector"))
      (node (ref "R17") (pin "1") (pinfunction "1_1") (pintype "passive"))
      (node (ref "R18") (pin "2") (pinfunction "2_2") (pintype "passive"))
    )
    (net (code "66") (name "Net-(IC1C-+IN)") (class "Default")
      (node (ref "IC1") (pin "9") (pinfunction "+IN_9") (pintype "input"))
      (node (ref "R19") (pin "2") (pinfunction "2_2") (pintype "passive"))
      (node (ref "R20") (pin "2") (pinfunction "2_2") (pintype "passive"))
    )
    (net (code "67") (name "Net-(IC1C--IN)") (class "Default")
      (node (ref "IC1") (pin "8") (pinfunction "-IN_8") (pintype "input"))
      (node (ref "JP4") (pin "1") (pinfunction "1_1") (pintype "passive"))
    )
    (net (code "68") (name "Net-(IC1C-OUT)") (class "Default")
      (node (ref "IC1") (pin "14") (pinfunction "OUT_14") (pintype "open_collector"))
      (node (ref "R21") (pin "1") (pinfunction "1_1") (pintype "passive"))
      (node (ref "R22") (pin "2") (pinfunction "2_2") (pintype "passive"))
    )
    (net (code "69") (name "Net-(IC1D-+IN)") (class "Default")
      (node (ref "IC1") (pin "11") (pinfunction "+IN_11") (pintype "input"))
      (node (ref "R23") (pin "2") (pinfunction "2_2") (pintype "passive"))
      (node (ref "R24") (pin "2") (pinfunction "2_2") (pintype "passive"))
    )
    (net (code "70") (name "Net-(IC1D--IN)") (class "Default")
      (node (ref "IC1") (pin "10") (pinfunction "-IN_10") (pintype "input"))
      (node (ref "JP5") (pin "1") (pinfunction "1_1") (pintype "passive"))
    )
    (net (code "71") (name "Net-(IC1D-OUT)") (class "Default")
      (node (ref "IC1") (pin "13") (pinfunction "OUT_13") (pintype "open_collector"))
      (node (ref "R25") (pin "1") (pinfunction "1_1") (pintype "passive"))
      (node (ref "R26") (pin "2") (pinfunction "2_2") (pintype "passive"))
    )
    (net (code "72") (name "Net-(IC2A-+IN)") (class "Default")
      (node (ref "IC2") (pin "5") (pinfunction "+IN_5") (pintype "input"))
      (node (ref "R27") (pin "2") (pinfunction "2_2") (pintype "passive"))
      (node (ref "R28") (pin "2") (pinfunction "2_2") (pintype "passive"))
    )
    (net (code "73") (name "Net-(IC2A--IN)") (class "Default")
      (node (ref "IC2") (pin "4") (pinfunction "-IN_4") (pintype "input"))
      (node (ref "JP6") (pin "1") (pinfunction "1_1") (pintype "passive"))
    )
    (net (code "74") (name "Net-(IC2A-OUT)") (class "Default")
      (node (ref "IC2") (pin "2") (pinfunction "OUT_2") (pintype "open_collector"))
      (node (ref "R29") (pin "1") (pinfunction "1_1") (pintype "passive"))
      (node (ref "R30") (pin "2") (pinfunction "2_2") (pintype "passive"))
    )
    (net (code "75") (name "Net-(IC2B-+IN)") (class "Default")
      (node (ref "IC2") (pin "7") (pinfunction "+IN_7") (pintype "input"))
      (node (ref "R31") (pin "2") (pinfunction "2_2") (pintype "passive"))
      (node (ref "R32") (pin "2") (pinfunction "2_2") (pintype "passive"))
    )
    (net (code "76") (name "Net-(IC2B--IN)") (class "Default")
      (node (ref "IC2") (pin "6") (pinfunction "-IN_6") (pintype "input"))
      (node (ref "JP7") (pin "1") (pinfunction "1_1") (pintype "passive"))
    )
    (net (code "77") (name "Net-(IC2B-OUT)") (class "Default")
      (node (ref "IC2") (pin "1") (pinfunction "OUT_1") (pintype "open_collector"))
      (node (ref "R33") (pin "1") (pinfunction "1_1") (pintype "passive"))
      (node (ref "R34") (pin "2") (pinfunction "2_2") (pintype "passive"))
    )
    (net (code "78") (name "Net-(IC2C-+IN)") (class "Default")
      (node (ref "IC2") (pin "9") (pinfunction "+IN_9") (pintype "input"))
      (node (ref "R35") (pin "2") (pinfunction "2_2") (pintype "passive"))
      (node (ref "R36") (pin "2") (pinfunction "2_2") (pintype "passive"))
    )
    (net (code "79") (name "Net-(IC2C--IN)") (class "Default")
      (node (ref "IC2") (pin "8") (pinfunction "-IN_8") (pintype "input"))
      (node (ref "JP8") (pin "1") (pinfunction "1_1") (pintype "passive"))
    )
    (net (code "80") (name "Net-(IC2C-OUT)") (class "Default")
      (node (ref "IC2") (pin "14") (pinfunction "OUT_14") (pintype "open_collector"))
      (node (ref "R37") (pin "1") (pinfunction "1_1") (pintype "passive"))
      (node (ref "R38") (pin "2") (pinfunction "2_2") (pintype "passive"))
    )
    (net (code "81") (name "Net-(IC2D-+IN)") (class "Default")
      (node (ref "IC2") (pin "11") (pinfunction "+IN_11") (pintype "input"))
      (node (ref "R39") (pin "2") (pinfunction "2_2") (pintype "passive"))
      (node (ref "R40") (pin "2") (pinfunction "2_2") (pintype "passive"))
    )
    (net (code "82") (name "Net-(IC2D--IN)") (class "Default")
      (node (ref "IC2") (pin "10") (pinfunction "-IN_10") (pintype "input"))
      (node (ref "JP9") (pin "1") (pinfunction "1_1") (pintype "passive"))
    )
    (net (code "83") (name "Net-(IC2D-OUT)") (class "Default")
      (node (ref "IC2") (pin "13") (pinfunction "OUT_13") (pintype "open_collector"))
      (node (ref "R41") (pin "1") (pinfunction "1_1") (pintype "passive"))
      (node (ref "R42") (pin "2") (pinfunction "2_2") (pintype "passive"))
    )
    (net (code "84") (name "Net-(IC3A-+IN)") (class "Default")
      (node (ref "IC3") (pin "5") (pinfunction "+IN_5") (pintype "input"))
      (node (ref "R43") (pin "2") (pinfunction "2_2") (pintype "passive"))
      (node (ref "R44") (pin "2") (pinfunction "2_2") (pintype "passive"))
    )
    (net (code "85") (name "Net-(IC3A--IN)") (class "Default")
      (node (ref "IC3") (pin "4") (pinfunction "-IN_4") (pintype "input"))
      (node (ref "JP10") (pin "1") (pinfunction "1_1") (pintype "passive"))
    )
    (net (code "86") (name "Net-(IC3A-OUT)") (class "Default")
      (node (ref "IC3") (pin "2") (pinfunction "OUT_2") (pintype "open_collector"))
      (node (ref "R45") (pin "1") (pinfunction "1_1") (pintype "passive"))
      (node (ref "R46") (pin "2") (pinfunction "2_2") (pintype "passive"))
    )
    (net (code "87") (name "Net-(IC3B-+IN)") (class "Default")
      (node (ref "IC3") (pin "7") (pinfunction "+IN_7") (pintype "input"))
      (node (ref "R47") (pin "2") (pinfunction "2_2") (pintype "passive"))
      (node (ref "R48") (pin "2") (pinfunction "2_2") (pintype "passive"))
    )
    (net (code "88") (name "Net-(IC3B--IN)") (class "Default")
      (node (ref "IC3") (pin "6") (pinfunction "-IN_6") (pintype "input"))
      (node (ref "JP11") (pin "1") (pinfunction "1_1") (pintype "passive"))
    )
    (net (code "89") (name "Net-(IC3B-OUT)") (class "Default")
      (node (ref "IC3") (pin "1") (pinfunction "OUT_1") (pintype "open_collector"))
      (node (ref "R49") (pin "1") (pinfunction "1_1") (pintype "passive"))
      (node (ref "R50") (pin "2") (pinfunction "2_2") (pintype "passive"))
    )
    (net (code "90") (name "Net-(IC3C-+IN)") (class "Default")
      (node (ref "IC3") (pin "9") (pinfunction "+IN_9") (pintype "input"))
      (node (ref "R51") (pin "2") (pinfunction "2_2") (pintype "passive"))
      (node (ref "R52") (pin "2") (pinfunction "2_2") (pintype "passive"))
    )
    (net (code "91") (name "Net-(IC3C--IN)") (class "Default")
      (node (ref "IC3") (pin "8") (pinfunction "-IN_8") (pintype "input"))
      (node (ref "JP12") (pin "1") (pinfunction "1_1") (pintype "passive"))
    )
    (net (code "92") (name "Net-(IC3C-OUT)") (class "Default")
      (node (ref "IC3") (pin "14") (pinfunction "OUT_14") (pintype "open_collector"))
      (node (ref "R53") (pin "1") (pinfunction "1_1") (pintype "passive"))
      (node (ref "R54") (pin "2") (pinfunction "2_2") (pintype "passive"))
    )
    (net (code "93") (name "Net-(IC3D-+IN)") (class "Default")
      (node (ref "IC3") (pin "11") (pinfunction "+IN_11") (pintype "input"))
      (node (ref "R55") (pin "2") (pinfunction "2_2") (pintype "passive"))
      (node (ref "R56") (pin "2") (pinfunction "2_2") (pintype "passive"))
    )
    (net (code "94") (name "Net-(IC3D--IN)") (class "Default")
      (node (ref "IC3") (pin "10") (pinfunction "-IN_10") (pintype "input"))
      (node (ref "JP13") (pin "1") (pinfunction "1_1") (pintype "passive"))
    )
    (net (code "95") (name "Net-(IC3D-OUT)") (class "Default")
      (node (ref "IC3") (pin "13") (pinfunction "OUT_13") (pintype "open_collector"))
      (node (ref "R57") (pin "1") (pinfunction "1_1") (pintype "passive"))
      (node (ref "R58") (pin "2") (pinfunction "2_2") (pintype "passive"))
    )
    (net (code "96") (name "Net-(IC4A-+IN)") (class "Default")
      (node (ref "IC4") (pin "5") (pinfunction "+IN_5") (pintype "input"))
      (node (ref "R59") (pin "2") (pinfunction "2_2") (pintype "passive"))
      (node (ref "R60") (pin "2") (pinfunction "2_2") (pintype "passive"))
    )
    (net (code "97") (name "Net-(IC4A--IN)") (class "Default")
      (node (ref "IC4") (pin "4") (pinfunction "-IN_4") (pintype "input"))
      (node (ref "JP14") (pin "1") (pinfunction "1_1") (pintype "passive"))
    )
    (net (code "98") (name "Net-(IC4A-OUT)") (class "Default")
      (node (ref "IC4") (pin "2") (pinfunction "OUT_2") (pintype "open_collector"))
      (node (ref "R61") (pin "1") (pinfunction "1_1") (pintype "passive"))
      (node (ref "R62") (pin "2") (pinfunction "2_2") (pintype "passive"))
    )
    (net (code "99") (name "Net-(IC4B-+IN)") (class "Default")
      (node (ref "IC4") (pin "7") (pinfunction "+IN_7") (pintype "input"))
      (node (ref "R63") (pin "2") (pinfunction "2_2") (pintype "passive"))
      (node (ref "R64") (pin "2") (pinfunction "2_2") (pintype "passive"))
    )
    (net (code "100") (name "Net-(IC4B--IN)") (class "Default")
      (node (ref "IC4") (pin "6") (pinfunction "-IN_6") (pintype "input"))
      (node (ref "JP15") (pin "1") (pinfunction "1_1") (pintype "passive"))
    )
    (net (code "101") (name "Net-(IC4B-OUT)") (class "Default")
      (node (ref "IC4") (pin "1") (pinfunction "OUT_1") (pintype "open_collector"))
      (node (ref "R65") (pin "1") (pinfunction "1_1") (pintype "passive"))
      (node (ref "R66") (pin "2") (pinfunction "2_2") (pintype "passive"))
    )
    (net (code "102") (name "Net-(IC4C-+IN)") (class "Default")
      (node (ref "IC4") (pin "9") (pinfunction "+IN_9") (pintype "input"))
      (node (ref "R67") (pin "2") (pinfunction "2_2") (pintype "passive"))
      (node (ref "R68") (pin "2") (pinfunction "2_2") (pintype "passive"))
    )
    (net (code "103") (name "Net-(IC4C--IN)") (class "Default")
      (node (ref "IC4") (pin "8") (pinfunction "-IN_8") (pintype "input"))
      (node (ref "JP16") (pin "1") (pinfunction "1_1") (pintype "passive"))
    )
    (net (code "104") (name "Net-(IC4C-OUT)") (class "Default")
      (node (ref "IC4") (pin "14") (pinfunction "OUT_14") (pintype "open_collector"))
      (node (ref "R69") (pin "1") (pinfunction "1_1") (pintype "passive"))
      (node (ref "R70") (pin "2") (pinfunction "2_2") (pintype "passive"))
    )
    (net (code "105") (name "Net-(IC4D-+IN)") (class "Default")
      (node (ref "IC4") (pin "11") (pinfunction "+IN_11") (pintype "input"))
      (node (ref "R71") (pin "2") (pinfunction "2_2") (pintype "passive"))
      (node (ref "R72") (pin "2") (pinfunction "2_2") (pintype "passive"))
    )
    (net (code "106") (name "Net-(IC4D--IN)") (class "Default")
      (node (ref "IC4") (pin "10") (pinfunction "-IN_10") (pintype "input"))
      (node (ref "JP17") (pin "1") (pinfunction "1_1") (pintype "passive"))
    )
    (net (code "107") (name "Net-(IC4D-OUT)") (class "Default")
      (node (ref "IC4") (pin "13") (pinfunction "OUT_13") (pintype "open_collector"))
      (node (ref "R73") (pin "1") (pinfunction "1_1") (pintype "passive"))
      (node (ref "R74") (pin "2") (pinfunction "2_2") (pintype "passive"))
    )
    (net (code "108") (name "Net-(IC5A-+IN)") (class "Default")
      (node (ref "IC5") (pin "5") (pinfunction "+IN_5") (pintype "input"))
      (node (ref "R75") (pin "2") (pinfunction "2_2") (pintype "passive"))
      (node (ref "R76") (pin "2") (pinfunction "2_2") (pintype "passive"))
    )
    (net (code "109") (name "Net-(IC5A--IN)") (class "Default")
      (node (ref "IC5") (pin "4") (pinfunction "-IN_4") (pintype "input"))
      (node (ref "JP18") (pin "1") (pinfunction "1_1") (pintype "passive"))
    )
    (net (code "110") (name "Net-(IC5A-OUT)") (class "Default")
      (node (ref "IC5") (pin "2") (pinfunction "OUT_2") (pintype "open_collector"))
      (node (ref "R77") (pin "1") (pinfunction "1_1") (pintype "passive"))
      (node (ref "R78") (pin "2") (pinfunction "2_2") (pintype "passive"))
    )
    (net (code "111") (name "Net-(IC5B-+IN)") (class "Default")
      (node (ref "IC5") (pin "7") (pinfunction "+IN_7") (pintype "input"))
      (node (ref "R79") (pin "2") (pinfunction "2_2") (pintype "passive"))
      (node (ref "R80") (pin "2") (pinfunction "2_2") (pintype "passive"))
    )
    (net (code "112") (name "Net-(IC5B--IN)") (class "Default")
      (node (ref "IC5") (pin "6") (pinfunction "-IN_6") (pintype "input"))
      (node (ref "JP19") (pin "1") (pinfunction "1_1") (pintype "passive"))
    )
    (net (code "113") (name "Net-(IC5B-OUT)") (class "Default")
      (node (ref "IC5") (pin "1") (pinfunction "OUT_1") (pintype "open_collector"))
      (node (ref "R81") (pin "1") (pinfunction "1_1") (pintype "passive"))
      (node (ref "R82") (pin "2") (pinfunction "2_2") (pintype "passive"))
    )
    (net (code "114") (name "Net-(IC5C-+IN)") (class "Default")
      (node (ref "IC5") (pin "9") (pinfunction "+IN_9") (pintype "input"))
      (node (ref "R83") (pin "2") (pinfunction "2_2") (pintype "passive"))
      (node (ref "R84") (pin "2") (pinfunction "2_2") (pintype "passive"))
    )
    (net (code "115") (name "Net-(IC5C--IN)") (class "Default")
      (node (ref "IC5") (pin "8") (pinfunction "-IN_8") (pintype "input"))
      (node (ref "JP20") (pin "1") (pinfunction "1_1") (pintype "passive"))
    )
    (net (code "116") (name "Net-(IC5C-OUT)") (class "Default")
      (node (ref "IC5") (pin "14") (pinfunction "OUT_14") (pintype "open_collector"))
      (node (ref "R85") (pin "1") (pinfunction "1_1") (pintype "passive"))
      (node (ref "R86") (pin "2") (pinfunction "2_2") (pintype "passive"))
    )
    (net (code "117") (name "Net-(IC5D-+IN)") (class "Default")
      (node (ref "IC5") (pin "11") (pinfunction "+IN_11") (pintype "input"))
      (node (ref "R87") (pin "2") (pinfunction "2_2") (pintype "passive"))
      (node (ref "R88") (pin "2") (pinfunction "2_2") (pintype "passive"))
    )
    (net (code "118") (name "Net-(IC5D--IN)") (class "Default")
      (node (ref "IC5") (pin "10") (pinfunction "-IN_10") (pintype "input"))
      (node (ref "JP21") (pin "1") (pinfunction "1_1") (pintype "passive"))
    )
    (net (code "119") (name "Net-(IC5D-OUT)") (class "Default")
      (node (ref "IC5") (pin "13") (pinfunction "OUT_13") (pintype "open_collector"))
      (node (ref "R89") (pin "1") (pinfunction "1_1") (pintype "passive"))
      (node (ref "R90") (pin "2") (pinfunction "2_2") (pintype "passive"))
    )
    (net (code "120") (name "Net-(IC6A-+IN)") (class "Default")
      (node (ref "IC6") (pin "5") (pinfunction "+IN_5") (pintype "input"))
      (node (ref "R91") (pin "2") (pinfunction "2_2") (pintype "passive"))
      (node (ref "R92") (pin "2") (pinfunction "2_2") (pintype "passive"))
    )
    (net (code "121") (name "Net-(IC6A--IN)") (class "Default")
      (node (ref "IC6") (pin "4") (pinfunction "-IN_4") (pintype "input"))
      (node (ref "JP22") (pin "1") (pinfunction "1_1") (pintype "passive"))
    )
    (net (code "122") (name "Net-(IC6A-OUT)") (class "Default")
      (node (ref "IC6") (pin "2") (pinfunction "OUT_2") (pintype "open_collector"))
      (node (ref "R93") (pin "1") (pinfunction "1_1") (pintype "passive"))
      (node (ref "R94") (pin "2") (pinfunction "2_2") (pintype "passive"))
    )
    (net (code "123") (name "Net-(IC6B-+IN)") (class "Default")
      (node (ref "IC6") (pin "7") (pinfunction "+IN_7") (pintype "input"))
      (node (ref "R95") (pin "2") (pinfunction "2_2") (pintype "passive"))
      (node (ref "R96") (pin "2") (pinfunction "2_2") (pintype "passive"))
    )
    (net (code "124") (name "Net-(IC6B--IN)") (class "Default")
      (node (ref "IC6") (pin "6") (pinfunction "-IN_6") (pintype "input"))
      (node (ref "JP23") (pin "1") (pinfunction "1_1") (pintype "passive"))
    )
    (net (code "125") (name "Net-(IC6B-OUT)") (class "Default")
      (node (ref "IC6") (pin "1") (pinfunction "OUT_1") (pintype "open_collector"))
      (node (ref "R97") (pin "1") (pinfunction "1_1") (pintype "passive"))
      (node (ref "R98") (pin "2") (pinfunction "2_2") (pintype "passive"))
    )
    (net (code "126") (name "Net-(IC6C-+IN)") (class "Default")
      (node (ref "IC6") (pin "9") (pinfunction "+IN_9") (pintype "input"))
      (node (ref "R100") (pin "2") (pinfunction "2_2") (pintype "passive"))
      (node (ref "R99") (pin "2") (pinfunction "2_2") (pintype "passive"))
    )
    (net (code "127") (name "Net-(IC6C--IN)") (class "Default")
      (node (ref "IC6") (pin "8") (pinfunction "-IN_8") (pintype "input"))
      (node (ref "JP24") (pin "1") (pinfunction "1_1") (pintype "passive"))
    )
    (net (code "128") (name "Net-(IC6C-OUT)") (class "Default")
      (node (ref "IC6") (pin "14") (pinfunction "OUT_14") (pintype "open_collector"))
      (node (ref "R101") (pin "1") (pinfunction "1_1") (pintype "passive"))
      (node (ref "R102") (pin "2") (pinfunction "2_2") (pintype "passive"))
    )
    (net (code "129") (name "Net-(IC6D-+IN)") (class "Default")
      (node (ref "IC6") (pin "11") (pinfunction "+IN_11") (pintype "input"))
      (node (ref "R103") (pin "2") (pinfunction "2_2") (pintype "passive"))
      (node (ref "R104") (pin "2") (pinfunction "2_2") (pintype "passive"))
    )
    (net (code "130") (name "Net-(IC6D--IN)") (class "Default")
      (node (ref "IC6") (pin "10") (pinfunction "-IN_10") (pintype "input"))
      (node (ref "JP25") (pin "1") (pinfunction "1_1") (pintype "passive"))
    )
    (net (code "131") (name "Net-(IC6D-OUT)") (class "Default")
      (node (ref "IC6") (pin "13") (pinfunction "OUT_13") (pintype "open_collector"))
      (node (ref "R105") (pin "1") (pinfunction "1_1") (pintype "passive"))
      (node (ref "R106") (pin "2") (pinfunction "2_2") (pintype "passive"))
    )
    (net (code "132") (name "Net-(IC7A-+IN)") (class "Default")
      (node (ref "IC7") (pin "5") (pinfunction "+IN_5") (pintype "input"))
      (node (ref "R107") (pin "2") (pinfunction "2_2") (pintype "passive"))
      (node (ref "R108") (pin "2") (pinfunction "2_2") (pintype "passive"))
    )
    (net (code "133") (name "Net-(IC7A--IN)") (class "Default")
      (node (ref "IC7") (pin "4") (pinfunction "-IN_4") (pintype "input"))
      (node (ref "JP26") (pin "1") (pinfunction "1_1") (pintype "passive"))
    )
    (net (code "134") (name "Net-(IC7A-OUT)") (class "Default")
      (node (ref "IC7") (pin "2") (pinfunction "OUT_2") (pintype "open_collector"))
      (node (ref "R109") (pin "1") (pinfunction "1_1") (pintype "passive"))
      (node (ref "R110") (pin "2") (pinfunction "2_2") (pintype "passive"))
    )
    (net (code "135") (name "Net-(IC7B-+IN)") (class "Default")
      (node (ref "IC7") (pin "7") (pinfunction "+IN_7") (pintype "input"))
      (node (ref "R111") (pin "2") (pinfunction "2_2") (pintype "passive"))
      (node (ref "R112") (pin "2") (pinfunction "2_2") (pintype "passive"))
    )
    (net (code "136") (name "Net-(IC7B--IN)") (class "Default")
      (node (ref "IC7") (pin "6") (pinfunction "-IN_6") (pintype "input"))
      (node (ref "JP27") (pin "1") (pinfunction "1_1") (pintype "passive"))
    )
    (net (code "137") (name "Net-(IC7B-OUT)") (class "Default")
      (node (ref "IC7") (pin "1") (pinfunction "OUT_1") (pintype "open_collector"))
      (node (ref "R113") (pin "1") (pinfunction "1_1") (pintype "passive"))
      (node (ref "R114") (pin "2") (pinfunction "2_2") (pintype "passive"))
    )
    (net (code "138") (name "Net-(IC7C-+IN)") (class "Default")
      (node (ref "IC7") (pin "9") (pinfunction "+IN_9") (pintype "input"))
      (node (ref "R115") (pin "2") (pinfunction "2_2") (pintype "passive"))
      (node (ref "R116") (pin "2") (pinfunction "2_2") (pintype "passive"))
    )
    (net (code "139") (name "Net-(IC7C--IN)") (class "Default")
      (node (ref "IC7") (pin "8") (pinfunction "-IN_8") (pintype "input"))
      (node (ref "JP28") (pin "1") (pinfunction "1_1") (pintype "passive"))
    )
    (net (code "140") (name "Net-(IC7C-OUT)") (class "Default")
      (node (ref "IC7") (pin "14") (pinfunction "OUT_14") (pintype "open_collector"))
      (node (ref "R117") (pin "1") (pinfunction "1_1") (pintype "passive"))
      (node (ref "R118") (pin "2") (pinfunction "2_2") (pintype "passive"))
    )
    (net (code "141") (name "Net-(IC7D-+IN)") (class "Default")
      (node (ref "IC7") (pin "11") (pinfunction "+IN_11") (pintype "input"))
      (node (ref "R119") (pin "2") (pinfunction "2_2") (pintype "passive"))
      (node (ref "R120") (pin "2") (pinfunction "2_2") (pintype "passive"))
    )
    (net (code "142") (name "Net-(IC7D--IN)") (class "Default")
      (node (ref "IC7") (pin "10") (pinfunction "-IN_10") (pintype "input"))
      (node (ref "JP29") (pin "1") (pinfunction "1_1") (pintype "passive"))
    )
    (net (code "143") (name "Net-(IC7D-OUT)") (class "Default")
      (node (ref "IC7") (pin "13") (pinfunction "OUT_13") (pintype "open_collector"))
      (node (ref "R121") (pin "1") (pinfunction "1_1") (pintype "passive"))
      (node (ref "R122") (pin "2") (pinfunction "2_2") (pintype "passive"))
    )
    (net (code "144") (name "Net-(IC8A-+IN)") (class "Default")
      (node (ref "IC8") (pin "5") (pinfunction "+IN_5") (pintype "input"))
      (node (ref "R123") (pin "2") (pinfunction "2_2") (pintype "passive"))
      (node (ref "R124") (pin "2") (pinfunction "2_2") (pintype "passive"))
    )
    (net (code "145") (name "Net-(IC8A--IN)") (class "Default")
      (node (ref "IC8") (pin "4") (pinfunction "-IN_4") (pintype "input"))
      (node (ref "JP30") (pin "1") (pinfunction "1_1") (pintype "passive"))
    )
    (net (code "146") (name "Net-(IC8A-OUT)") (class "Default")
      (node (ref "IC8") (pin "2") (pinfunction "OUT_2") (pintype "open_collector"))
      (node (ref "R125") (pin "1") (pinfunction "1_1") (pintype "passive"))
      (node (ref "R126") (pin "2") (pinfunction "2_2") (pintype "passive"))
    )
    (net (code "147") (name "Net-(IC8B-+IN)") (class "Default")
      (node (ref "IC8") (pin "7") (pinfunction "+IN_7") (pintype "input"))
      (node (ref "R127") (pin "2") (pinfunction "2_2") (pintype "passive"))
      (node (ref "R128") (pin "2") (pinfunction "2_2") (pintype "passive"))
    )
    (net (code "148") (name "Net-(IC8B--IN)") (class "Default")
      (node (ref "IC8") (pin "6") (pinfunction "-IN_6") (pintype "input"))
      (node (ref "JP31") (pin "1") (pinfunction "1_1") (pintype "passive"))
    )
    (net (code "149") (name "Net-(IC8B-OUT)") (class "Default")
      (node (ref "IC8") (pin "1") (pinfunction "OUT_1") (pintype "open_collector"))
      (node (ref "R129") (pin "1") (pinfunction "1_1") (pintype "passive"))
      (node (ref "R130") (pin "2") (pinfunction "2_2") (pintype "passive"))
    )
    (net (code "150") (name "Net-(IC8C-+IN)") (class "Default")
      (node (ref "IC8") (pin "9") (pinfunction "+IN_9") (pintype "input"))
      (node (ref "R131") (pin "2") (pinfunction "2_2") (pintype "passive"))
      (node (ref "R132") (pin "2") (pinfunction "2_2") (pintype "passive"))
    )
    (net (code "151") (name "Net-(IC8C--IN)") (class "Default")
      (node (ref "IC8") (pin "8") (pinfunction "-IN_8") (pintype "input"))
      (node (ref "JP32") (pin "1") (pinfunction "1_1") (pintype "passive"))
    )
    (net (code "152") (name "Net-(IC8C-OUT)") (class "Default")
      (node (ref "IC8") (pin "14") (pinfunction "OUT_14") (pintype "open_collector"))
      (node (ref "R133") (pin "1") (pinfunction "1_1") (pintype "passive"))
      (node (ref "R134") (pin "2") (pinfunction "2_2") (pintype "passive"))
    )
    (net (code "153") (name "Net-(IC8D-+IN)") (class "Default")
      (node (ref "IC8") (pin "11") (pinfunction "+IN_11") (pintype "input"))
      (node (ref "R135") (pin "2") (pinfunction "2_2") (pintype "passive"))
      (node (ref "R136") (pin "2") (pinfunction "2_2") (pintype "passive"))
    )
    (net (code "154") (name "Net-(IC8D--IN)") (class "Default")
      (node (ref "IC8") (pin "10") (pinfunction "-IN_10") (pintype "input"))
      (node (ref "JP33") (pin "1") (pinfunction "1_1") (pintype "passive"))
    )
    (net (code "155") (name "Net-(IC8D-OUT)") (class "Default")
      (node (ref "IC8") (pin "13") (pinfunction "OUT_13") (pintype "open_collector"))
      (node (ref "R137") (pin "1") (pinfunction "1_1") (pintype "passive"))
      (node (ref "R138") (pin "2") (pinfunction "2_2") (pintype "passive"))
    )
    (net (code "156") (name "Net-(Q2-PadS)") (class "Default")
      (node (ref "Q2") (pin "S") (pinfunction "S_S") (pintype "passive"))
      (node (ref "R10") (pin "2") (pinfunction "2_2") (pintype "passive"))
      (node (ref "R11") (pin "1") (pinfunction "1_1") (pintype "passive"))
    )
    (net (code "157") (name "Net-(Q3-PadS)") (class "Default")
      (node (ref "Q3") (pin "S") (pinfunction "S_S") (pintype "passive"))
      (node (ref "R13") (pin "2") (pinfunction "2_2") (pintype "passive"))
      (node (ref "R14") (pin "1") (pinfunction "1_1") (pintype "passive"))
    )
    (net (code "158") (name "Net-(Q4-PadS)") (class "Default")
      (node (ref "Q4") (pin "S") (pinfunction "S_S") (pintype "passive"))
      (node (ref "R8") (pin "2") (pinfunction "2_2") (pintype "passive"))
      (node (ref "R9") (pin "1") (pinfunction "1_1") (pintype "passive"))
    )
    (net (code "159") (name "Net-(Q5-PadS)") (class "Default")
      (node (ref "Q5") (pin "S") (pinfunction "S_S") (pintype "passive"))
      (node (ref "R141") (pin "2") (pinfunction "2_2") (pintype "passive"))
      (node (ref "R142") (pin "1") (pinfunction "1_1") (pintype "passive"))
    )
    (net (code "160") (name "Net-(Q6-PadS)") (class "Default")
      (node (ref "Q6") (pin "S") (pinfunction "S_S") (pintype "passive"))
      (node (ref "R145") (pin "2") (pinfunction "2_2") (pintype "passive"))
      (node (ref "R146") (pin "1") (pinfunction "1_1") (pintype "passive"))
    )
    (net (code "161") (name "Net-(Q7-PadS)") (class "Default")
      (node (ref "Q7") (pin "S") (pinfunction "S_S") (pintype "passive"))
      (node (ref "R149") (pin "2") (pinfunction "2_2") (pintype "passive"))
      (node (ref "R150") (pin "1") (pinfunction "1_1") (pintype "passive"))
    )
    (net (code "162") (name "Net-(Q8-PadS)") (class "Default")
      (node (ref "Q8") (pin "S") (pinfunction "S_S") (pintype "passive"))
      (node (ref "R153") (pin "2") (pinfunction "2_2") (pintype "passive"))
      (node (ref "R154") (pin "1") (pinfunction "1_1") (pintype "passive"))
    )
    (net (code "163") (name "Net-(Q9-PadS)") (class "Default")
      (node (ref "Q9") (pin "S") (pinfunction "S_S") (pintype "passive"))
      (node (ref "R157") (pin "2") (pinfunction "2_2") (pintype "passive"))
      (node (ref "R158") (pin "1") (pinfunction "1_1") (pintype "passive"))
    )
    (net (code "164") (name "Net-(Q10-PadS)") (class "Default")
      (node (ref "Q10") (pin "S") (pinfunction "S_S") (pintype "passive"))
      (node (ref "R161") (pin "2") (pinfunction "2_2") (pintype "passive"))
      (node (ref "R162") (pin "1") (pinfunction "1_1") (pintype "passive"))
    )
    (net (code "165") (name "Net-(Q11-PadS)") (class "Default")
      (node (ref "Q11") (pin "S") (pinfunction "S_S") (pintype "passive"))
      (node (ref "R165") (pin "2") (pinfunction "2_2") (pintype "passive"))
      (node (ref "R166") (pin "1") (pinfunction "1_1") (pintype "passive"))
    )
    (net (code "166") (name "Net-(Q12-PadS)") (class "Default")
      (node (ref "Q12") (pin "S") (pinfunction "S_S") (pintype "passive"))
      (node (ref "R169") (pin "2") (pinfunction "2_2") (pintype "passive"))
      (node (ref "R170") (pin "1") (pinfunction "1_1") (pintype "passive"))
    )
    (net (code "167") (name "Net-(Q13-PadS)") (class "Default")
      (node (ref "Q13") (pin "S") (pinfunction "S_S") (pintype "passive"))
      (node (ref "R173") (pin "2") (pinfunction "2_2") (pintype "passive"))
      (node (ref "R174") (pin "1") (pinfunction "1_1") (pintype "passive"))
    )
    (net (code "168") (name "Net-(Q14-PadS)") (class "Default")
      (node (ref "Q14") (pin "S") (pinfunction "S_S") (pintype "passive"))
      (node (ref "R177") (pin "2") (pinfunction "2_2") (pintype "passive"))
      (node (ref "R178") (pin "1") (pinfunction "1_1") (pintype "passive"))
    )
    (net (code "169") (name "Net-(Q15-PadS)") (class "Default")
      (node (ref "Q15") (pin "S") (pinfunction "S_S") (pintype "passive"))
      (node (ref "R181") (pin "2") (pinfunction "2_2") (pintype "passive"))
      (node (ref "R182") (pin "1") (pinfunction "1_1") (pintype "passive"))
    )
    (net (code "170") (name "Net-(Q16-PadS)") (class "Default")
      (node (ref "Q16") (pin "S") (pinfunction "S_S") (pintype "passive"))
      (node (ref "R185") (pin "2") (pinfunction "2_2") (pintype "passive"))
      (node (ref "R186") (pin "1") (pinfunction "1_1") (pintype "passive"))
    )
    (net (code "171") (name "Net-(Q17-PadS)") (class "Default")
      (node (ref "Q17") (pin "S") (pinfunction "S_S") (pintype "passive"))
      (node (ref "R189") (pin "2") (pinfunction "2_2") (pintype "passive"))
      (node (ref "R190") (pin "1") (pinfunction "1_1") (pintype "passive"))
    )
    (net (code "172") (name "Net-(Q18-PadS)") (class "Default")
      (node (ref "Q18") (pin "S") (pinfunction "S_S") (pintype "passive"))
      (node (ref "R193") (pin "2") (pinfunction "2_2") (pintype "passive"))
      (node (ref "R194") (pin "1") (pinfunction "1_1") (pintype "passive"))
    )
    (net (code "173") (name "Net-(Q19-PadS)") (class "Default")
      (node (ref "Q19") (pin "S") (pinfunction "S_S") (pintype "passive"))
      (node (ref "R197") (pin "2") (pinfunction "2_2") (pintype "passive"))
      (node (ref "R198") (pin "1") (pinfunction "1_1") (pintype "passive"))
    )
    (net (code "174") (name "Net-(Q20-PadS)") (class "Default")
      (node (ref "Q20") (pin "S") (pinfunction "S_S") (pintype "passive"))
      (node (ref "R201") (pin "2") (pinfunction "2_2") (pintype "passive"))
      (node (ref "R202") (pin "1") (pinfunction "1_1") (pintype "passive"))
    )
    (net (code "175") (name "Net-(Q21-PadS)") (class "Default")
      (node (ref "Q21") (pin "S") (pinfunction "S_S") (pintype "passive"))
      (node (ref "R205") (pin "2") (pinfunction "2_2") (pintype "passive"))
      (node (ref "R206") (pin "1") (pinfunction "1_1") (pintype "passive"))
    )
    (net (code "176") (name "Net-(Q22-PadS)") (class "Default")
      (node (ref "Q22") (pin "S") (pinfunction "S_S") (pintype "passive"))
      (node (ref "R209") (pin "2") (pinfunction "2_2") (pintype "passive"))
      (node (ref "R210") (pin "1") (pinfunction "1_1") (pintype "passive"))
    )
    (net (code "177") (name "Net-(Q23-PadS)") (class "Default")
      (node (ref "Q23") (pin "S") (pinfunction "S_S") (pintype "passive"))
      (node (ref "R213") (pin "2") (pinfunction "2_2") (pintype "passive"))
      (node (ref "R214") (pin "1") (pinfunction "1_1") (pintype "passive"))
    )
    (net (code "178") (name "Net-(Q24-PadS)") (class "Default")
      (node (ref "Q24") (pin "S") (pinfunction "S_S") (pintype "passive"))
      (node (ref "R217") (pin "2") (pinfunction "2_2") (pintype "passive"))
      (node (ref "R218") (pin "1") (pinfunction "1_1") (pintype "passive"))
    )
    (net (code "179") (name "Net-(Q25-PadS)") (class "Default")
      (node (ref "Q25") (pin "S") (pinfunction "S_S") (pintype "passive"))
      (node (ref "R221") (pin "2") (pinfunction "2_2") (pintype "passive"))
      (node (ref "R222") (pin "1") (pinfunction "1_1") (pintype "passive"))
    )
    (net (code "180") (name "Net-(Q26-PadS)") (class "Default")
      (node (ref "Q26") (pin "S") (pinfunction "S_S") (pintype "passive"))
      (node (ref "R225") (pin "2") (pinfunction "2_2") (pintype "passive"))
      (node (ref "R226") (pin "1") (pinfunction "1_1") (pintype "passive"))
    )
    (net (code "181") (name "Net-(Q27-PadS)") (class "Default")
      (node (ref "Q27") (pin "S") (pinfunction "S_S") (pintype "passive"))
      (node (ref "R229") (pin "2") (pinfunction "2_2") (pintype "passive"))
      (node (ref "R230") (pin "1") (pinfunction "1_1") (pintype "passive"))
    )
    (net (code "182") (name "Net-(Q28-PadS)") (class "Default")
      (node (ref "Q28") (pin "S") (pinfunction "S_S") (pintype "passive"))
      (node (ref "R233") (pin "2") (pinfunction "2_2") (pintype "passive"))
      (node (ref "R234") (pin "1") (pinfunction "1_1") (pintype "passive"))
    )
    (net (code "183") (name "Net-(Q29-PadS)") (class "Default")
      (node (ref "Q29") (pin "S") (pinfunction "S_S") (pintype "passive"))
      (node (ref "R237") (pin "2") (pinfunction "2_2") (pintype "passive"))
      (node (ref "R238") (pin "1") (pinfunction "1_1") (pintype "passive"))
    )
    (net (code "184") (name "Net-(Q30-PadS)") (class "Default")
      (node (ref "Q30") (pin "S") (pinfunction "S_S") (pintype "passive"))
      (node (ref "R241") (pin "2") (pinfunction "2_2") (pintype "passive"))
      (node (ref "R242") (pin "1") (pinfunction "1_1") (pintype "passive"))
    )
    (net (code "185") (name "Net-(Q31-PadS)") (class "Default")
      (node (ref "Q31") (pin "S") (pinfunction "S_S") (pintype "passive"))
      (node (ref "R245") (pin "2") (pinfunction "2_2") (pintype "passive"))
      (node (ref "R246") (pin "1") (pinfunction "1_1") (pintype "passive"))
    )
    (net (code "186") (name "Net-(Q32-PadS)") (class "Default")
      (node (ref "Q32") (pin "S") (pinfunction "S_S") (pintype "passive"))
      (node (ref "R249") (pin "2") (pinfunction "2_2") (pintype "passive"))
      (node (ref "R250") (pin "1") (pinfunction "1_1") (pintype "passive"))
    )
    (net (code "187") (name "Net-(Q33-PadS)") (class "Default")
      (node (ref "Q33") (pin "S") (pinfunction "S_S") (pintype "passive"))
      (node (ref "R253") (pin "2") (pinfunction "2_2") (pintype "passive"))
      (node (ref "R254") (pin "1") (pinfunction "1_1") (pintype "passive"))
    )
    (net (code "188") (name "Net-(Q34-PadS)") (class "Default")
      (node (ref "Q34") (pin "S") (pinfunction "S_S") (pintype "passive"))
      (node (ref "R257") (pin "2") (pinfunction "2_2") (pintype "passive"))
      (node (ref "R258") (pin "1") (pinfunction "1_1") (pintype "passive"))
    )
    (net (code "189") (name "Net-(Q36-PadS)") (class "Default")
      (node (ref "Q36") (pin "S") (pinfunction "S_S") (pintype "passive"))
      (node (ref "R259") (pin "2") (pinfunction "2_2") (pintype "passive"))
      (node (ref "R260") (pin "1") (pinfunction "1_1") (pintype "passive"))
    )
    (net (code "190") (name "Net-(Q38-PadS)") (class "Default")
      (node (ref "Q38") (pin "S") (pinfunction "S_S") (pintype "passive"))
      (node (ref "R261") (pin "2") (pinfunction "2_2") (pintype "passive"))
      (node (ref "R262") (pin "1") (pinfunction "1_1") (pintype "passive"))
    )
    (net (code "191") (name "Net-(Q40-PadS)") (class "Default")
      (node (ref "Q40") (pin "S") (pinfunction "S_S") (pintype "passive"))
      (node (ref "R263") (pin "2") (pinfunction "2_2") (pintype "passive"))
      (node (ref "R264") (pin "1") (pinfunction "1_1") (pintype "passive"))
    )
    (net (code "192") (name "Net-(Q42-PadS)") (class "Default")
      (node (ref "Q42") (pin "S") (pinfunction "S_S") (pintype "passive"))
      (node (ref "R265") (pin "2") (pinfunction "2_2") (pintype "passive"))
      (node (ref "R266") (pin "1") (pinfunction "1_1") (pintype "passive"))
    )
    (net (code "193") (name "Net-(Q44-PadS)") (class "Default")
      (node (ref "Q44") (pin "S") (pinfunction "S_S") (pintype "passive"))
      (node (ref "R267") (pin "2") (pinfunction "2_2") (pintype "passive"))
      (node (ref "R268") (pin "1") (pinfunction "1_1") (pintype "passive"))
    )
    (net (code "194") (name "Net-(Q46-PadS)") (class "Default")
      (node (ref "Q46") (pin "S") (pinfunction "S_S") (pintype "passive"))
      (node (ref "R269") (pin "2") (pinfunction "2_2") (pintype "passive"))
      (node (ref "R270") (pin "1") (pinfunction "1_1") (pintype "passive"))
    )
    (net (code "195") (name "Net-(Q48-PadS)") (class "Default")
      (node (ref "Q48") (pin "S") (pinfunction "S_S") (pintype "passive"))
      (node (ref "R271") (pin "2") (pinfunction "2_2") (pintype "passive"))
      (node (ref "R272") (pin "1") (pinfunction "1_1") (pintype "passive"))
    )
    (net (code "196") (name "Net-(Q50-PadS)") (class "Default")
      (node (ref "Q50") (pin "S") (pinfunction "S_S") (pintype "passive"))
      (node (ref "R273") (pin "2") (pinfunction "2_2") (pintype "passive"))
      (node (ref "R274") (pin "1") (pinfunction "1_1") (pintype "passive"))
    )
    (net (code "197") (name "Net-(Q52-PadS)") (class "Default")
      (node (ref "Q52") (pin "S") (pinfunction "S_S") (pintype "passive"))
      (node (ref "R275") (pin "2") (pinfunction "2_2") (pintype "passive"))
      (node (ref "R276") (pin "1") (pinfunction "1_1") (pintype "passive"))
    )
    (net (code "198") (name "Net-(Q54-PadS)") (class "Default")
      (node (ref "Q54") (pin "S") (pinfunction "S_S") (pintype "passive"))
      (node (ref "R277") (pin "2") (pinfunction "2_2") (pintype "passive"))
      (node (ref "R278") (pin "1") (pinfunction "1_1") (pintype "passive"))
    )
    (net (code "199") (name "Net-(Q56-PadS)") (class "Default")
      (node (ref "Q56") (pin "S") (pinfunction "S_S") (pintype "passive"))
      (node (ref "R279") (pin "2") (pinfunction "2_2") (pintype "passive"))
      (node (ref "R280") (pin "1") (pinfunction "1_1") (pintype "passive"))
    )
    (net (code "200") (name "Net-(Q58-PadS)") (class "Default")
      (node (ref "Q58") (pin "S") (pinfunction "S_S") (pintype "passive"))
      (node (ref "R281") (pin "2") (pinfunction "2_2") (pintype "passive"))
      (node (ref "R282") (pin "1") (pinfunction "1_1") (pintype "passive"))
    )
    (net (code "201") (name "Net-(Q60-PadS)") (class "Default")
      (node (ref "Q60") (pin "S") (pinfunction "S_S") (pintype "passive"))
      (node (ref "R283") (pin "2") (pinfunction "2_2") (pintype "passive"))
      (node (ref "R284") (pin "1") (pinfunction "1_1") (pintype "passive"))
    )
    (net (code "202") (name "Net-(Q62-PadS)") (class "Default")
      (node (ref "Q62") (pin "S") (pinfunction "S_S") (pintype "passive"))
      (node (ref "R285") (pin "2") (pinfunction "2_2") (pintype "passive"))
      (node (ref "R286") (pin "1") (pinfunction "1_1") (pintype "passive"))
    )
    (net (code "203") (name "Net-(Q64-PadS)") (class "Default")
      (node (ref "Q64") (pin "S") (pinfunction "S_S") (pintype "passive"))
      (node (ref "R287") (pin "2") (pinfunction "2_2") (pintype "passive"))
      (node (ref "R288") (pin "1") (pinfunction "1_1") (pintype "passive"))
    )
    (net (code "204") (name "Net-(Q66-PadS)") (class "Default")
      (node (ref "Q66") (pin "S") (pinfunction "S_S") (pintype "passive"))
      (node (ref "R289") (pin "2") (pinfunction "2_2") (pintype "passive"))
      (node (ref "R290") (pin "1") (pinfunction "1_1") (pintype "passive"))
    )
    (net (code "205") (name "Net-(Q68-PadS)") (class "Default")
      (node (ref "Q68") (pin "S") (pinfunction "S_S") (pintype "passive"))
      (node (ref "R291") (pin "2") (pinfunction "2_2") (pintype "passive"))
      (node (ref "R292") (pin "1") (pinfunction "1_1") (pintype "passive"))
    )
    (net (code "206") (name "Net-(Q70-PadS)") (class "Default")
      (node (ref "Q70") (pin "S") (pinfunction "S_S") (pintype "passive"))
      (node (ref "R293") (pin "2") (pinfunction "2_2") (pintype "passive"))
      (node (ref "R294") (pin "1") (pinfunction "1_1") (pintype "passive"))
    )
    (net (code "207") (name "Net-(Q72-PadS)") (class "Default")
      (node (ref "Q72") (pin "S") (pinfunction "S_S") (pintype "passive"))
      (node (ref "R295") (pin "2") (pinfunction "2_2") (pintype "passive"))
      (node (ref "R296") (pin "1") (pinfunction "1_1") (pintype "passive"))
    )
    (net (code "208") (name "Net-(Q74-PadS)") (class "Default")
      (node (ref "Q74") (pin "S") (pinfunction "S_S") (pintype "passive"))
      (node (ref "R297") (pin "2") (pinfunction "2_2") (pintype "passive"))
      (node (ref "R298") (pin "1") (pinfunction "1_1") (pintype "passive"))
    )
    (net (code "209") (name "Net-(Q76-PadS)") (class "Default")
      (node (ref "Q76") (pin "S") (pinfunction "S_S") (pintype "passive"))
      (node (ref "R299") (pin "2") (pinfunction "2_2") (pintype "passive"))
      (node (ref "R300") (pin "1") (pinfunction "1_1") (pintype "passive"))
    )
    (net (code "210") (name "Net-(Q78-PadS)") (class "Default")
      (node (ref "Q78") (pin "S") (pinfunction "S_S") (pintype "passive"))
      (node (ref "R301") (pin "2") (pinfunction "2_2") (pintype "passive"))
      (node (ref "R302") (pin "1") (pinfunction "1_1") (pintype "passive"))
    )
    (net (code "211") (name "Net-(Q80-PadS)") (class "Default")
      (node (ref "Q80") (pin "S") (pinfunction "S_S") (pintype "passive"))
      (node (ref "R303") (pin "2") (pinfunction "2_2") (pintype "passive"))
      (node (ref "R304") (pin "1") (pinfunction "1_1") (pintype "passive"))
    )
    (net (code "212") (name "Net-(Q82-PadS)") (class "Default")
      (node (ref "Q82") (pin "S") (pinfunction "S_S") (pintype "passive"))
      (node (ref "R305") (pin "2") (pinfunction "2_2") (pintype "passive"))
      (node (ref "R306") (pin "1") (pinfunction "1_1") (pintype "passive"))
    )
    (net (code "213") (name "Net-(Q84-PadS)") (class "Default")
      (node (ref "Q84") (pin "S") (pinfunction "S_S") (pintype "passive"))
      (node (ref "R307") (pin "2") (pinfunction "2_2") (pintype "passive"))
      (node (ref "R308") (pin "1") (pinfunction "1_1") (pintype "passive"))
    )
    (net (code "214") (name "Net-(Q86-PadS)") (class "Default")
      (node (ref "Q86") (pin "S") (pinfunction "S_S") (pintype "passive"))
      (node (ref "R309") (pin "2") (pinfunction "2_2") (pintype "passive"))
      (node (ref "R310") (pin "1") (pinfunction "1_1") (pintype "passive"))
    )
    (net (code "215") (name "Net-(Q88-PadS)") (class "Default")
      (node (ref "Q88") (pin "S") (pinfunction "S_S") (pintype "passive"))
      (node (ref "R311") (pin "2") (pinfunction "2_2") (pintype "passive"))
      (node (ref "R312") (pin "1") (pinfunction "1_1") (pintype "passive"))
    )
    (net (code "216") (name "Net-(Q90-PadS)") (class "Default")
      (node (ref "Q90") (pin "S") (pinfunction "S_S") (pintype "passive"))
      (node (ref "R313") (pin "2") (pinfunction "2_2") (pintype "passive"))
      (node (ref "R314") (pin "1") (pinfunction "1_1") (pintype "passive"))
    )
    (net (code "217") (name "Net-(Q92-PadS)") (class "Default")
      (node (ref "Q92") (pin "S") (pinfunction "S_S") (pintype "passive"))
      (node (ref "R315") (pin "2") (pinfunction "2_2") (pintype "passive"))
      (node (ref "R316") (pin "1") (pinfunction "1_1") (pintype "passive"))
    )
    (net (code "218") (name "Net-(Q94-PadS)") (class "Default")
      (node (ref "Q94") (pin "S") (pinfunction "S_S") (pintype "passive"))
      (node (ref "R317") (pin "2") (pinfunction "2_2") (pintype "passive"))
      (node (ref "R318") (pin "1") (pinfunction "1_1") (pintype "passive"))
    )
    (net (code "219") (name "Net-(Q96-PadS)") (class "Default")
      (node (ref "Q96") (pin "S") (pinfunction "S_S") (pintype "passive"))
      (node (ref "R319") (pin "2") (pinfunction "2_2") (pintype "passive"))
      (node (ref "R320") (pin "1") (pinfunction "1_1") (pintype "passive"))
    )
    (net (code "220") (name "Net-(THR-A)") (class "Default")
      (node (ref "R321") (pin "2") (pinfunction "2_2") (pintype "passive"))
      (node (ref "THR") (pin "3") (pinfunction "A_3") (pintype "passive"))
    )
    (net (code "221") (name "Net-(THR-E)") (class "Default")
      (node (ref "R323") (pin "1") (pinfunction "1_1") (pintype "passive"))
      (node (ref "THR") (pin "1") (pinfunction "E_1") (pintype "passive"))
    )
    (net (code "222") (name "P1") (class "Default")
      (node (ref "Q15") (pin "D") (pinfunction "D_D") (pintype "passive"))
      (node (ref "Q57") (pin "D") (pinfunction "D_D") (pintype "passive"))
      (node (ref "Q58") (pin "D") (pinfunction "D_D") (pintype "passive"))
      (node (ref "R60") (pin "1") (pinfunction "1_1") (pintype "passive"))
      (node (ref "SIDE1") (pin "30") (pinfunction "30_30") (pintype "passive"))
    )
    (net (code "223") (name "P2") (class "Default")
      (node (ref "Q29") (pin "D") (pinfunction "D_D") (pintype "passive"))
      (node (ref "Q85") (pin "D") (pinfunction "D_D") (pintype "passive"))
      (node (ref "Q86") (pin "D") (pinfunction "D_D") (pintype "passive"))
      (node (ref "R116") (pin "1") (pinfunction "1_1") (pintype "passive"))
      (node (ref "SIDE2") (pin "24") (pinfunction "24_24") (pintype "passive"))
    )
    (net (code "224") (name "PDA1") (class "Default")
      (node (ref "D1") (pin "C") (pinfunction "C_C") (pintype "passive"))
      (node (ref "D136") (pin "C") (pinfunction "C_C") (pintype "passive"))
      (node (ref "SV5") (pin "2") (pinfunction "2_2") (pintype "passive"))
    )
    (net (code "225") (name "PDB1") (class "Default")
      (node (ref "D135") (pin "C") (pinfunction "C_C") (pintype "passive"))
      (node (ref "D4") (pin "C") (pinfunction "C_C") (pintype "passive"))
      (node (ref "SV5") (pin "4") (pinfunction "4_4") (pintype "passive"))
    )
    (net (code "226") (name "PDC1") (class "Default")
      (node (ref "D134") (pin "C") (pinfunction "C_C") (pintype "passive"))
      (node (ref "D5") (pin "C") (pinfunction "C_C") (pintype "passive"))
      (node (ref "SV5") (pin "6") (pinfunction "6_6") (pintype "passive"))
    )
    (net (code "227") (name "PDD1") (class "Default")
      (node (ref "D133") (pin "C") (pinfunction "C_C") (pintype "passive"))
      (node (ref "D8") (pin "C") (pinfunction "C_C") (pintype "passive"))
      (node (ref "SV5") (pin "8") (pinfunction "8_8") (pintype "passive"))
    )
    (net (code "228") (name "PDD2") (class "Default")
      (node (ref "D151") (pin "C") (pinfunction "C_C") (pintype "passive"))
      (node (ref "D52") (pin "C") (pinfunction "C_C") (pintype "passive"))
      (node (ref "SV6") (pin "4") (pinfunction "4_4") (pintype "passive"))
    )
    (net (code "229") (name "PDE1") (class "Default")
      (node (ref "D132") (pin "C") (pinfunction "C_C") (pintype "passive"))
      (node (ref "D7") (pin "C") (pinfunction "C_C") (pintype "passive"))
      (node (ref "SV5") (pin "1") (pinfunction "1_1") (pintype "passive"))
    )
    (net (code "230") (name "PDE2") (class "Default")
      (node (ref "D150") (pin "C") (pinfunction "C_C") (pintype "passive"))
      (node (ref "D53") (pin "C") (pinfunction "C_C") (pintype "passive"))
      (node (ref "SV6") (pin "6") (pinfunction "6_6") (pintype "passive"))
    )
    (net (code "231") (name "PDF1") (class "Default")
      (node (ref "D131") (pin "C") (pinfunction "C_C") (pintype "passive"))
      (node (ref "D40") (pin "C") (pinfunction "C_C") (pintype "passive"))
      (node (ref "SV5") (pin "3") (pinfunction "3_3") (pintype "passive"))
    )
    (net (code "232") (name "PDF2") (class "Default")
      (node (ref "D149") (pin "C") (pinfunction "C_C") (pintype "passive"))
      (node (ref "D54") (pin "C") (pinfunction "C_C") (pintype "passive"))
      (node (ref "SV6") (pin "8") (pinfunction "8_8") (pintype "passive"))
    )
    (net (code "233") (name "PDH1") (class "Default")
      (node (ref "D130") (pin "C") (pinfunction "C_C") (pintype "passive"))
      (node (ref "D41") (pin "C") (pinfunction "C_C") (pintype "passive"))
      (node (ref "SV5") (pin "5") (pinfunction "5_5") (pintype "passive"))
    )
    (net (code "234") (name "PDH2") (class "Default")
      (node (ref "D148") (pin "C") (pinfunction "C_C") (pintype "passive"))
      (node (ref "D55") (pin "C") (pinfunction "C_C") (pintype "passive"))
      (node (ref "SV6") (pin "1") (pinfunction "1_1") (pintype "passive"))
    )
    (net (code "235") (name "PDJ1") (class "Default")
      (node (ref "D129") (pin "C") (pinfunction "C_C") (pintype "passive"))
      (node (ref "D42") (pin "C") (pinfunction "C_C") (pintype "passive"))
      (node (ref "SV5") (pin "7") (pinfunction "7_7") (pintype "passive"))
    )
    (net (code "236") (name "PDJ2") (class "Default")
      (node (ref "D147") (pin "C") (pinfunction "C_C") (pintype "passive"))
      (node (ref "D56") (pin "C") (pinfunction "C_C") (pintype "passive"))
      (node (ref "SV6") (pin "3") (pinfunction "3_3") (pintype "passive"))
    )
    (net (code "237") (name "PDK1") (class "Default")
      (node (ref "D144") (pin "C") (pinfunction "C_C") (pintype "passive"))
      (node (ref "D43") (pin "C") (pinfunction "C_C") (pintype "passive"))
      (node (ref "SV5") (pin "10") (pinfunction "10_10") (pintype "passive"))
    )
    (net (code "238") (name "PDK2") (class "Default")
      (node (ref "D146") (pin "C") (pinfunction "C_C") (pintype "passive"))
      (node (ref "D57") (pin "C") (pinfunction "C_C") (pintype "passive"))
      (node (ref "SV6") (pin "5") (pinfunction "5_5") (pintype "passive"))
    )
    (net (code "239") (name "PDL1") (class "Default")
      (node (ref "D143") (pin "C") (pinfunction "C_C") (pintype "passive"))
      (node (ref "D44") (pin "C") (pinfunction "C_C") (pintype "passive"))
      (node (ref "SV5") (pin "12") (pinfunction "12_12") (pintype "passive"))
    )
    (net (code "240") (name "PDL2") (class "Default")
      (node (ref "D145") (pin "C") (pinfunction "C_C") (pintype "passive"))
      (node (ref "D58") (pin "C") (pinfunction "C_C") (pintype "passive"))
      (node (ref "SV6") (pin "7") (pinfunction "7_7") (pintype "passive"))
    )
    (net (code "241") (name "PDM1") (class "Default")
      (node (ref "D142") (pin "C") (pinfunction "C_C") (pintype "passive"))
      (node (ref "D45") (pin "C") (pinfunction "C_C") (pintype "passive"))
      (node (ref "SV5") (pin "14") (pinfunction "14_14") (pintype "passive"))
    )
    (net (code "242") (name "PDM2") (class "Default")
      (node (ref "D160") (pin "C") (pinfunction "C_C") (pintype "passive"))
      (node (ref "D59") (pin "C") (pinfunction "C_C") (pintype "passive"))
      (node (ref "SV6") (pin "10") (pinfunction "10_10") (pintype "passive"))
    )
    (net (code "243") (name "PDN1") (class "Default")
      (node (ref "D141") (pin "C") (pinfunction "C_C") (pintype "passive"))
      (node (ref "D46") (pin "C") (pinfunction "C_C") (pintype "passive"))
      (node (ref "SV5") (pin "16") (pinfunction "16_16") (pintype "passive"))
    )
    (net (code "244") (name "PDN2") (class "Default")
      (node (ref "D159") (pin "C") (pinfunction "C_C") (pintype "passive"))
      (node (ref "D60") (pin "C") (pinfunction "C_C") (pintype "passive"))
      (node (ref "SV6") (pin "12") (pinfunction "12_12") (pintype "passive"))
    )
    (net (code "245") (name "PDP1") (class "Default")
      (node (ref "D140") (pin "C") (pinfunction "C_C") (pintype "passive"))
      (node (ref "D47") (pin "C") (pinfunction "C_C") (pintype "passive"))
      (node (ref "SV5") (pin "9") (pinfunction "9_9") (pintype "passive"))
    )
    (net (code "246") (name "PDP2") (class "Default")
      (node (ref "D158") (pin "C") (pinfunction "C_C") (pintype "passive"))
      (node (ref "D61") (pin "C") (pinfunction "C_C") (pintype "passive"))
      (node (ref "SV6") (pin "14") (pinfunction "14_14") (pintype "passive"))
    )
    (net (code "247") (name "PDR1") (class "Default")
      (node (ref "D139") (pin "C") (pinfunction "C_C") (pintype "passive"))
      (node (ref "D48") (pin "C") (pinfunction "C_C") (pintype "passive"))
      (node (ref "SV5") (pin "11") (pinfunction "11_11") (pintype "passive"))
    )
    (net (code "248") (name "PDR2") (class "Default")
      (node (ref "D157") (pin "C") (pinfunction "C_C") (pintype "passive"))
      (node (ref "D62") (pin "C") (pinfunction "C_C") (pintype "passive"))
      (node (ref "SV6") (pin "16") (pinfunction "16_16") (pintype "passive"))
    )
    (net (code "249") (name "PDS1") (class "Default")
      (node (ref "D138") (pin "C") (pinfunction "C_C") (pintype "passive"))
      (node (ref "D49") (pin "C") (pinfunction "C_C") (pintype "passive"))
      (node (ref "SV5") (pin "13") (pinfunction "13_13") (pintype "passive"))
    )
    (net (code "250") (name "PDS2") (class "Default")
      (node (ref "D156") (pin "C") (pinfunction "C_C") (pintype "passive"))
      (node (ref "D63") (pin "C") (pinfunction "C_C") (pintype "passive"))
      (node (ref "SV6") (pin "9") (pinfunction "9_9") (pintype "passive"))
    )
    (net (code "251") (name "PDT2") (class "Default")
      (node (ref "D155") (pin "C") (pinfunction "C_C") (pintype "passive"))
      (node (ref "D64") (pin "C") (pinfunction "C_C") (pintype "passive"))
      (node (ref "SV6") (pin "11") (pinfunction "11_11") (pintype "passive"))
    )
    (net (code "252") (name "PDU1") (class "Default")
      (node (ref "D137") (pin "C") (pinfunction "C_C") (pintype "passive"))
      (node (ref "D50") (pin "C") (pinfunction "C_C") (pintype "passive"))
      (node (ref "SV5") (pin "15") (pinfunction "15_15") (pintype "passive"))
    )
    (net (code "253") (name "PDU2") (class "Default")
      (node (ref "D154") (pin "C") (pinfunction "C_C") (pintype "passive"))
      (node (ref "D65") (pin "C") (pinfunction "C_C") (pintype "passive"))
      (node (ref "SV6") (pin "13") (pinfunction "13_13") (pintype "passive"))
    )
    (net (code "254") (name "PDV1") (class "Default")
      (node (ref "D152") (pin "C") (pinfunction "C_C") (pintype "passive"))
      (node (ref "D51") (pin "C") (pinfunction "C_C") (pintype "passive"))
      (node (ref "SV6") (pin "2") (pinfunction "2_2") (pintype "passive"))
    )
    (net (code "255") (name "PDV2") (class "Default")
      (node (ref "D153") (pin "C") (pinfunction "C_C") (pintype "passive"))
      (node (ref "D66") (pin "C") (pinfunction "C_C") (pintype "passive"))
      (node (ref "SV6") (pin "15") (pinfunction "15_15") (pintype "passive"))
    )
    (net (code "256") (name "PGA1") (class "Default")
      (node (ref "D3") (pin "C") (pinfunction "C_C") (pintype "passive"))
      (node (ref "Q1") (pin "G") (pinfunction "G_G") (pintype "passive"))
      (node (ref "SV3") (pin "2") (pinfunction "2_2") (pintype "passive"))
    )
    (net (code "257") (name "PGB1") (class "Default")
      (node (ref "D67") (pin "C") (pinfunction "C_C") (pintype "passive"))
      (node (ref "Q35") (pin "G") (pinfunction "G_G") (pintype "passive"))
      (node (ref "SV3") (pin "4") (pinfunction "4_4") (pintype "passive"))
    )
    (net (code "258") (name "PGC1") (class "Default")
      (node (ref "D69") (pin "C") (pinfunction "C_C") (pintype "passive"))
      (node (ref "Q37") (pin "G") (pinfunction "G_G") (pintype "passive"))
      (node (ref "SV3") (pin "6") (pinfunction "6_6") (pintype "passive"))
    )
    (net (code "259") (name "PGD1") (class "Default")
      (node (ref "D71") (pin "C") (pinfunction "C_C") (pintype "passive"))
      (node (ref "Q39") (pin "G") (pinfunction "G_G") (pintype "passive"))
      (node (ref "SV3") (pin "8") (pinfunction "8_8") (pintype "passive"))
    )
    (net (code "260") (name "PGD2") (class "Default")
      (node (ref "D99") (pin "C") (pinfunction "C_C") (pintype "passive"))
      (node (ref "Q67") (pin "G") (pinfunction "G_G") (pintype "passive"))
      (node (ref "SV1") (pin "4") (pinfunction "4_4") (pintype "passive"))
    )
    (net (code "261") (name "PGE1") (class "Default")
      (node (ref "D73") (pin "C") (pinfunction "C_C") (pintype "passive"))
      (node (ref "Q41") (pin "G") (pinfunction "G_G") (pintype "passive"))
      (node (ref "SV3") (pin "1") (pinfunction "1_1") (pintype "passive"))
    )
    (net (code "262") (name "PGE2") (class "Default")
      (node (ref "D101") (pin "C") (pinfunction "C_C") (pintype "passive"))
      (node (ref "Q69") (pin "G") (pinfunction "G_G") (pintype "passive"))
      (node (ref "SV1") (pin "6") (pinfunction "6_6") (pintype "passive"))
    )
    (net (code "263") (name "PGF1") (class "Default")
      (node (ref "D75") (pin "C") (pinfunction "C_C") (pintype "passive"))
      (node (ref "Q43") (pin "G") (pinfunction "G_G") (pintype "passive"))
      (node (ref "SV3") (pin "3") (pinfunction "3_3") (pintype "passive"))
    )
    (net (code "264") (name "PGF2") (class "Default")
      (node (ref "D103") (pin "C") (pinfunction "C_C") (pintype "passive"))
      (node (ref "Q71") (pin "G") (pinfunction "G_G") (pintype "passive"))
      (node (ref "SV1") (pin "8") (pinfunction "8_8") (pintype "passive"))
    )
    (net (code "265") (name "PGH1") (class "Default")
      (node (ref "D77") (pin "C") (pinfunction "C_C") (pintype "passive"))
      (node (ref "Q45") (pin "G") (pinfunction "G_G") (pintype "passive"))
      (node (ref "SV3") (pin "5") (pinfunction "5_5") (pintype "passive"))
    )
    (net (code "266") (name "PGH2") (class "Default")
      (node (ref "D105") (pin "C") (pinfunction "C_C") (pintype "passive"))
      (node (ref "Q73") (pin "G") (pinfunction "G_G") (pintype "passive"))
      (node (ref "SV1") (pin "1") (pinfunction "1_1") (pintype "passive"))
    )
    (net (code "267") (name "PGJ1") (class "Default")
      (node (ref "D79") (pin "C") (pinfunction "C_C") (pintype "passive"))
      (node (ref "Q47") (pin "G") (pinfunction "G_G") (pintype "passive"))
      (node (ref "SV3") (pin "7") (pinfunction "7_7") (pintype "passive"))
    )
    (net (code "268") (name "PGJ2") (class "Default")
      (node (ref "D107") (pin "C") (pinfunction "C_C") (pintype "passive"))
      (node (ref "Q75") (pin "G") (pinfunction "G_G") (pintype "passive"))
      (node (ref "SV1") (pin "3") (pinfunction "3_3") (pintype "passive"))
    )
    (net (code "269") (name "PGK1") (class "Default")
      (node (ref "D81") (pin "C") (pinfunction "C_C") (pintype "passive"))
      (node (ref "Q49") (pin "G") (pinfunction "G_G") (pintype "passive"))
      (node (ref "SV3") (pin "10") (pinfunction "10_10") (pintype "passive"))
    )
    (net (code "270") (name "PGK2") (class "Default")
      (node (ref "D109") (pin "C") (pinfunction "C_C") (pintype "passive"))
      (node (ref "Q77") (pin "G") (pinfunction "G_G") (pintype "passive"))
      (node (ref "SV1") (pin "5") (pinfunction "5_5") (pintype "passive"))
    )
    (net (code "271") (name "PGL1") (class "Default")
      (node (ref "D83") (pin "C") (pinfunction "C_C") (pintype "passive"))
      (node (ref "Q51") (pin "G") (pinfunction "G_G") (pintype "passive"))
      (node (ref "SV3") (pin "12") (pinfunction "12_12") (pintype "passive"))
    )
    (net (code "272") (name "PGL2") (class "Default")
      (node (ref "D111") (pin "C") (pinfunction "C_C") (pintype "passive"))
      (node (ref "Q79") (pin "G") (pinfunction "G_G") (pintype "passive"))
      (node (ref "SV1") (pin "7") (pinfunction "7_7") (pintype "passive"))
    )
    (net (code "273") (name "PGM1") (class "Default")
      (node (ref "D85") (pin "C") (pinfunction "C_C") (pintype "passive"))
      (node (ref "Q53") (pin "G") (pinfunction "G_G") (pintype "passive"))
      (node (ref "SV3") (pin "14") (pinfunction "14_14") (pintype "passive"))
    )
    (net (code "274") (name "PGM2") (class "Default")
      (node (ref "D113") (pin "C") (pinfunction "C_C") (pintype "passive"))
      (node (ref "Q81") (pin "G") (pinfunction "G_G") (pintype "passive"))
      (node (ref "SV1") (pin "10") (pinfunction "10_10") (pintype "passive"))
    )
    (net (code "275") (name "PGN1") (class "Default")
      (node (ref "D87") (pin "C") (pinfunction "C_C") (pintype "passive"))
      (node (ref "Q55") (pin "G") (pinfunction "G_G") (pintype "passive"))
      (node (ref "SV3") (pin "16") (pinfunction "16_16") (pintype "passive"))
    )
    (net (code "276") (name "PGN2") (class "Default")
      (node (ref "D115") (pin "C") (pinfunction "C_C") (pintype "passive"))
      (node (ref "Q83") (pin "G") (pinfunction "G_G") (pintype "passive"))
      (node (ref "SV1") (pin "12") (pinfunction "12_12") (pintype "passive"))
    )
    (net (code "277") (name "PGP1") (class "Default")
      (node (ref "D89") (pin "C") (pinfunction "C_C") (pintype "passive"))
      (node (ref "Q57") (pin "G") (pinfunction "G_G") (pintype "passive"))
      (node (ref "SV3") (pin "9") (pinfunction "9_9") (pintype "passive"))
    )
    (net (code "278") (name "PGP2") (class "Default")
      (node (ref "D117") (pin "C") (pinfunction "C_C") (pintype "passive"))
      (node (ref "Q85") (pin "G") (pinfunction "G_G") (pintype "passive"))
      (node (ref "SV1") (pin "14") (pinfunction "14_14") (pintype "passive"))
    )
    (net (code "279") (name "PGR1") (class "Default")
      (node (ref "D91") (pin "C") (pinfunction "C_C") (pintype "passive"))
      (node (ref "Q59") (pin "G") (pinfunction "G_G") (pintype "passive"))
      (node (ref "SV3") (pin "11") (pinfunction "11_11") (pintype "passive"))
    )
    (net (code "280") (name "PGR2") (class "Default")
      (node (ref "D119") (pin "C") (pinfunction "C_C") (pintype "passive"))
      (node (ref "Q87") (pin "G") (pinfunction "G_G") (pintype "passive"))
      (node (ref "SV1") (pin "16") (pinfunction "16_16") (pintype "passive"))
    )
    (net (code "281") (name "PGS1") (class "Default")
      (node (ref "D93") (pin "C") (pinfunction "C_C") (pintype "passive"))
      (node (ref "Q61") (pin "G") (pinfunction "G_G") (pintype "passive"))
      (node (ref "SV3") (pin "13") (pinfunction "13_13") (pintype "passive"))
    )
    (net (code "282") (name "PGS2") (class "Default")
      (node (ref "D121") (pin "C") (pinfunction "C_C") (pintype "passive"))
      (node (ref "Q89") (pin "G") (pinfunction "G_G") (pintype "passive"))
      (node (ref "SV1") (pin "9") (pinfunction "9_9") (pintype "passive"))
    )
    (net (code "283") (name "PGT2") (class "Default")
      (node (ref "D123") (pin "C") (pinfunction "C_C") (pintype "passive"))
      (node (ref "Q91") (pin "G") (pinfunction "G_G") (pintype "passive"))
      (node (ref "SV1") (pin "11") (pinfunction "11_11") (pintype "passive"))
    )
    (net (code "284") (name "PGU1") (class "Default")
      (node (ref "D95") (pin "C") (pinfunction "C_C") (pintype "passive"))
      (node (ref "Q63") (pin "G") (pinfunction "G_G") (pintype "passive"))
      (node (ref "SV3") (pin "15") (pinfunction "15_15") (pintype "passive"))
    )
    (net (code "285") (name "PGU2") (class "Default")
      (node (ref "D125") (pin "C") (pinfunction "C_C") (pintype "passive"))
      (node (ref "Q93") (pin "G") (pinfunction "G_G") (pintype "passive"))
      (node (ref "SV1") (pin "13") (pinfunction "13_13") (pintype "passive"))
    )
    (net (code "286") (name "PGV1") (class "Default")
      (node (ref "D97") (pin "C") (pinfunction "C_C") (pintype "passive"))
      (node (ref "Q65") (pin "G") (pinfunction "G_G") (pintype "passive"))
      (node (ref "SV1") (pin "2") (pinfunction "2_2") (pintype "passive"))
    )
    (net (code "287") (name "PGV2") (class "Default")
      (node (ref "D127") (pin "C") (pinfunction "C_C") (pintype "passive"))
      (node (ref "Q95") (pin "G") (pinfunction "G_G") (pintype "passive"))
      (node (ref "SV1") (pin "15") (pinfunction "15_15") (pintype "passive"))
    )
    (net (code "288") (name "R1") (class "Default")
      (node (ref "Q16") (pin "D") (pinfunction "D_D") (pintype "passive"))
      (node (ref "Q59") (pin "D") (pinfunction "D_D") (pintype "passive"))
      (node (ref "Q60") (pin "D") (pinfunction "D_D") (pintype "passive"))
      (node (ref "R64") (pin "1") (pinfunction "1_1") (pintype "passive"))
      (node (ref "SIDE1") (pin "26") (pinfunction "26_26") (pintype "passive"))
    )
    (net (code "289") (name "R2") (class "Default")
      (node (ref "Q30") (pin "D") (pinfunction "D_D") (pintype "passive"))
      (node (ref "Q87") (pin "D") (pinfunction "D_D") (pintype "passive"))
      (node (ref "Q88") (pin "D") (pinfunction "D_D") (pintype "passive"))
      (node (ref "R120") (pin "1") (pinfunction "1_1") (pintype "passive"))
      (node (ref "SIDE2") (pin "26") (pinfunction "26_26") (pintype "passive"))
    )
    (net (code "290") (name "RXA1") (class "Default")
      (node (ref "D2") (pin "C") (pinfunction "C_C") (pintype "passive"))
      (node (ref "R7") (pin "1") (pinfunction "1_1") (pintype "passive"))
      (node (ref "SV7") (pin "2") (pinfunction "2_2") (pintype "passive"))
    )
    (net (code "291") (name "RXB1") (class "Default")
      (node (ref "D9") (pin "C") (pinfunction "C_C") (pintype "passive"))
      (node (ref "R18") (pin "1") (pinfunction "1_1") (pintype "passive"))
      (node (ref "SV7") (pin "4") (pinfunction "4_4") (pintype "passive"))
    )
    (net (code "292") (name "RXC1") (class "Default")
      (node (ref "D10") (pin "C") (pinfunction "C_C") (pintype "passive"))
      (node (ref "R22") (pin "1") (pinfunction "1_1") (pintype "passive"))
      (node (ref "SV7") (pin "6") (pinfunction "6_6") (pintype "passive"))
    )
    (net (code "293") (name "RXD1") (class "Default")
      (node (ref "D11") (pin "C") (pinfunction "C_C") (pintype "passive"))
      (node (ref "R26") (pin "1") (pinfunction "1_1") (pintype "passive"))
      (node (ref "SV7") (pin "8") (pinfunction "8_8") (pintype "passive"))
    )
    (net (code "294") (name "RXD2") (class "Default")
      (node (ref "D25") (pin "C") (pinfunction "C_C") (pintype "passive"))
      (node (ref "R82") (pin "1") (pinfunction "1_1") (pintype "passive"))
      (node (ref "SV8") (pin "4") (pinfunction "4_4") (pintype "passive"))
    )
    (net (code "295") (name "RXE1") (class "Default")
      (node (ref "D12") (pin "C") (pinfunction "C_C") (pintype "passive"))
      (node (ref "R30") (pin "1") (pinfunction "1_1") (pintype "passive"))
      (node (ref "SV7") (pin "1") (pinfunction "1_1") (pintype "passive"))
    )
    (net (code "296") (name "RXE2") (class "Default")
      (node (ref "D26") (pin "C") (pinfunction "C_C") (pintype "passive"))
      (node (ref "R86") (pin "1") (pinfunction "1_1") (pintype "passive"))
      (node (ref "SV8") (pin "6") (pinfunction "6_6") (pintype "passive"))
    )
    (net (code "297") (name "RXF1") (class "Default")
      (node (ref "D13") (pin "C") (pinfunction "C_C") (pintype "passive"))
      (node (ref "R34") (pin "1") (pinfunction "1_1") (pintype "passive"))
      (node (ref "SV7") (pin "3") (pinfunction "3_3") (pintype "passive"))
    )
    (net (code "298") (name "RXF2") (class "Default")
      (node (ref "D27") (pin "C") (pinfunction "C_C") (pintype "passive"))
      (node (ref "R90") (pin "1") (pinfunction "1_1") (pintype "passive"))
      (node (ref "SV8") (pin "8") (pinfunction "8_8") (pintype "passive"))
    )
    (net (code "299") (name "RXH1") (class "Default")
      (node (ref "D14") (pin "C") (pinfunction "C_C") (pintype "passive"))
      (node (ref "R38") (pin "1") (pinfunction "1_1") (pintype "passive"))
      (node (ref "SV7") (pin "5") (pinfunction "5_5") (pintype "passive"))
    )
    (net (code "300") (name "RXH2") (class "Default")
      (node (ref "D28") (pin "C") (pinfunction "C_C") (pintype "passive"))
      (node (ref "R94") (pin "1") (pinfunction "1_1") (pintype "passive"))
      (node (ref "SV8") (pin "1") (pinfunction "1_1") (pintype "passive"))
    )
    (net (code "301") (name "RXJ1") (class "Default")
      (node (ref "D15") (pin "C") (pinfunction "C_C") (pintype "passive"))
      (node (ref "R42") (pin "1") (pinfunction "1_1") (pintype "passive"))
      (node (ref "SV7") (pin "7") (pinfunction "7_7") (pintype "passive"))
    )
    (net (code "302") (name "RXJ2") (class "Default")
      (node (ref "D29") (pin "C") (pinfunction "C_C") (pintype "passive"))
      (node (ref "R98") (pin "1") (pinfunction "1_1") (pintype "passive"))
      (node (ref "SV8") (pin "3") (pinfunction "3_3") (pintype "passive"))
    )
    (net (code "303") (name "RXK1") (class "Default")
      (node (ref "D16") (pin "C") (pinfunction "C_C") (pintype "passive"))
      (node (ref "R46") (pin "1") (pinfunction "1_1") (pintype "passive"))
      (node (ref "SV7") (pin "10") (pinfunction "10_10") (pintype "passive"))
    )
    (net (code "304") (name "RXK2") (class "Default")
      (node (ref "D30") (pin "C") (pinfunction "C_C") (pintype "passive"))
      (node (ref "R102") (pin "1") (pinfunction "1_1") (pintype "passive"))
      (node (ref "SV8") (pin "5") (pinfunction "5_5") (pintype "passive"))
    )
    (net (code "305") (name "RXL1") (class "Default")
      (node (ref "D17") (pin "C") (pinfunction "C_C") (pintype "passive"))
      (node (ref "R50") (pin "1") (pinfunction "1_1") (pintype "passive"))
      (node (ref "SV7") (pin "12") (pinfunction "12_12") (pintype "passive"))
    )
    (net (code "306") (name "RXL2") (class "Default")
      (node (ref "D31") (pin "C") (pinfunction "C_C") (pintype "passive"))
      (node (ref "R106") (pin "1") (pinfunction "1_1") (pintype "passive"))
      (node (ref "SV8") (pin "7") (pinfunction "7_7") (pintype "passive"))
    )
    (net (code "307") (name "RXM1") (class "Default")
      (node (ref "D18") (pin "C") (pinfunction "C_C") (pintype "passive"))
      (node (ref "R54") (pin "1") (pinfunction "1_1") (pintype "passive"))
      (node (ref "SV7") (pin "14") (pinfunction "14_14") (pintype "passive"))
    )
    (net (code "308") (name "RXM2") (class "Default")
      (node (ref "D32") (pin "C") (pinfunction "C_C") (pintype "passive"))
      (node (ref "R110") (pin "1") (pinfunction "1_1") (pintype "passive"))
      (node (ref "SV8") (pin "10") (pinfunction "10_10") (pintype "passive"))
    )
    (net (code "309") (name "RXN1") (class "Default")
      (node (ref "D19") (pin "C") (pinfunction "C_C") (pintype "passive"))
      (node (ref "R58") (pin "1") (pinfunction "1_1") (pintype "passive"))
      (node (ref "SV7") (pin "16") (pinfunction "16_16") (pintype "passive"))
    )
    (net (code "310") (name "RXN2") (class "Default")
      (node (ref "D33") (pin "C") (pinfunction "C_C") (pintype "passive"))
      (node (ref "R114") (pin "1") (pinfunction "1_1") (pintype "passive"))
      (node (ref "SV8") (pin "12") (pinfunction "12_12") (pintype "passive"))
    )
    (net (code "311") (name "RXP1") (class "Default")
      (node (ref "D20") (pin "C") (pinfunction "C_C") (pintype "passive"))
      (node (ref "R62") (pin "1") (pinfunction "1_1") (pintype "passive"))
      (node (ref "SV7") (pin "9") (pinfunction "9_9") (pintype "passive"))
    )
    (net (code "312") (name "RXP2") (class "Default")
      (node (ref "D34") (pin "C") (pinfunction "C_C") (pintype "passive"))
      (node (ref "R118") (pin "1") (pinfunction "1_1") (pintype "passive"))
      (node (ref "SV8") (pin "14") (pinfunction "14_14") (pintype "passive"))
    )
    (net (code "313") (name "RXR1") (class "Default")
      (node (ref "D21") (pin "C") (pinfunction "C_C") (pintype "passive"))
      (node (ref "R66") (pin "1") (pinfunction "1_1") (pintype "passive"))
      (node (ref "SV7") (pin "11") (pinfunction "11_11") (pintype "passive"))
    )
    (net (code "314") (name "RXR2") (class "Default")
      (node (ref "D35") (pin "C") (pinfunction "C_C") (pintype "passive"))
      (node (ref "R122") (pin "1") (pinfunction "1_1") (pintype "passive"))
      (node (ref "SV8") (pin "16") (pinfunction "16_16") (pintype "passive"))
    )
    (net (code "315") (name "RXS1") (class "Default")
      (node (ref "D22") (pin "C") (pinfunction "C_C") (pintype "passive"))
      (node (ref "R70") (pin "1") (pinfunction "1_1") (pintype "passive"))
      (node (ref "SV7") (pin "13") (pinfunction "13_13") (pintype "passive"))
    )
    (net (code "316") (name "RXS2") (class "Default")
      (node (ref "D36") (pin "C") (pinfunction "C_C") (pintype "passive"))
      (node (ref "R126") (pin "1") (pinfunction "1_1") (pintype "passive"))
      (node (ref "SV8") (pin "9") (pinfunction "9_9") (pintype "passive"))
    )
    (net (code "317") (name "RXT2") (class "Default")
      (node (ref "D37") (pin "C") (pinfunction "C_C") (pintype "passive"))
      (node (ref "R130") (pin "1") (pinfunction "1_1") (pintype "passive"))
      (node (ref "SV8") (pin "11") (pinfunction "11_11") (pintype "passive"))
    )
    (net (code "318") (name "RXU1") (class "Default")
      (node (ref "D23") (pin "C") (pinfunction "C_C") (pintype "passive"))
      (node (ref "R74") (pin "1") (pinfunction "1_1") (pintype "passive"))
      (node (ref "SV7") (pin "15") (pinfunction "15_15") (pintype "passive"))
    )
    (net (code "319") (name "RXU2") (class "Default")
      (node (ref "D38") (pin "C") (pinfunction "C_C") (pintype "passive"))
      (node (ref "R134") (pin "1") (pinfunction "1_1") (pintype "passive"))
      (node (ref "SV8") (pin "13") (pinfunction "13_13") (pintype "passive"))
    )
    (net (code "320") (name "RXV1") (class "Default")
      (node (ref "D24") (pin "C") (pinfunction "C_C") (pintype "passive"))
      (node (ref "R78") (pin "1") (pinfunction "1_1") (pintype "passive"))
      (node (ref "SV8") (pin "2") (pinfunction "2_2") (pintype "passive"))
    )
    (net (code "321") (name "RXV2") (class "Default")
      (node (ref "D39") (pin "C") (pinfunction "C_C") (pintype "passive"))
      (node (ref "R138") (pin "1") (pinfunction "1_1") (pintype "passive"))
      (node (ref "SV8") (pin "15") (pinfunction "15_15") (pintype "passive"))
    )
    (net (code "322") (name "S1") (class "Default")
      (node (ref "Q17") (pin "D") (pinfunction "D_D") (pintype "passive"))
      (node (ref "Q61") (pin "D") (pinfunction "D_D") (pintype "passive"))
      (node (ref "Q62") (pin "D") (pinfunction "D_D") (pintype "passive"))
      (node (ref "R68") (pin "1") (pinfunction "1_1") (pintype "passive"))
      (node (ref "SIDE1") (pin "32") (pinfunction "32_32") (pintype "passive"))
    )
    (net (code "323") (name "S2") (class "Default")
      (node (ref "Q31") (pin "D") (pinfunction "D_D") (pintype "passive"))
      (node (ref "Q89") (pin "D") (pinfunction "D_D") (pintype "passive"))
      (node (ref "Q90") (pin "D") (pinfunction "D_D") (pintype "passive"))
      (node (ref "R124") (pin "1") (pinfunction "1_1") (pintype "passive"))
      (node (ref "SIDE2") (pin "28") (pinfunction "28_28") (pintype "passive"))
    )
    (net (code "324") (name "T1") (class "Default")
      (node (ref "SIDE1") (pin "34") (pinfunction "34_34") (pintype "passive"))
      (node (ref "T1") (pin "1") (pinfunction "1_1") (pintype "passive"))
    )
    (net (code "325") (name "T2") (class "Default")
      (node (ref "Q32") (pin "D") (pinfunction "D_D") (pintype "passive"))
      (node (ref "Q91") (pin "D") (pinfunction "D_D") (pintype "passive"))
      (node (ref "Q92") (pin "D") (pinfunction "D_D") (pintype "passive"))
      (node (ref "R128") (pin "1") (pinfunction "1_1") (pintype "passive"))
      (node (ref "SIDE2") (pin "30") (pinfunction "30_30") (pintype "passive"))
    )
    (net (code "326") (name "THR") (class "Default")
      (node (ref "JP1") (pin "2") (pinfunction "2_2") (pintype "passive"))
      (node (ref "JP10") (pin "2") (pinfunction "2_2") (pintype "passive"))
      (node (ref "JP11") (pin "2") (pinfunction "2_2") (pintype "passive"))
      (node (ref "JP12") (pin "2") (pinfunction "2_2") (pintype "passive"))
      (node (ref "JP13") (pin "2") (pinfunction "2_2") (pintype "passive"))
      (node (ref "JP14") (pin "2") (pinfunction "2_2") (pintype "passive"))
      (node (ref "JP15") (pin "2") (pinfunction "2_2") (pintype "passive"))
      (node (ref "JP16") (pin "2") (pinfunction "2_2") (pintype "passive"))
      (node (ref "JP17") (pin "2") (pinfunction "2_2") (pintype "passive"))
      (node (ref "JP18") (pin "2") (pinfunction "2_2") (pintype "passive"))
      (node (ref "JP19") (pin "2") (pinfunction "2_2") (pintype "passive"))
      (node (ref "JP20") (pin "2") (pinfunction "2_2") (pintype "passive"))
      (node (ref "JP21") (pin "2") (pinfunction "2_2") (pintype "passive"))
      (node (ref "JP22") (pin "2") (pinfunction "2_2") (pintype "passive"))
      (node (ref "JP23") (pin "2") (pinfunction "2_2") (pintype "passive"))
      (node (ref "JP24") (pin "2") (pinfunction "2_2") (pintype "passive"))
      (node (ref "JP25") (pin "2") (pinfunction "2_2") (pintype "passive"))
      (node (ref "JP26") (pin "2") (pinfunction "2_2") (pintype "passive"))
      (node (ref "JP27") (pin "2") (pinfunction "2_2") (pintype "passive"))
      (node (ref "JP28") (pin "2") (pinfunction "2_2") (pintype "passive"))
      (node (ref "JP29") (pin "2") (pinfunction "2_2") (pintype "passive"))
      (node (ref "JP3") (pin "2") (pinfunction "2_2") (pintype "passive"))
      (node (ref "JP30") (pin "2") (pinfunction "2_2") (pintype "passive"))
      (node (ref "JP31") (pin "2") (pinfunction "2_2") (pintype "passive"))
      (node (ref "JP32") (pin "2") (pinfunction "2_2") (pintype "passive"))
      (node (ref "JP33") (pin "2") (pinfunction "2_2") (pintype "passive"))
      (node (ref "JP4") (pin "2") (pinfunction "2_2") (pintype "passive"))
      (node (ref "JP5") (pin "2") (pinfunction "2_2") (pintype "passive"))
      (node (ref "JP6") (pin "2") (pinfunction "2_2") (pintype "passive"))
      (node (ref "JP7") (pin "2") (pinfunction "2_2") (pintype "passive"))
      (node (ref "JP8") (pin "2") (pinfunction "2_2") (pintype "passive"))
      (node (ref "JP9") (pin "2") (pinfunction "2_2") (pintype "passive"))
      (node (ref "THR") (pin "2") (pinfunction "S_2") (pintype "passive"))
      (node (ref "THR_TP") (pin "1") (pinfunction "P_1") (pintype "passive"))
    )
    (net (code "327") (name "U1") (class "Default")
      (node (ref "Q18") (pin "D") (pinfunction "D_D") (pintype "passive"))
      (node (ref "Q63") (pin "D") (pinfunction "D_D") (pintype "passive"))
      (node (ref "Q64") (pin "D") (pinfunction "D_D") (pintype "passive"))
      (node (ref "R72") (pin "1") (pinfunction "1_1") (pintype "passive"))
      (node (ref "SIDE1") (pin "4") (pinfunction "4_4") (pintype "passive"))
    )
    (net (code "328") (name "U2") (class "Default")
      (node (ref "Q33") (pin "D") (pinfunction "D_D") (pintype "passive"))
      (node (ref "Q93") (pin "D") (pinfunction "D_D") (pintype "passive"))
      (node (ref "Q94") (pin "D") (pinfunction "D_D") (pintype "passive"))
      (node (ref "R132") (pin "1") (pinfunction "1_1") (pintype "passive"))
      (node (ref "SIDE2") (pin "34") (pinfunction "34_34") (pintype "passive"))
    )
    (net (code "329") (name "V+") (class "Default")
      (node (ref "5V") (pin "2") (pinfunction "2_2") (pintype "passive"))
      (node (ref "A2") (pin "2") (pinfunction "2_2") (pintype "passive"))
      (node (ref "IC1") (pin "3") (pinfunction "V+_3") (pintype "power_in"))
      (node (ref "IC2") (pin "3") (pinfunction "V+_3") (pintype "power_in"))
      (node (ref "IC3") (pin "3") (pinfunction "V+_3") (pintype "power_in"))
      (node (ref "IC4") (pin "3") (pinfunction "V+_3") (pintype "power_in"))
      (node (ref "IC5") (pin "3") (pinfunction "V+_3") (pintype "power_in"))
      (node (ref "IC6") (pin "3") (pinfunction "V+_3") (pintype "power_in"))
      (node (ref "IC7") (pin "3") (pinfunction "V+_3") (pintype "power_in"))
      (node (ref "IC8") (pin "3") (pinfunction "V+_3") (pintype "power_in"))
      (node (ref "IC9") (pin "IN") (pinfunction "IN_IN") (pintype "input"))
      (node (ref "R101") (pin "2") (pinfunction "2_2") (pintype "passive"))
      (node (ref "R105") (pin "2") (pinfunction "2_2") (pintype "passive"))
      (node (ref "R109") (pin "2") (pinfunction "2_2") (pintype "passive"))
      (node (ref "R113") (pin "2") (pinfunction "2_2") (pintype "passive"))
      (node (ref "R117") (pin "2") (pinfunction "2_2") (pintype "passive"))
      (node (ref "R121") (pin "2") (pinfunction "2_2") (pintype "passive"))
      (node (ref "R125") (pin "2") (pinfunction "2_2") (pintype "passive"))
      (node (ref "R129") (pin "2") (pinfunction "2_2") (pintype "passive"))
      (node (ref "R133") (pin "2") (pinfunction "2_2") (pintype "passive"))
      (node (ref "R137") (pin "2") (pinfunction "2_2") (pintype "passive"))
      (node (ref "R17") (pin "2") (pinfunction "2_2") (pintype "passive"))
      (node (ref "R21") (pin "2") (pinfunction "2_2") (pintype "passive"))
      (node (ref "R25") (pin "2") (pinfunction "2_2") (pintype "passive"))
      (node (ref "R29") (pin "2") (pinfunction "2_2") (pintype "passive"))
      (node (ref "R323") (pin "2") (pinfunction "2_2") (pintype "passive"))
      (node (ref "R33") (pin "2") (pinfunction "2_2") (pintype "passive"))
      (node (ref "R37") (pin "2") (pinfunction "2_2") (pintype "passive"))
      (node (ref "R41") (pin "2") (pinfunction "2_2") (pintype "passive"))
      (node (ref "R45") (pin "2") (pinfunction "2_2") (pintype "passive"))
      (node (ref "R49") (pin "2") (pinfunction "2_2") (pintype "passive"))
      (node (ref "R53") (pin "2") (pinfunction "2_2") (pintype "passive"))
      (node (ref "R57") (pin "2") (pinfunction "2_2") (pintype "passive"))
      (node (ref "R6") (pin "2") (pinfunction "2_2") (pintype "passive"))
      (node (ref "R61") (pin "2") (pinfunction "2_2") (pintype "passive"))
      (node (ref "R65") (pin "2") (pinfunction "2_2") (pintype "passive"))
      (node (ref "R69") (pin "2") (pinfunction "2_2") (pintype "passive"))
      (node (ref "R73") (pin "2") (pinfunction "2_2") (pintype "passive"))
      (node (ref "R77") (pin "2") (pinfunction "2_2") (pintype "passive"))
      (node (ref "R81") (pin "2") (pinfunction "2_2") (pintype "passive"))
      (node (ref "R85") (pin "2") (pinfunction "2_2") (pintype "passive"))
      (node (ref "R89") (pin "2") (pinfunction "2_2") (pintype "passive"))
      (node (ref "R93") (pin "2") (pinfunction "2_2") (pintype "passive"))
      (node (ref "R97") (pin "2") (pinfunction "2_2") (pintype "passive"))
      (node (ref "V+") (pin "1") (pinfunction "P_1") (pintype "passive"))
    )
    (net (code "330") (name "V-") (class "Default")
      (node (ref "B2") (pin "2") (pinfunction "2_2") (pintype "passive"))
      (node (ref "IC1") (pin "12") (pinfunction "GND_12") (pintype "power_in"))
      (node (ref "IC10") (pin "IN") (pinfunction "IN_IN") (pintype "input"))
      (node (ref "IC2") (pin "12") (pinfunction "GND_12") (pintype "power_in"))
      (node (ref "IC3") (pin "12") (pinfunction "GND_12") (pintype "power_in"))
      (node (ref "IC4") (pin "12") (pinfunction "GND_12") (pintype "power_in"))
      (node (ref "IC5") (pin "12") (pinfunction "GND_12") (pintype "power_in"))
      (node (ref "IC6") (pin "12") (pinfunction "GND_12") (pintype "power_in"))
      (node (ref "IC7") (pin "12") (pinfunction "GND_12") (pintype "power_in"))
      (node (ref "IC8") (pin "12") (pinfunction "GND_12") (pintype "power_in"))
      (node (ref "R321") (pin "1") (pinfunction "1_1") (pintype "passive"))
      (node (ref "V-") (pin "1") (pinfunction "P_1") (pintype "passive"))
    )
    (net (code "331") (name "V1") (class "Default")
      (node (ref "Q19") (pin "D") (pinfunction "D_D") (pintype "passive"))
      (node (ref "Q65") (pin "D") (pinfunction "D_D") (pintype "passive"))
      (node (ref "Q66") (pin "D") (pinfunction "D_D") (pintype "passive"))
      (node (ref "R76") (pin "1") (pinfunction "1_1") (pintype "passive"))
      (node (ref "SIDE1") (pin "2") (pinfunction "2_2") (pintype "passive"))
    )
    (net (code "332") (name "V2") (class "Default")
      (node (ref "Q34") (pin "D") (pinfunction "D_D") (pintype "passive"))
      (node (ref "Q95") (pin "D") (pinfunction "D_D") (pintype "passive"))
      (node (ref "Q96") (pin "D") (pinfunction "D_D") (pintype "passive"))
      (node (ref "R136") (pin "1") (pinfunction "1_1") (pintype "passive"))
      (node (ref "SIDE2") (pin "32") (pinfunction "32_32") (pintype "passive"))
    )
    (net (code "333") (name "~{PUA1}") (class "Default")
      (node (ref "D6") (pin "C") (pinfunction "C_C") (pintype "passive"))
      (node (ref "Q2") (pin "G") (pinfunction "G_G") (pintype "passive"))
      (node (ref "SV4") (pin "2") (pinfunction "2_2") (pintype "passive"))
    )
    (net (code "334") (name "~{PUB1}") (class "Default")
      (node (ref "D68") (pin "C") (pinfunction "C_C") (pintype "passive"))
      (node (ref "Q36") (pin "G") (pinfunction "G_G") (pintype "passive"))
      (node (ref "SV4") (pin "4") (pinfunction "4_4") (pintype "passive"))
    )
    (net (code "335") (name "~{PUC1}") (class "Default")
      (node (ref "D70") (pin "C") (pinfunction "C_C") (pintype "passive"))
      (node (ref "Q38") (pin "G") (pinfunction "G_G") (pintype "passive"))
      (node (ref "SV4") (pin "6") (pinfunction "6_6") (pintype "passive"))
    )
    (net (code "336") (name "~{PUD1}") (class "Default")
      (node (ref "D72") (pin "C") (pinfunction "C_C") (pintype "passive"))
      (node (ref "Q40") (pin "G") (pinfunction "G_G") (pintype "passive"))
      (node (ref "SV4") (pin "8") (pinfunction "8_8") (pintype "passive"))
    )
    (net (code "337") (name "~{PUD2}") (class "Default")
      (node (ref "D100") (pin "C") (pinfunction "C_C") (pintype "passive"))
      (node (ref "Q68") (pin "G") (pinfunction "G_G") (pintype "passive"))
      (node (ref "SV2") (pin "4") (pinfunction "4_4") (pintype "passive"))
    )
    (net (code "338") (name "~{PUE1}") (class "Default")
      (node (ref "D74") (pin "C") (pinfunction "C_C") (pintype "passive"))
      (node (ref "Q42") (pin "G") (pinfunction "G_G") (pintype "passive"))
      (node (ref "SV4") (pin "1") (pinfunction "1_1") (pintype "passive"))
    )
    (net (code "339") (name "~{PUE2}") (class "Default")
      (node (ref "D102") (pin "C") (pinfunction "C_C") (pintype "passive"))
      (node (ref "Q70") (pin "G") (pinfunction "G_G") (pintype "passive"))
      (node (ref "SV2") (pin "6") (pinfunction "6_6") (pintype "passive"))
    )
    (net (code "340") (name "~{PUF1}") (class "Default")
      (node (ref "D76") (pin "C") (pinfunction "C_C") (pintype "passive"))
      (node (ref "Q44") (pin "G") (pinfunction "G_G") (pintype "passive"))
      (node (ref "SV4") (pin "3") (pinfunction "3_3") (pintype "passive"))
    )
    (net (code "341") (name "~{PUF2}") (class "Default")
      (node (ref "D104") (pin "C") (pinfunction "C_C") (pintype "passive"))
      (node (ref "Q72") (pin "G") (pinfunction "G_G") (pintype "passive"))
      (node (ref "SV2") (pin "8") (pinfunction "8_8") (pintype "passive"))
    )
    (net (code "342") (name "~{PUH1}") (class "Default")
      (node (ref "D78") (pin "C") (pinfunction "C_C") (pintype "passive"))
      (node (ref "Q46") (pin "G") (pinfunction "G_G") (pintype "passive"))
      (node (ref "SV4") (pin "5") (pinfunction "5_5") (pintype "passive"))
    )
    (net (code "343") (name "~{PUH2}") (class "Default")
      (node (ref "D106") (pin "C") (pinfunction "C_C") (pintype "passive"))
      (node (ref "Q74") (pin "G") (pinfunction "G_G") (pintype "passive"))
      (node (ref "SV2") (pin "1") (pinfunction "1_1") (pintype "passive"))
    )
    (net (code "344") (name "~{PUJ1}") (class "Default")
      (node (ref "D80") (pin "C") (pinfunction "C_C") (pintype "passive"))
      (node (ref "Q48") (pin "G") (pinfunction "G_G") (pintype "passive"))
      (node (ref "SV4") (pin "7") (pinfunction "7_7") (pintype "passive"))
    )
    (net (code "345") (name "~{PUJ2}") (class "Default")
      (node (ref "D108") (pin "C") (pinfunction "C_C") (pintype "passive"))
      (node (ref "Q76") (pin "G") (pinfunction "G_G") (pintype "passive"))
      (node (ref "SV2") (pin "3") (pinfunction "3_3") (pintype "passive"))
    )
    (net (code "346") (name "~{PUK1}") (class "Default")
      (node (ref "D82") (pin "C") (pinfunction "C_C") (pintype "passive"))
      (node (ref "Q50") (pin "G") (pinfunction "G_G") (pintype "passive"))
      (node (ref "SV4") (pin "10") (pinfunction "10_10") (pintype "passive"))
    )
    (net (code "347") (name "~{PUK2}") (class "Default")
      (node (ref "D110") (pin "C") (pinfunction "C_C") (pintype "passive"))
      (node (ref "Q78") (pin "G") (pinfunction "G_G") (pintype "passive"))
      (node (ref "SV2") (pin "5") (pinfunction "5_5") (pintype "passive"))
    )
    (net (code "348") (name "~{PUL1}") (class "Default")
      (node (ref "D84") (pin "C") (pinfunction "C_C") (pintype "passive"))
      (node (ref "Q52") (pin "G") (pinfunction "G_G") (pintype "passive"))
      (node (ref "SV4") (pin "12") (pinfunction "12_12") (pintype "passive"))
    )
    (net (code "349") (name "~{PUL2}") (class "Default")
      (node (ref "D112") (pin "C") (pinfunction "C_C") (pintype "passive"))
      (node (ref "Q80") (pin "G") (pinfunction "G_G") (pintype "passive"))
      (node (ref "SV2") (pin "7") (pinfunction "7_7") (pintype "passive"))
    )
    (net (code "350") (name "~{PUM1}") (class "Default")
      (node (ref "D86") (pin "C") (pinfunction "C_C") (pintype "passive"))
      (node (ref "Q54") (pin "G") (pinfunction "G_G") (pintype "passive"))
      (node (ref "SV4") (pin "14") (pinfunction "14_14") (pintype "passive"))
    )
    (net (code "351") (name "~{PUM2}") (class "Default")
      (node (ref "D114") (pin "C") (pinfunction "C_C") (pintype "passive"))
      (node (ref "Q82") (pin "G") (pinfunction "G_G") (pintype "passive"))
      (node (ref "SV2") (pin "10") (pinfunction "10_10") (pintype "passive"))
    )
    (net (code "352") (name "~{PUN1}") (class "Default")
      (node (ref "D88") (pin "C") (pinfunction "C_C") (pintype "passive"))
      (node (ref "Q56") (pin "G") (pinfunction "G_G") (pintype "passive"))
      (node (ref "SV4") (pin "16") (pinfunction "16_16") (pintype "passive"))
    )
    (net (code "353") (name "~{PUN2}") (class "Default")
      (node (ref "D116") (pin "C") (pinfunction "C_C") (pintype "passive"))
      (node (ref "Q84") (pin "G") (pinfunction "G_G") (pintype "passive"))
      (node (ref "SV2") (pin "12") (pinfunction "12_12") (pintype "passive"))
    )
    (net (code "354") (name "~{PUP1}") (class "Default")
      (node (ref "D90") (pin "C") (pinfunction "C_C") (pintype "passive"))
      (node (ref "Q58") (pin "G") (pinfunction "G_G") (pintype "passive"))
      (node (ref "SV4") (pin "9") (pinfunction "9_9") (pintype "passive"))
    )
    (net (code "355") (name "~{PUP2}") (class "Default")
      (node (ref "D118") (pin "C") (pinfunction "C_C") (pintype "passive"))
      (node (ref "Q86") (pin "G") (pinfunction "G_G") (pintype "passive"))
      (node (ref "SV2") (pin "14") (pinfunction "14_14") (pintype "passive"))
    )
    (net (code "356") (name "~{PUR1}") (class "Default")
      (node (ref "D92") (pin "C") (pinfunction "C_C") (pintype "passive"))
      (node (ref "Q60") (pin "G") (pinfunction "G_G") (pintype "passive"))
      (node (ref "SV4") (pin "11") (pinfunction "11_11") (pintype "passive"))
    )
    (net (code "357") (name "~{PUR2}") (class "Default")
      (node (ref "D120") (pin "C") (pinfunction "C_C") (pintype "passive"))
      (node (ref "Q88") (pin "G") (pinfunction "G_G") (pintype "passive"))
      (node (ref "SV2") (pin "16") (pinfunction "16_16") (pintype "passive"))
    )
    (net (code "358") (name "~{PUS1}") (class "Default")
      (node (ref "D94") (pin "C") (pinfunction "C_C") (pintype "passive"))
      (node (ref "Q62") (pin "G") (pinfunction "G_G") (pintype "passive"))
      (node (ref "SV4") (pin "13") (pinfunction "13_13") (pintype "passive"))
    )
    (net (code "359") (name "~{PUS2}") (class "Default")
      (node (ref "D122") (pin "C") (pinfunction "C_C") (pintype "passive"))
      (node (ref "Q90") (pin "G") (pinfunction "G_G") (pintype "passive"))
      (node (ref "SV2") (pin "9") (pinfunction "9_9") (pintype "passive"))
    )
    (net (code "360") (name "~{PUT2}") (class "Default")
      (node (ref "D124") (pin "C") (pinfunction "C_C") (pintype "passive"))
      (node (ref "Q92") (pin "G") (pinfunction "G_G") (pintype "passive"))
      (node (ref "SV2") (pin "11") (pinfunction "11_11") (pintype "passive"))
    )
    (net (code "361") (name "~{PUU1}") (class "Default")
      (node (ref "D96") (pin "C") (pinfunction "C_C") (pintype "passive"))
      (node (ref "Q64") (pin "G") (pinfunction "G_G") (pintype "passive"))
      (node (ref "SV4") (pin "15") (pinfunction "15_15") (pintype "passive"))
    )
    (net (code "362") (name "~{PUU2}") (class "Default")
      (node (ref "D126") (pin "C") (pinfunction "C_C") (pintype "passive"))
      (node (ref "Q94") (pin "G") (pinfunction "G_G") (pintype "passive"))
      (node (ref "SV2") (pin "13") (pinfunction "13_13") (pintype "passive"))
    )
    (net (code "363") (name "~{PUV1}") (class "Default")
      (node (ref "D98") (pin "C") (pinfunction "C_C") (pintype "passive"))
      (node (ref "Q66") (pin "G") (pinfunction "G_G") (pintype "passive"))
      (node (ref "SV2") (pin "2") (pinfunction "2_2") (pintype "passive"))
    )
    (net (code "364") (name "~{PUV2}") (class "Default")
      (node (ref "D128") (pin "C") (pinfunction "C_C") (pintype "passive"))
      (node (ref "Q96") (pin "G") (pinfunction "G_G") (pintype "passive"))
      (node (ref "SV2") (pin "15") (pinfunction "15_15") (pintype "passive"))
    )
  )
)
